# PX4_FMUv6X_Dev_Board.net
KiCad netlist of a schematic drawn in EasyEDA Pro
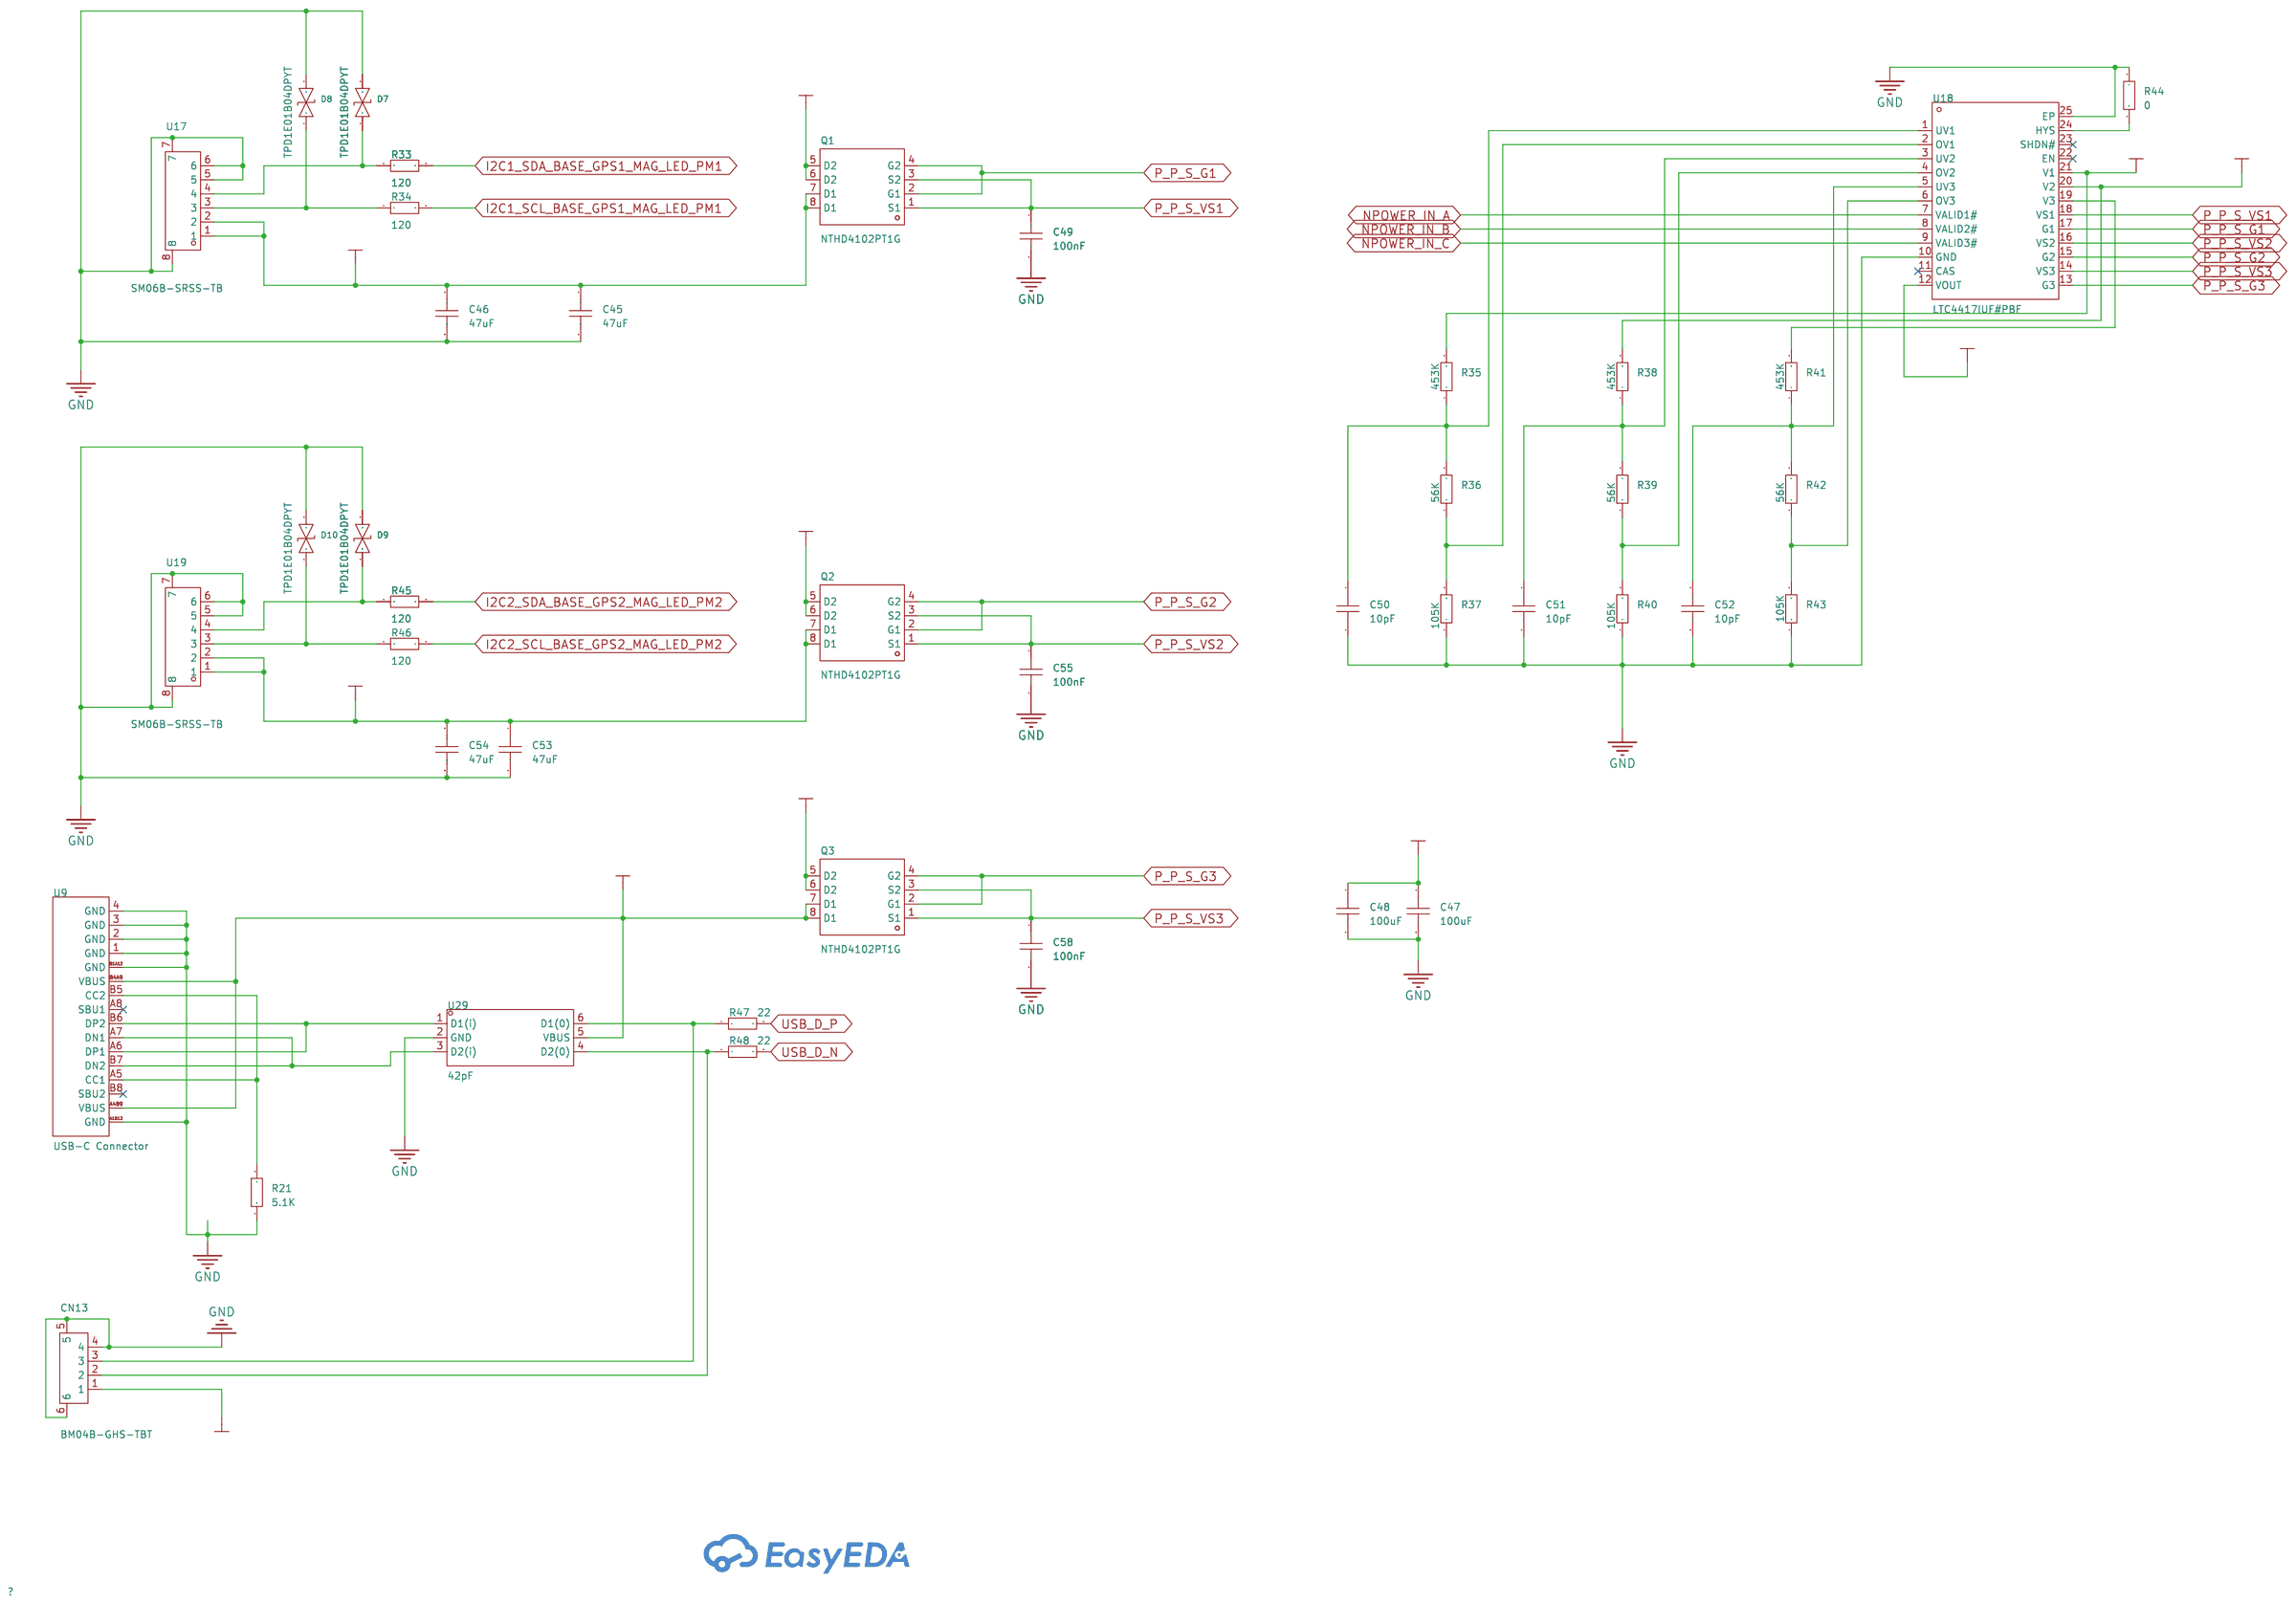
[diagram p0: Power MUX]
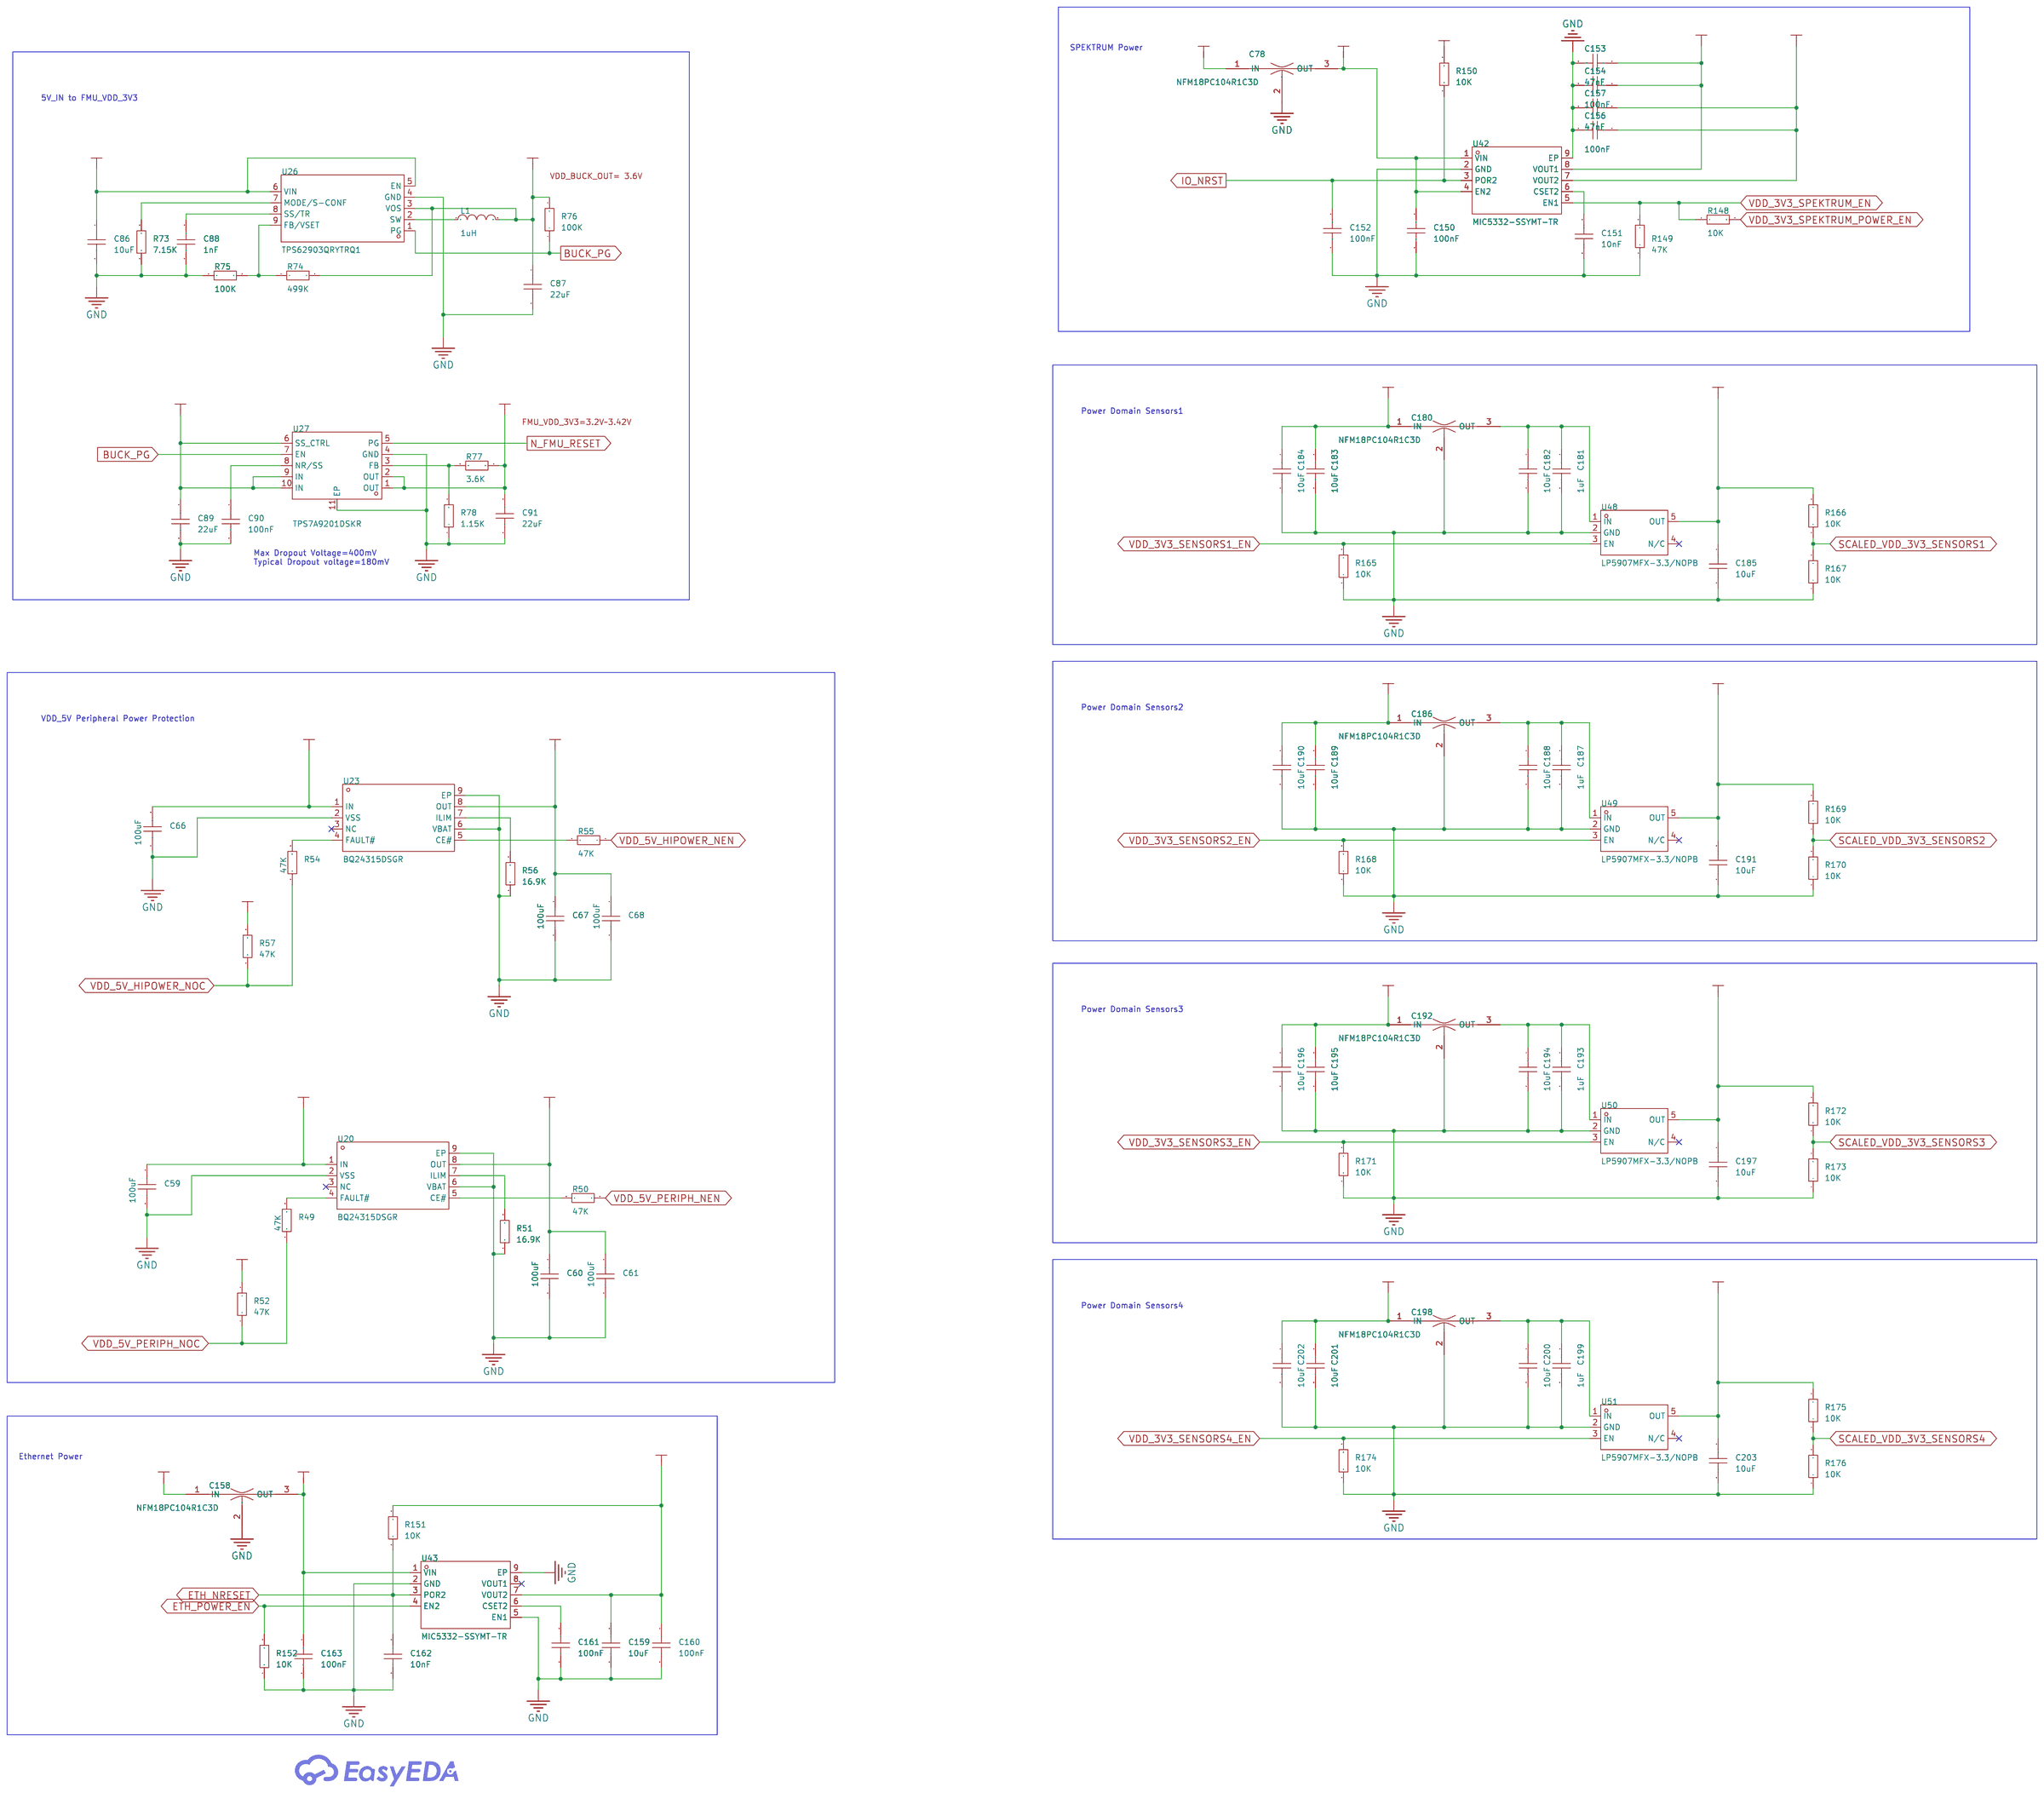
[diagram p1: Power]
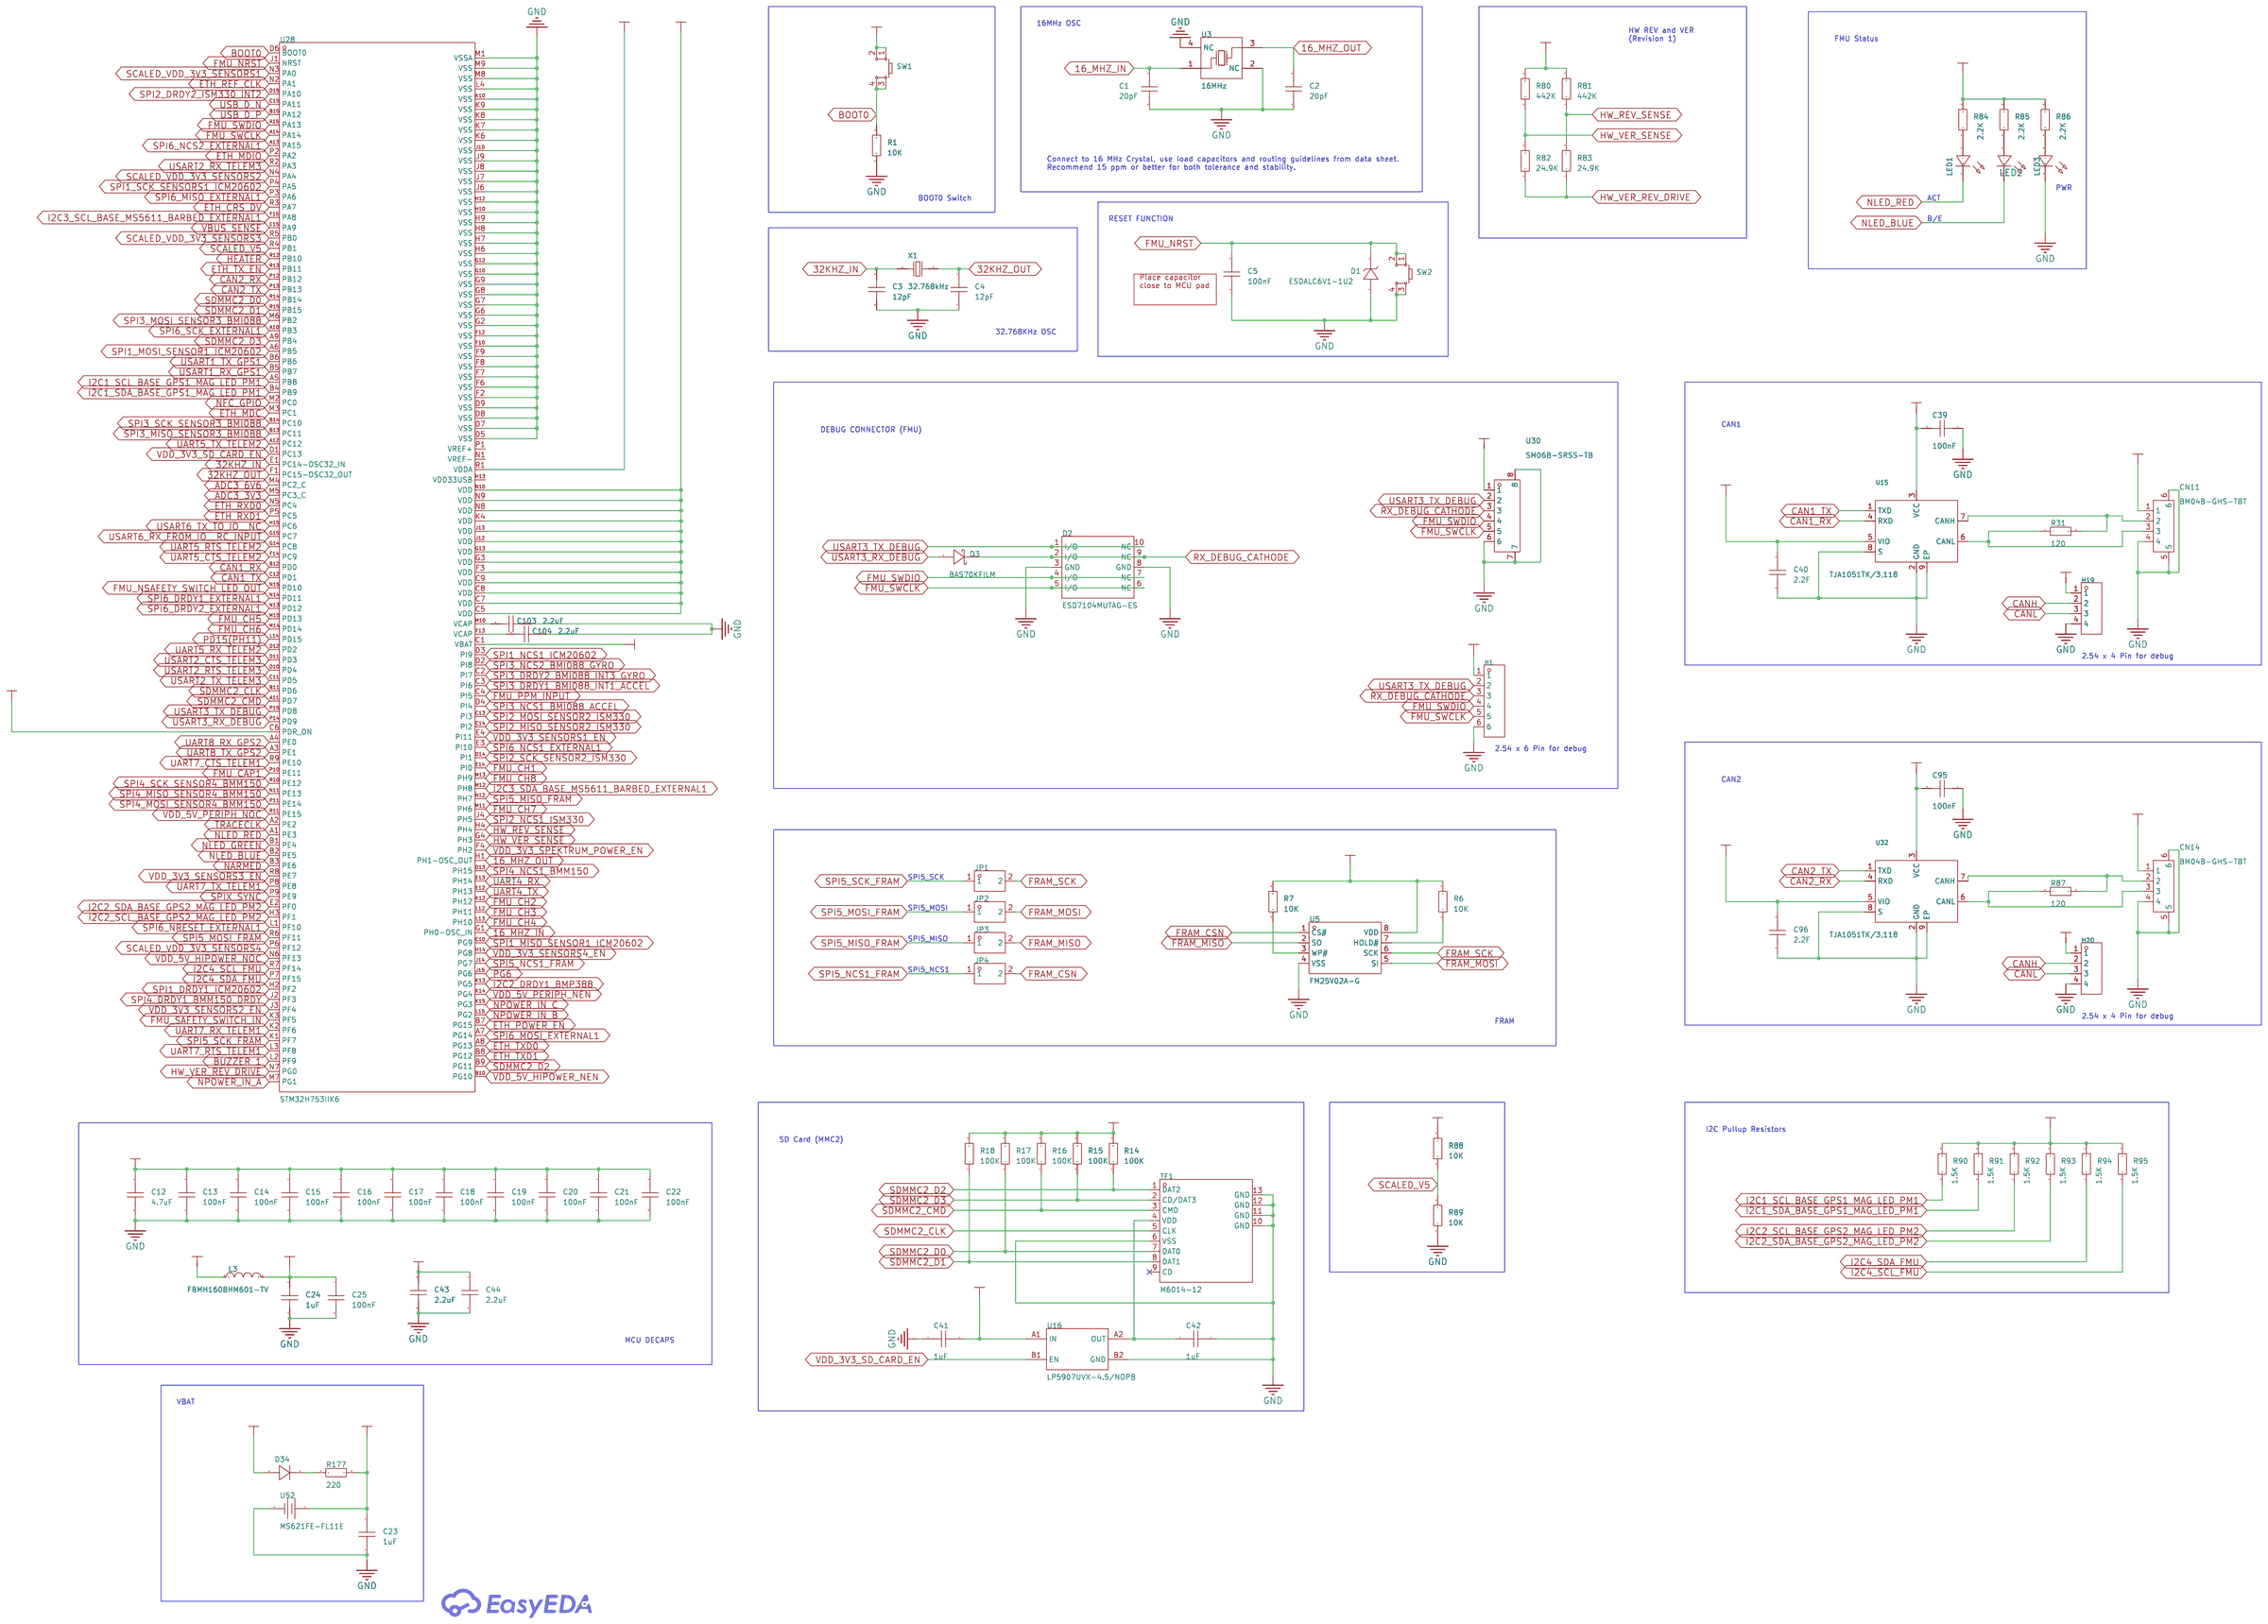
[diagram p2: FMU MCU STM32H753IIK6]
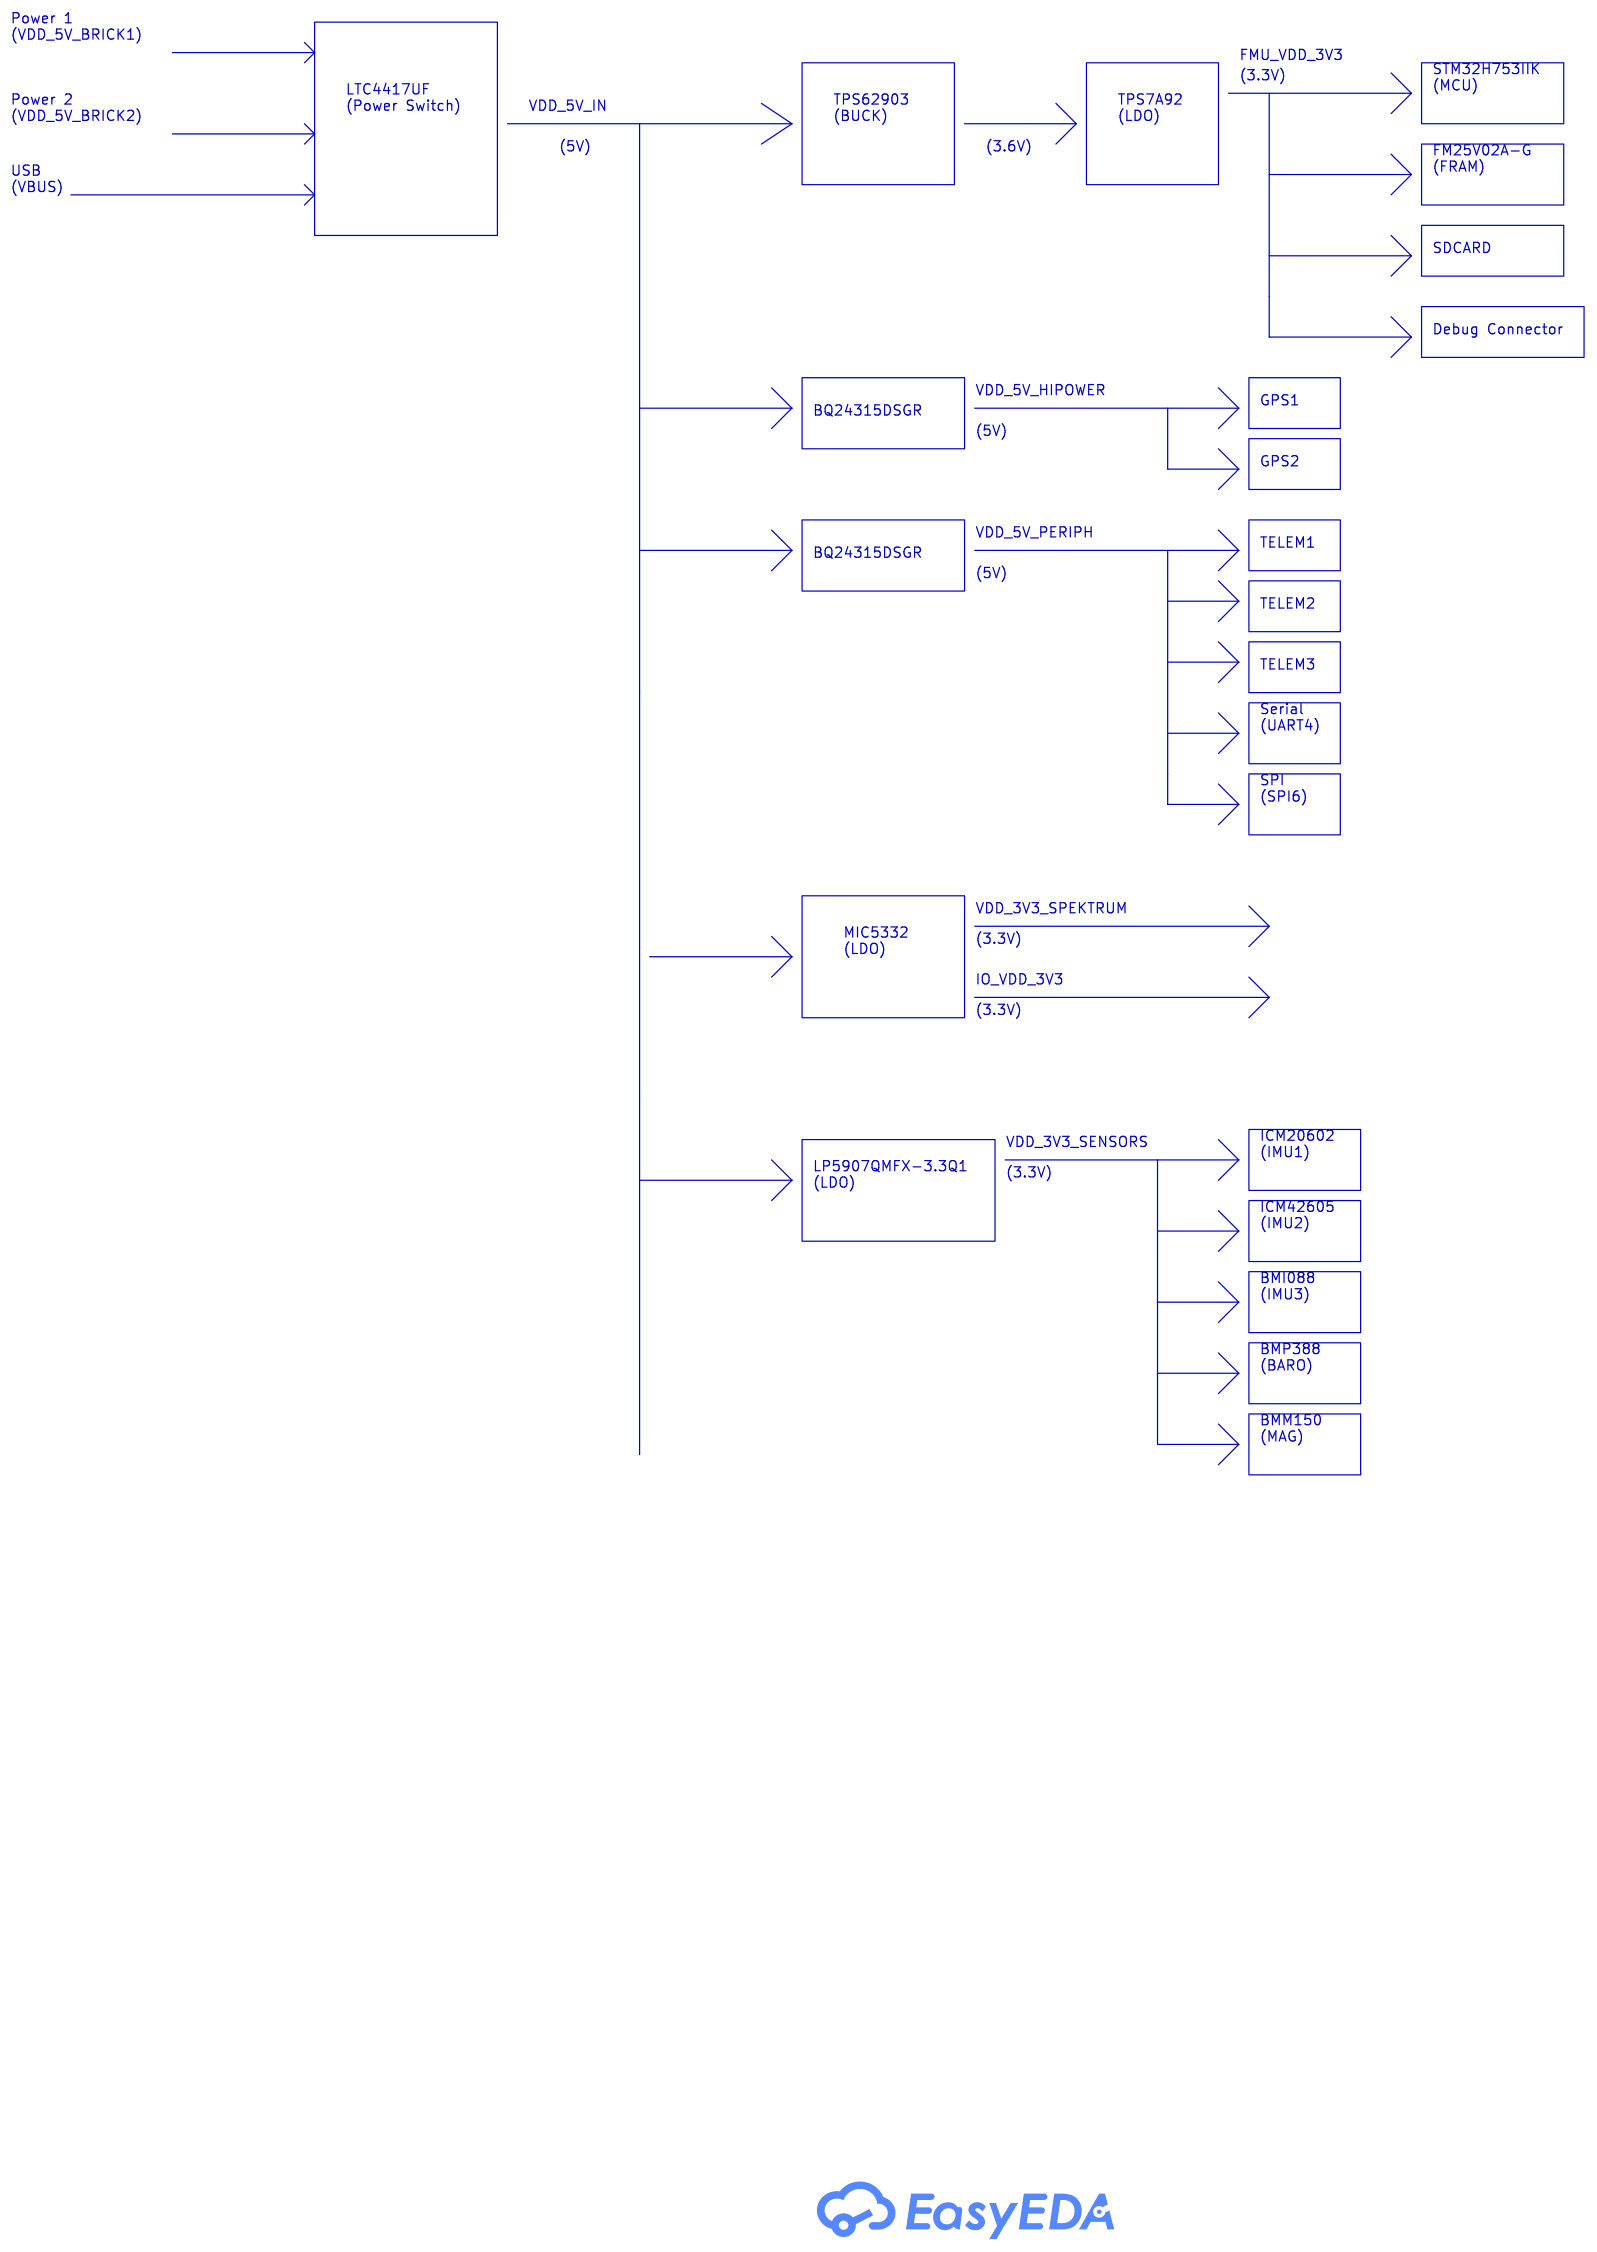
[diagram p3: Power Description]
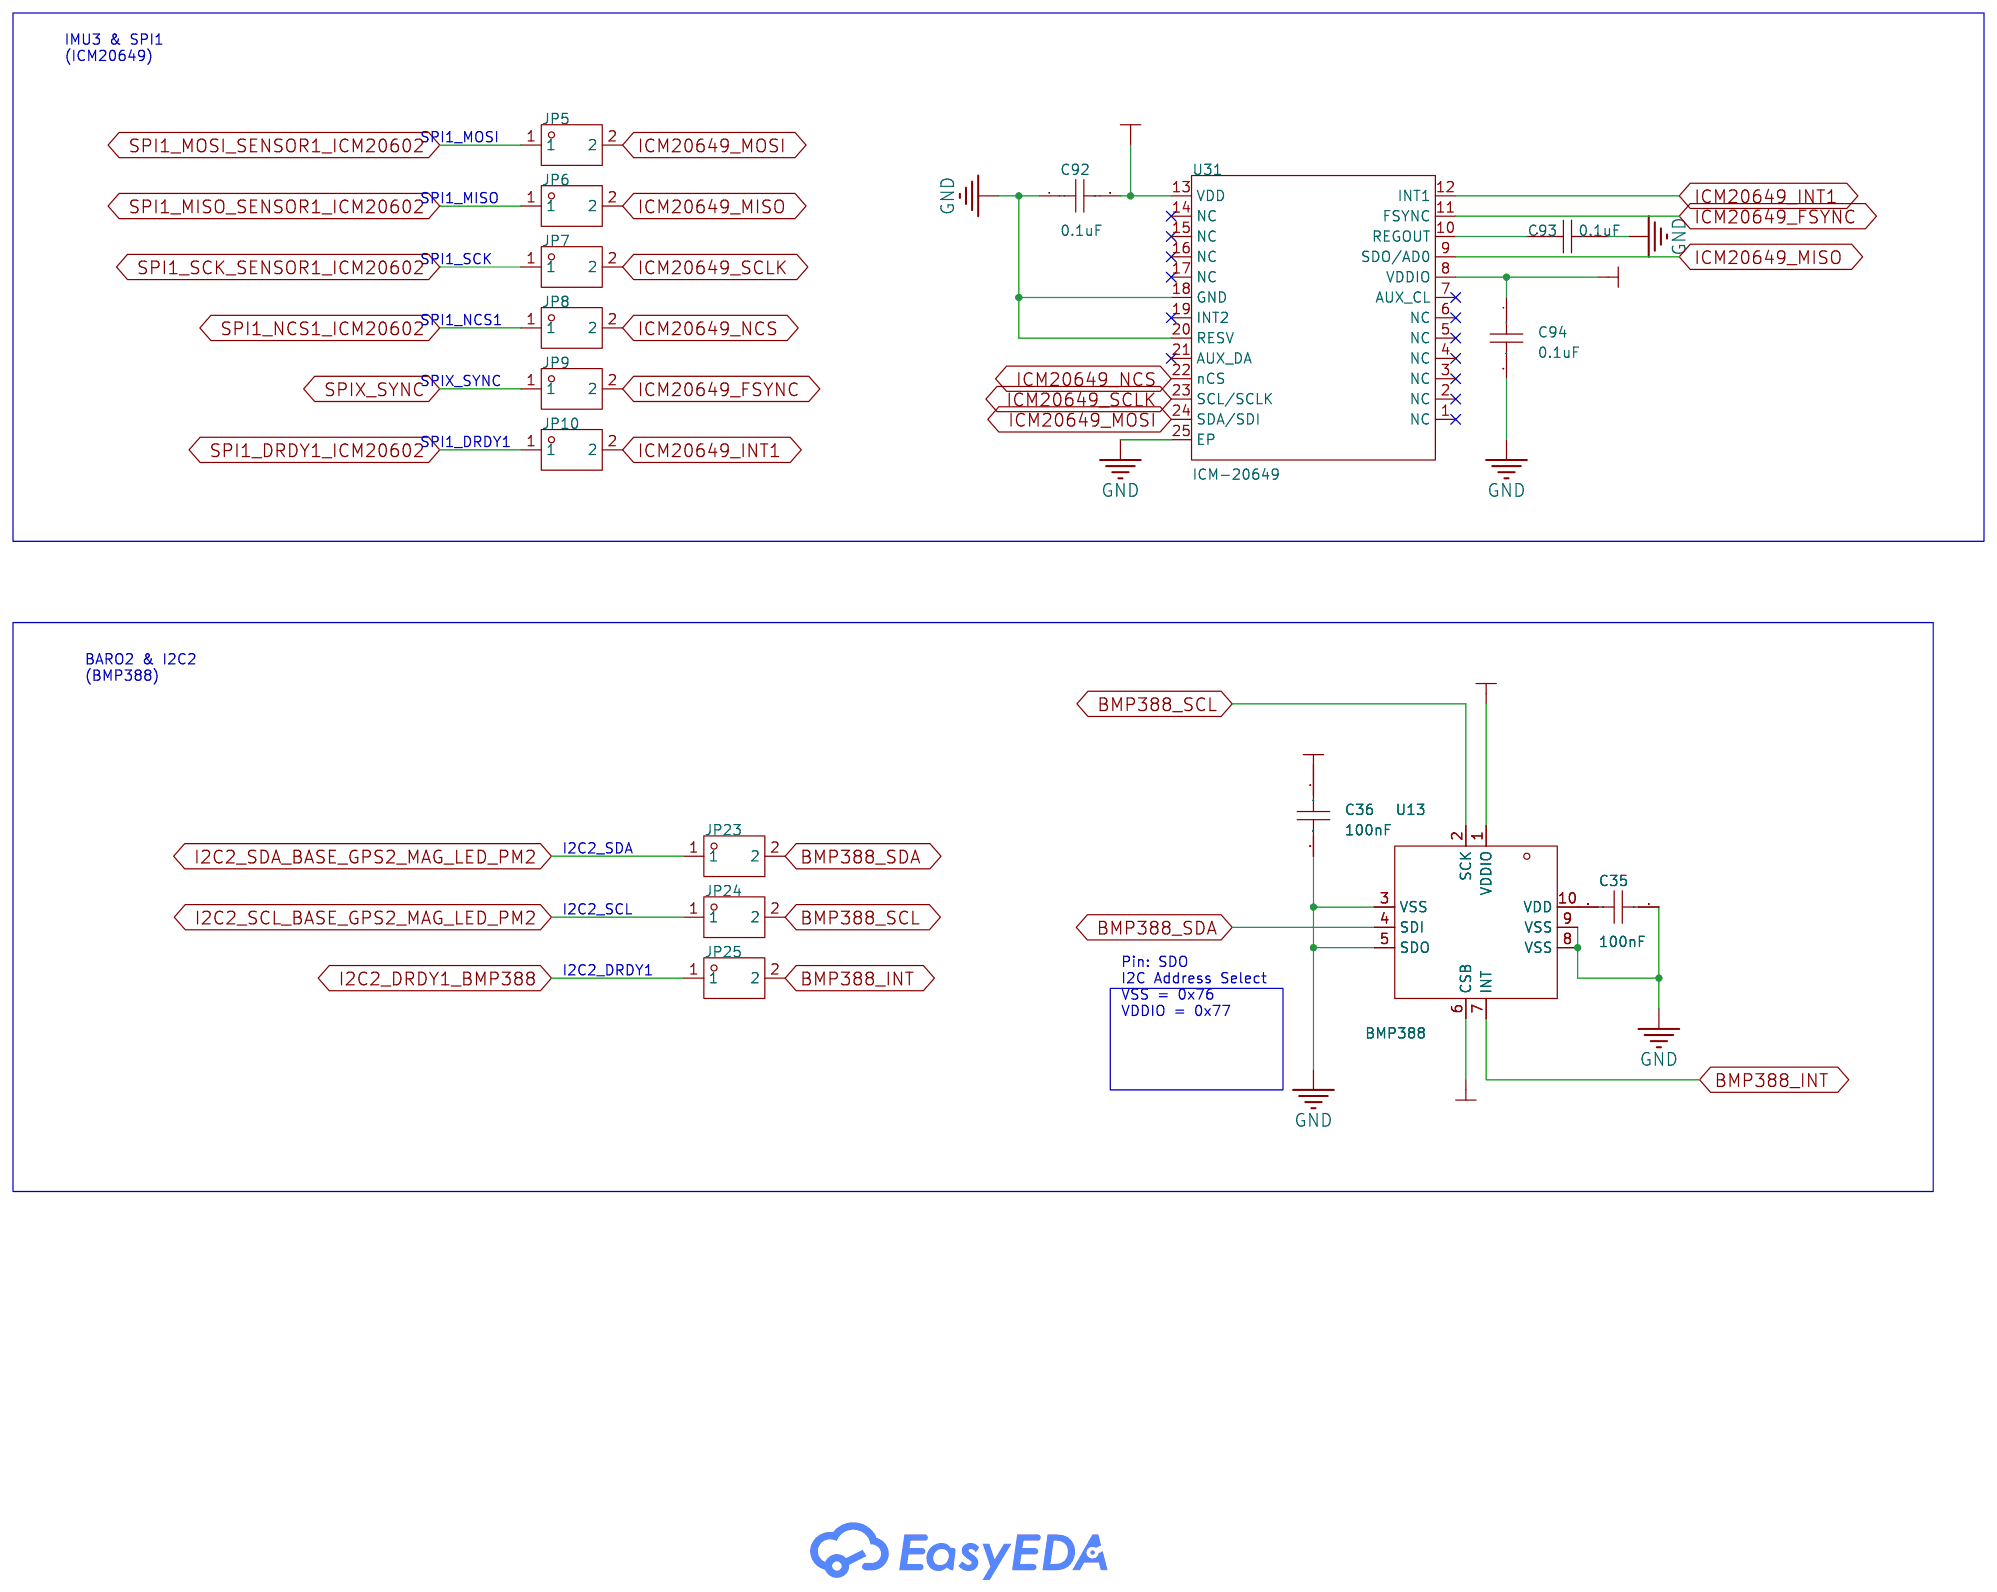
[diagram p4: Sensors - FMU Board]
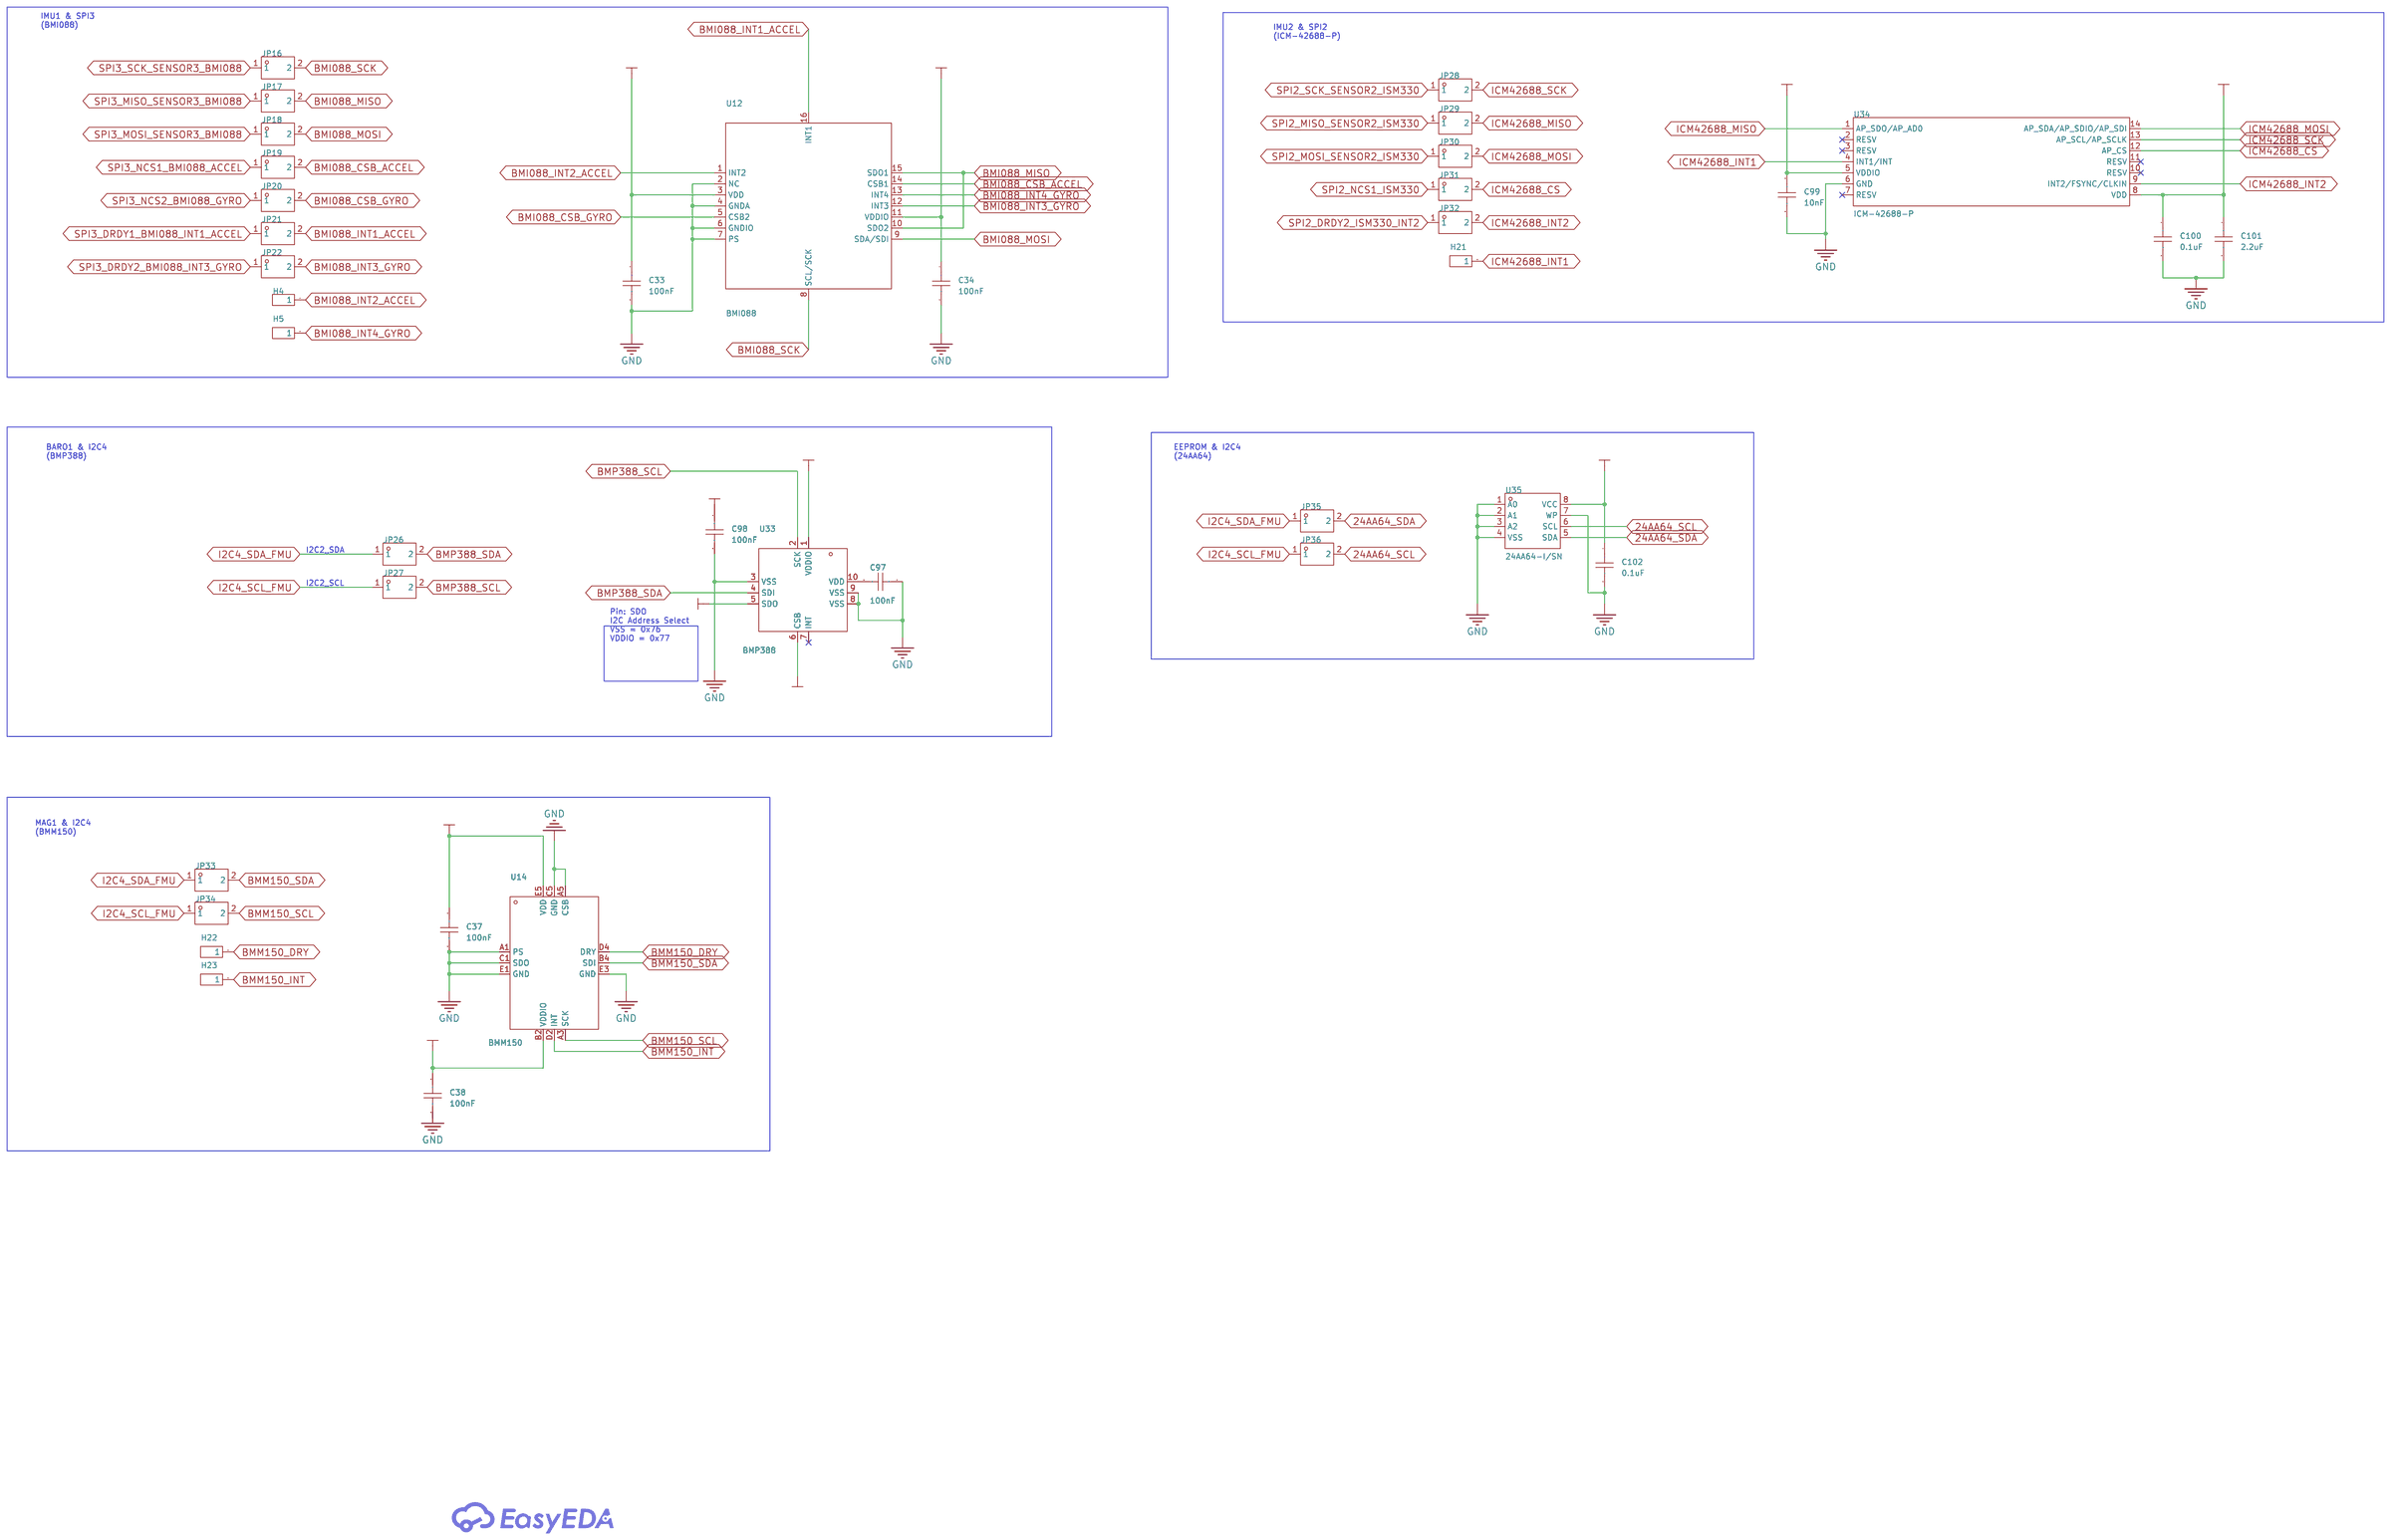
[diagram p5: Sensors - IMU Board]
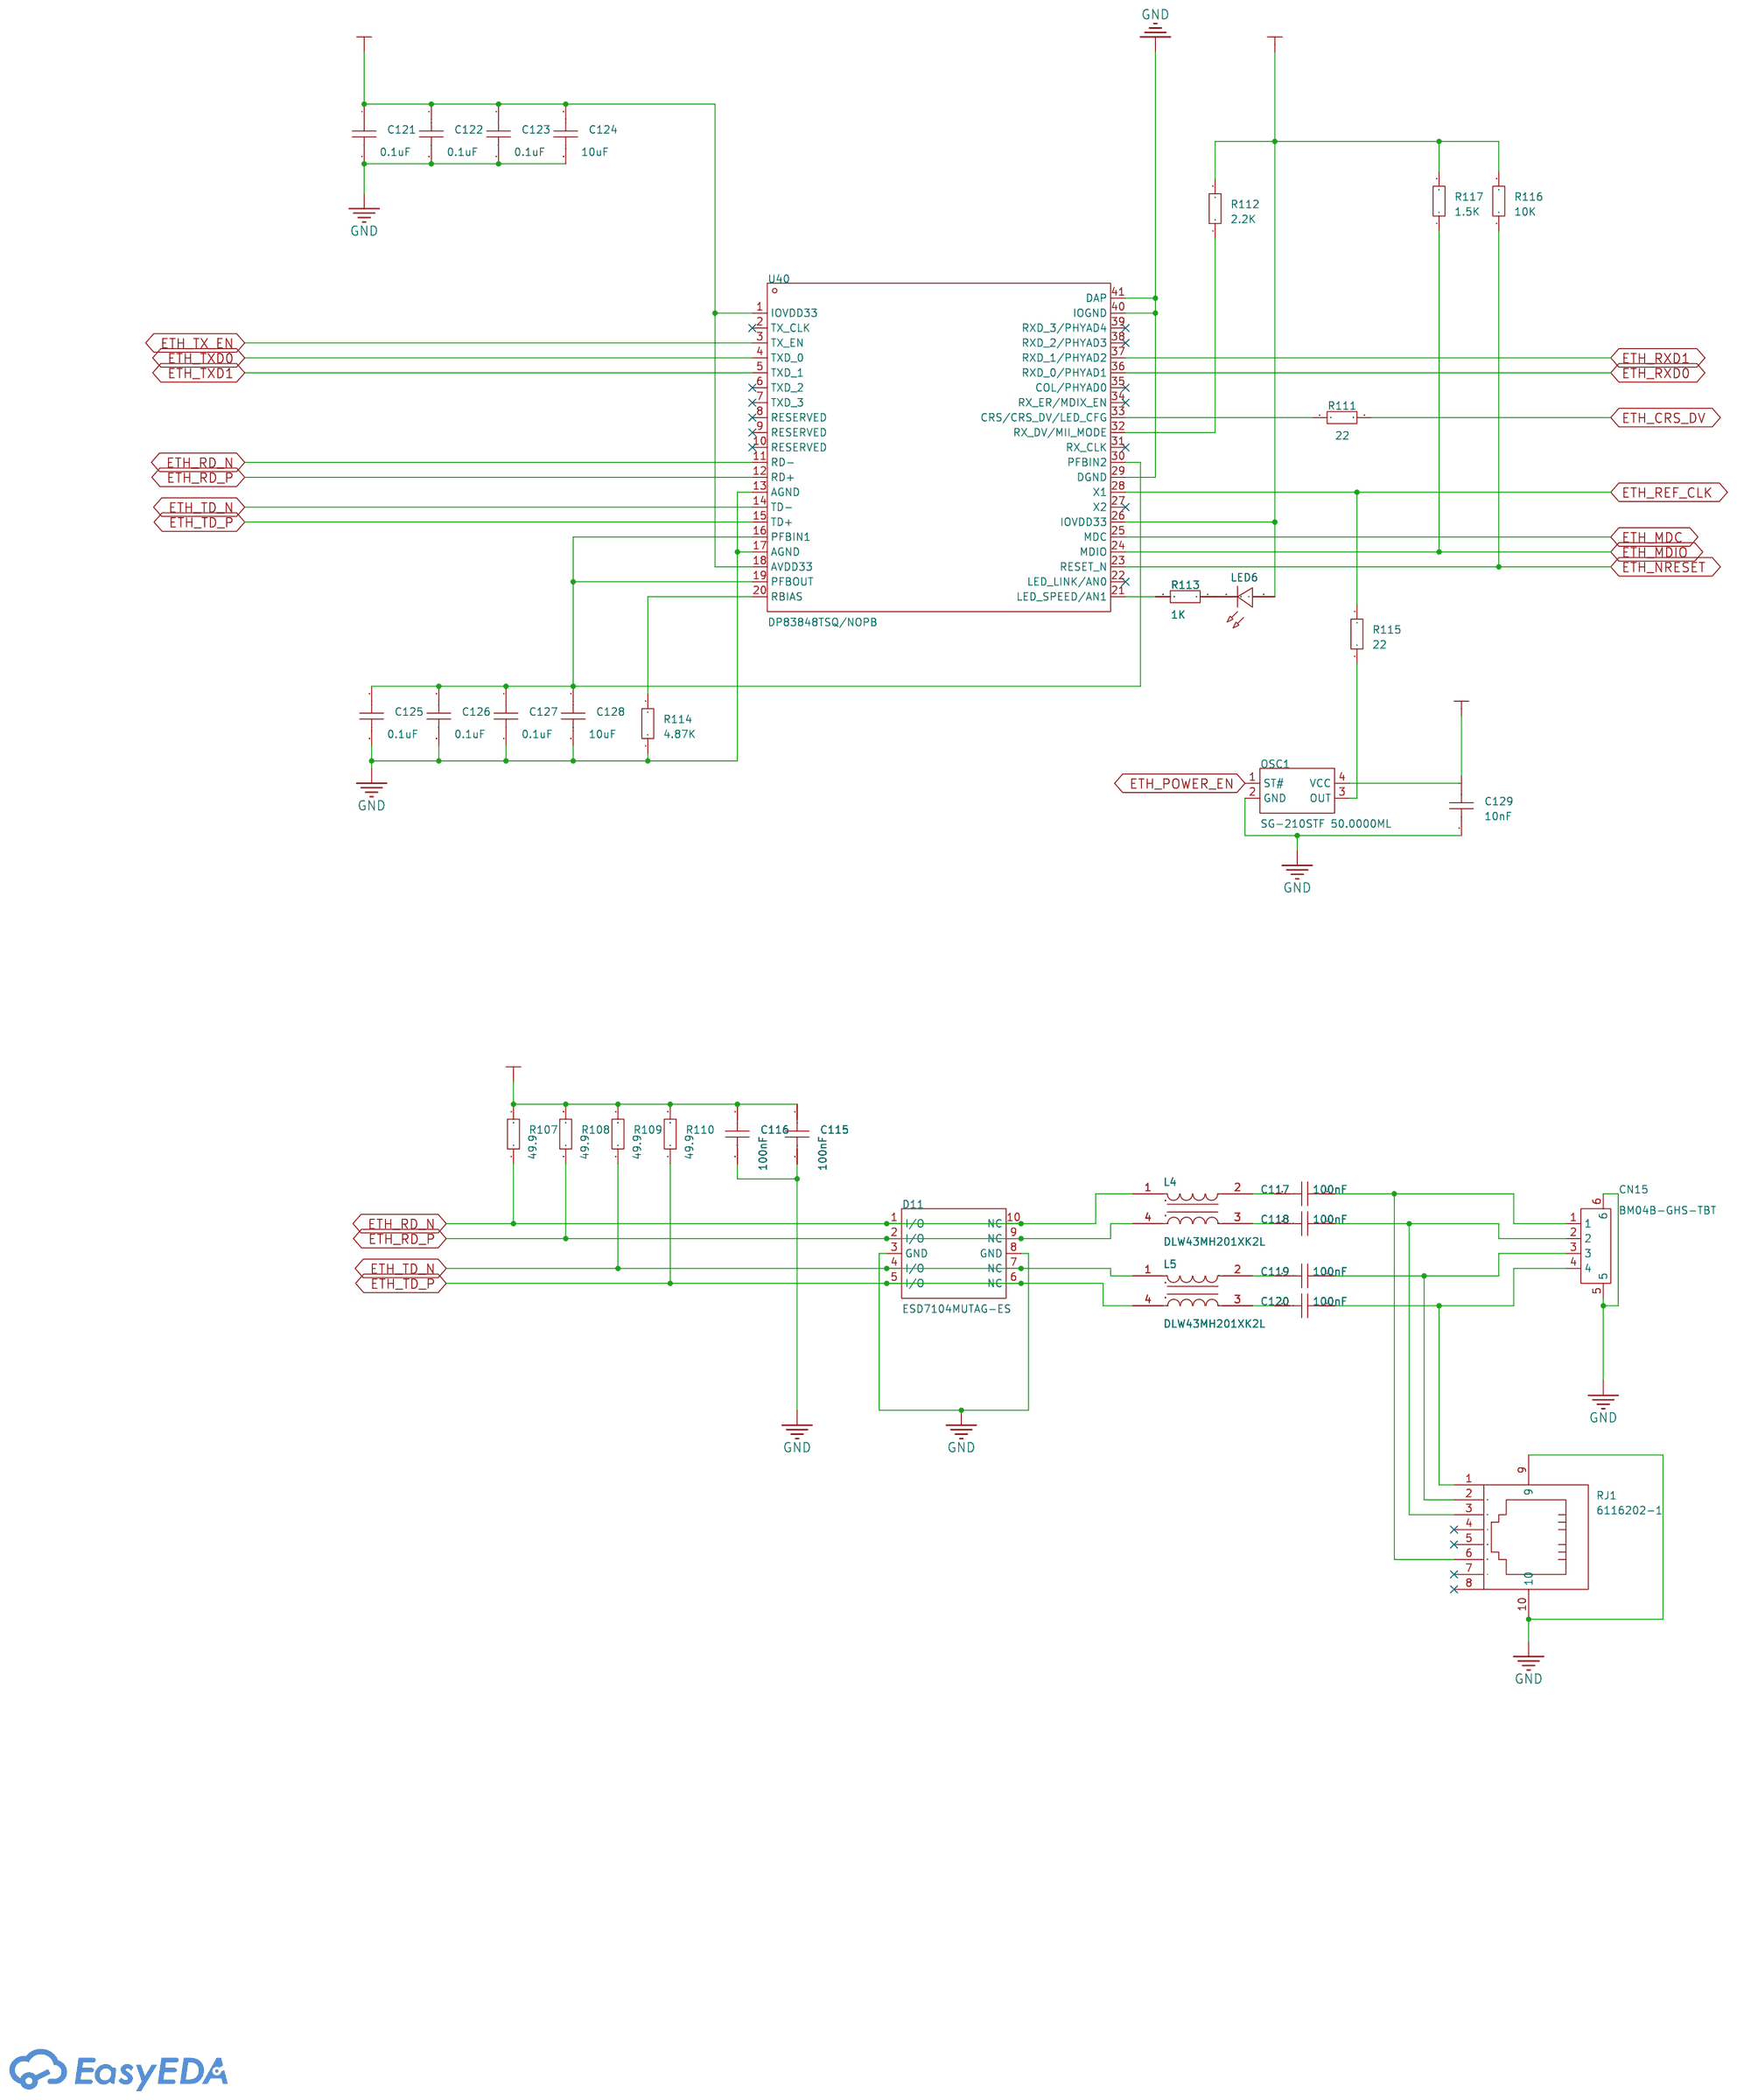
[diagram p6: Ethernet 100 Base-TX]
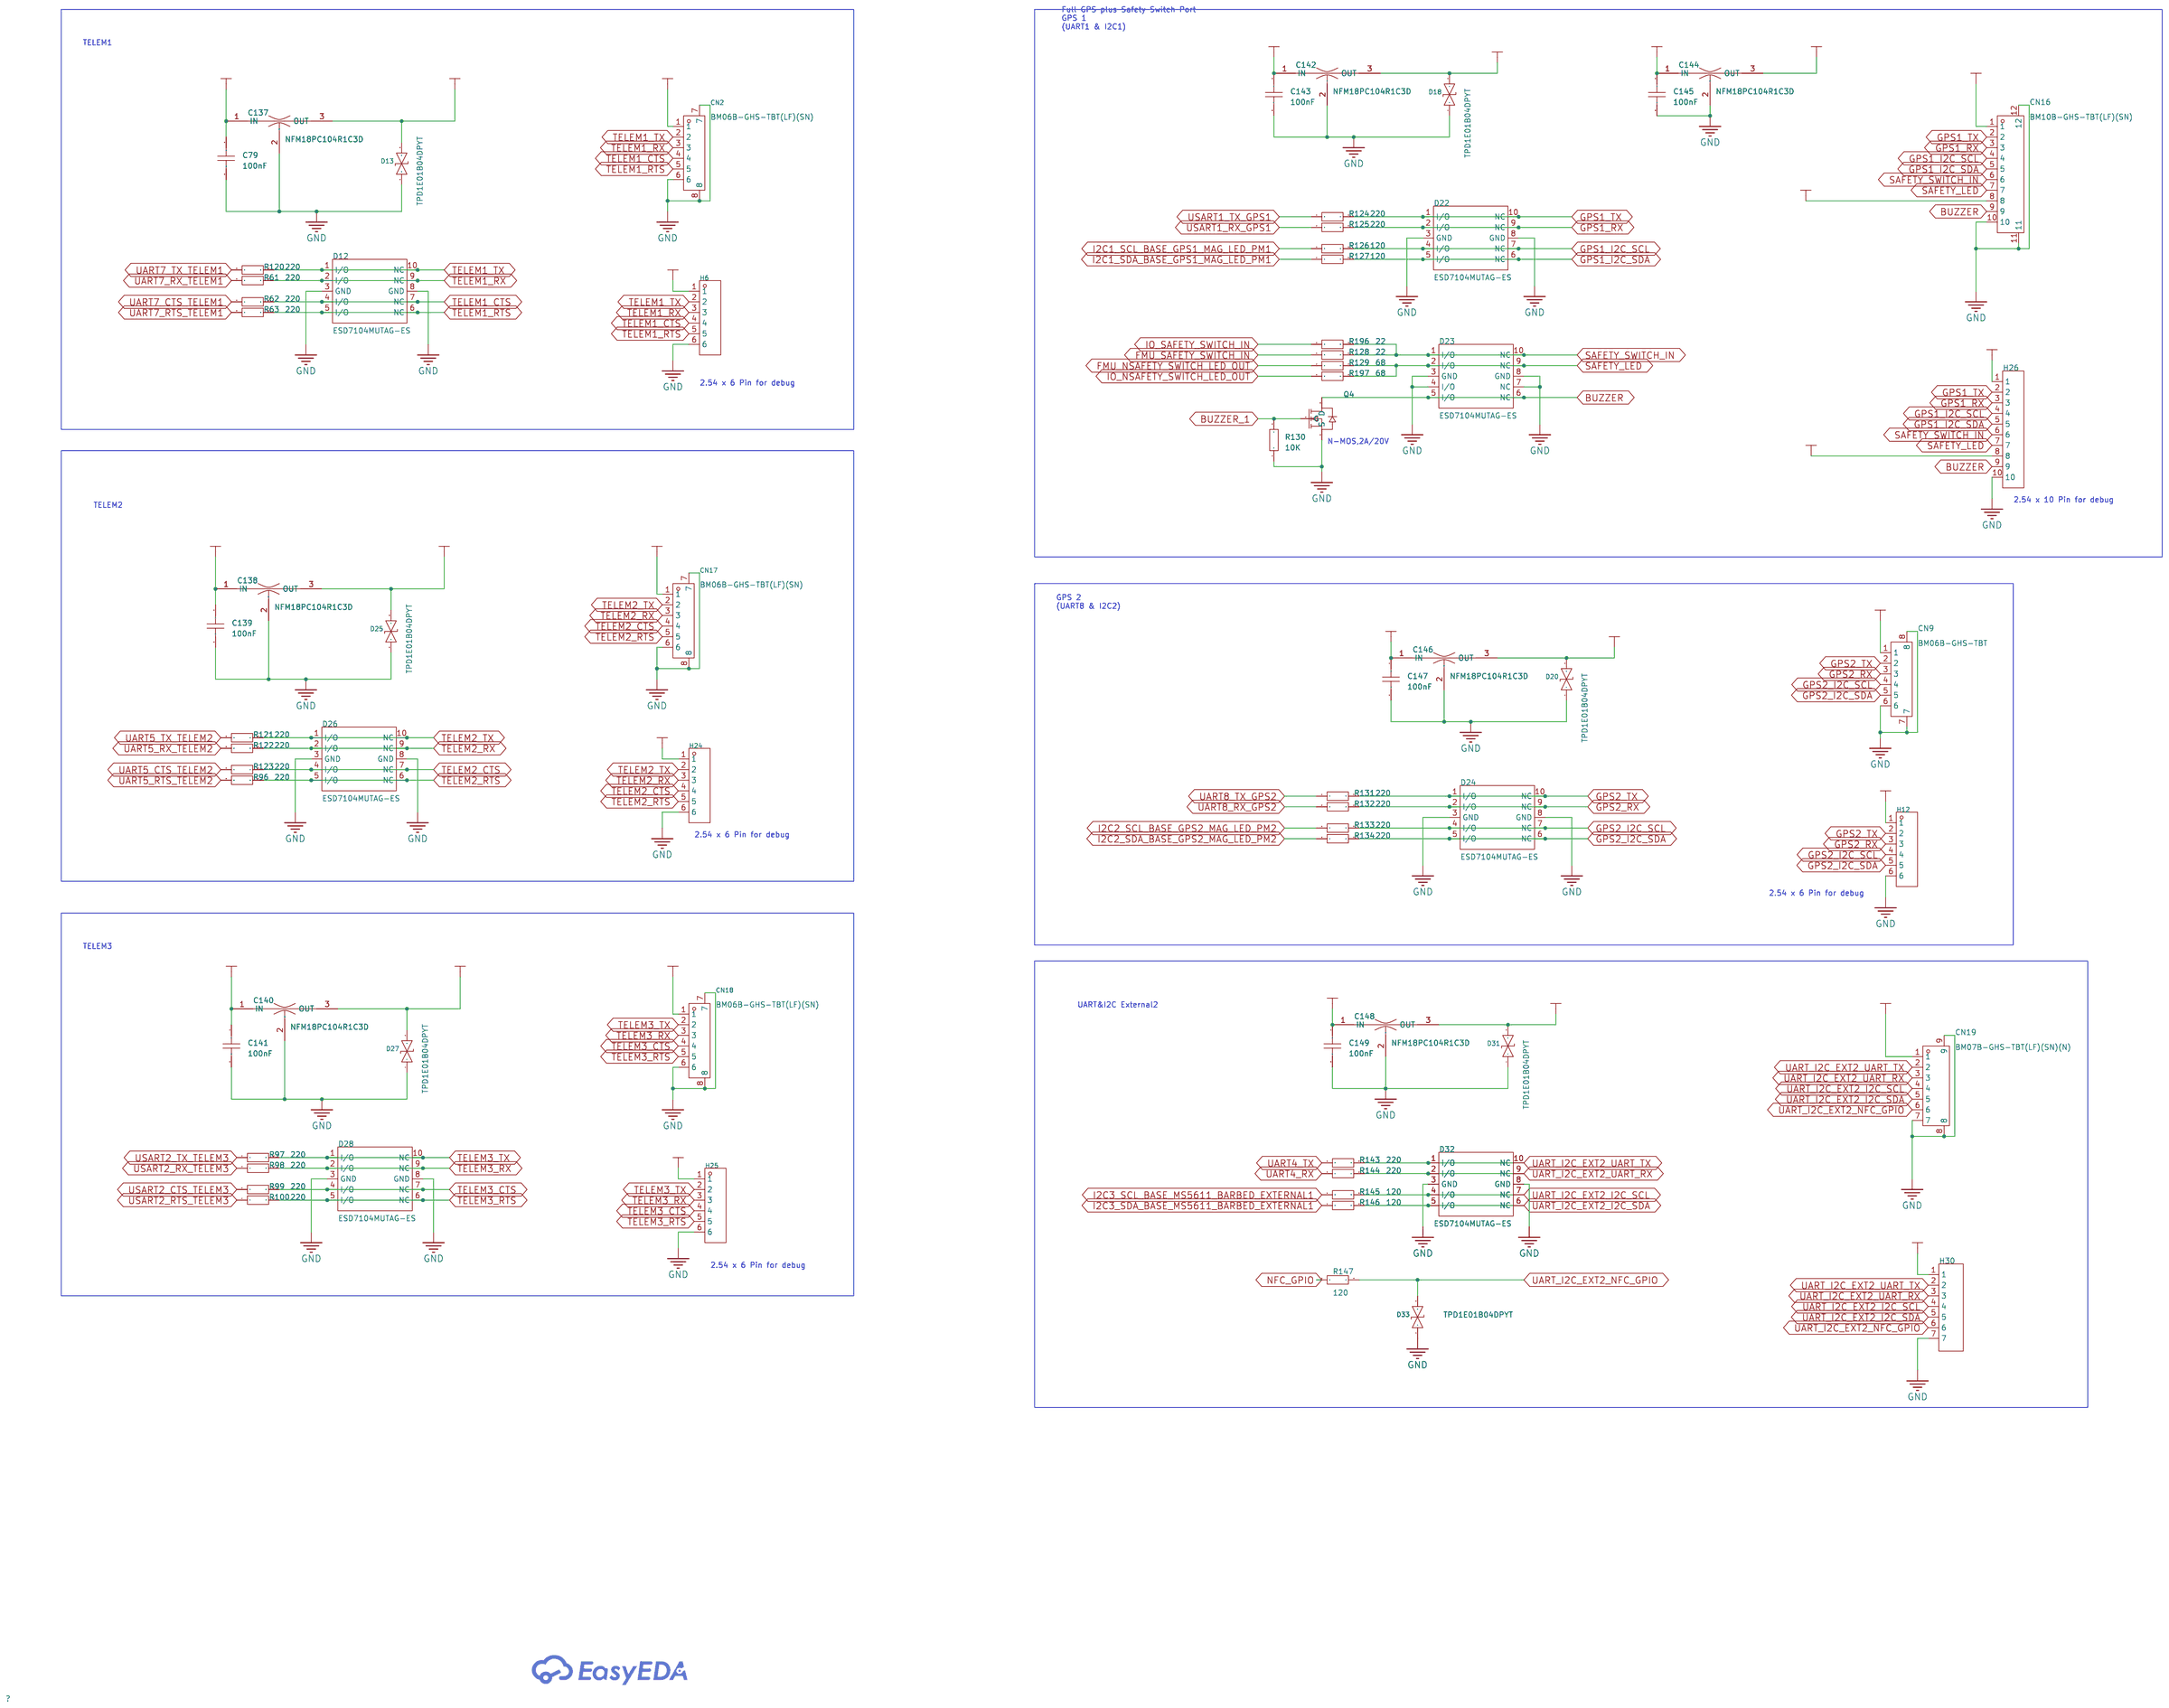
[diagram p7: UART and GPS Connectors]
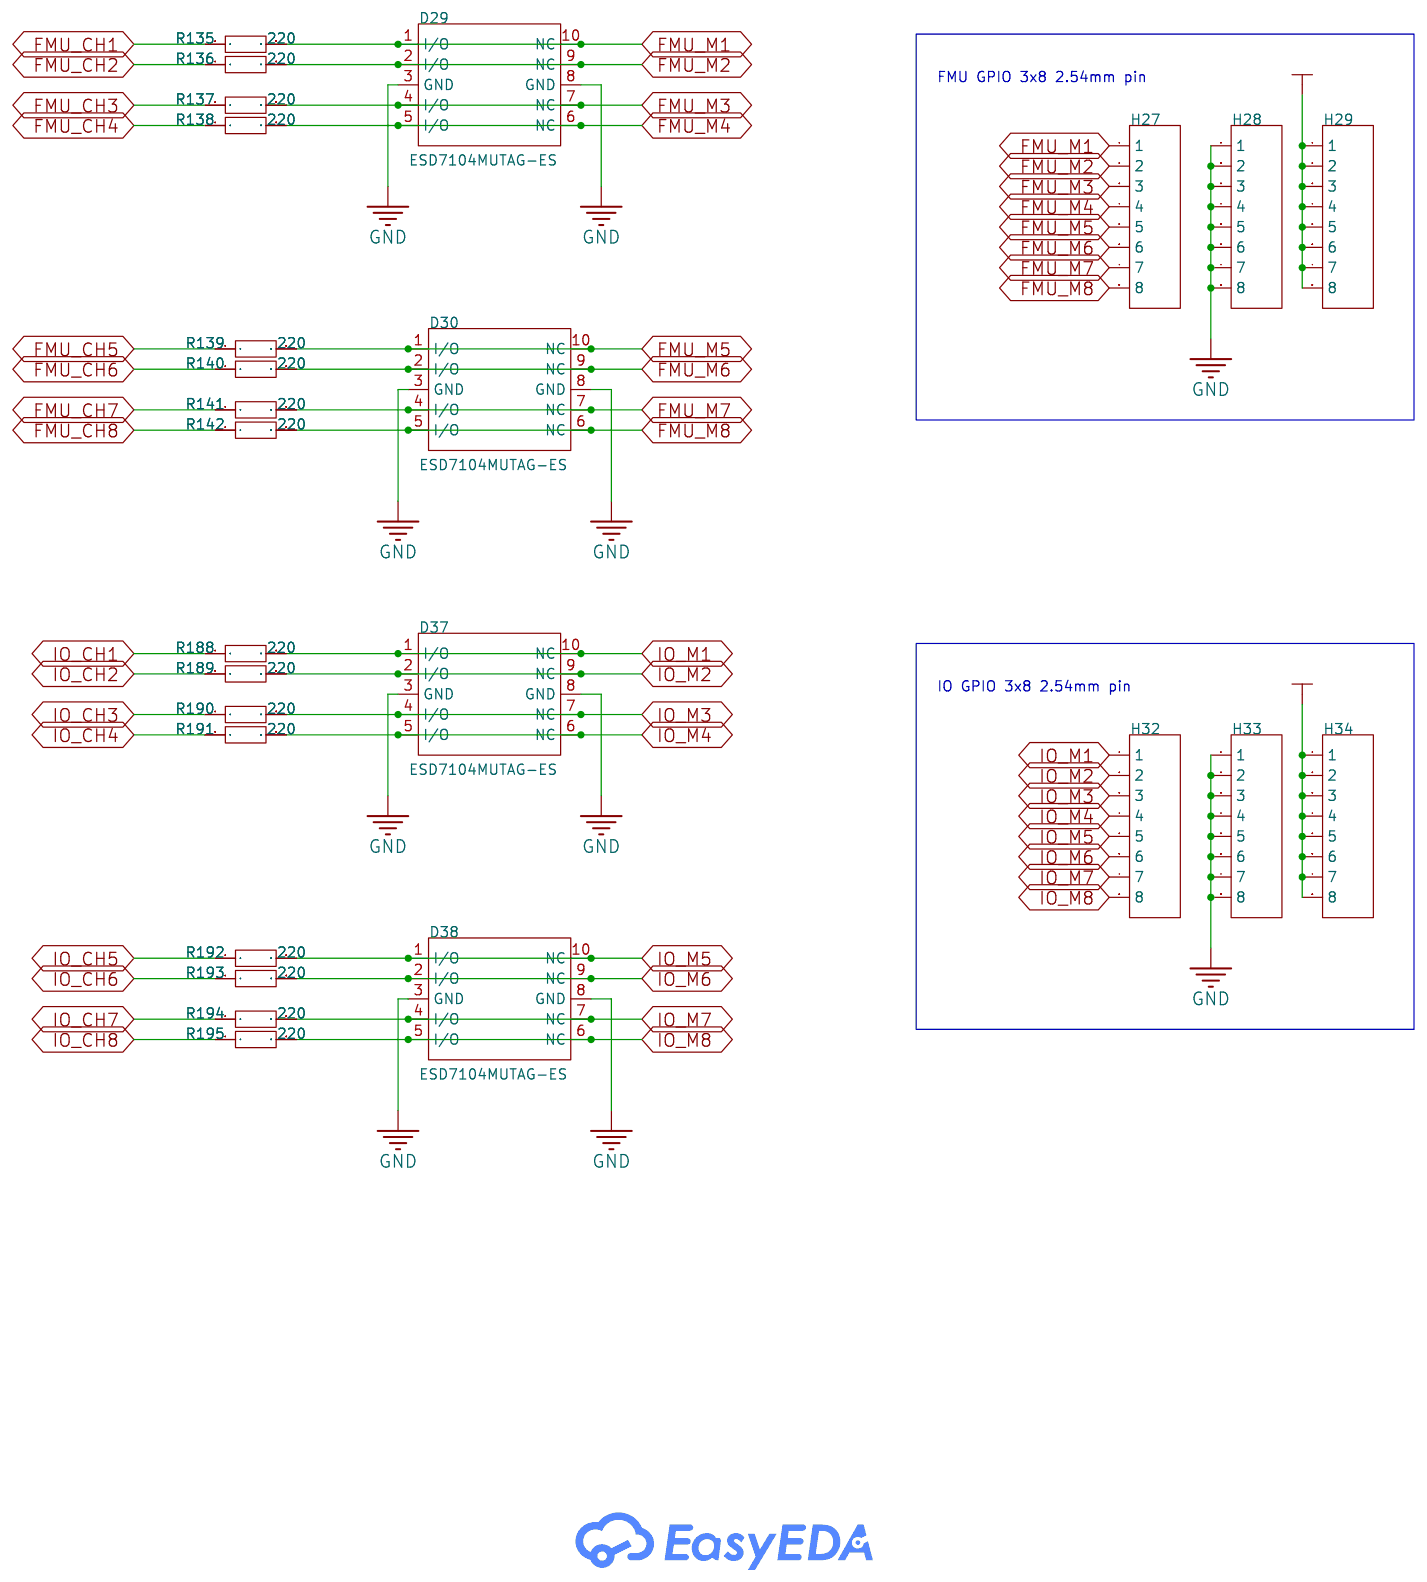
[diagram p8: GPIO 2.54mm 16x8]
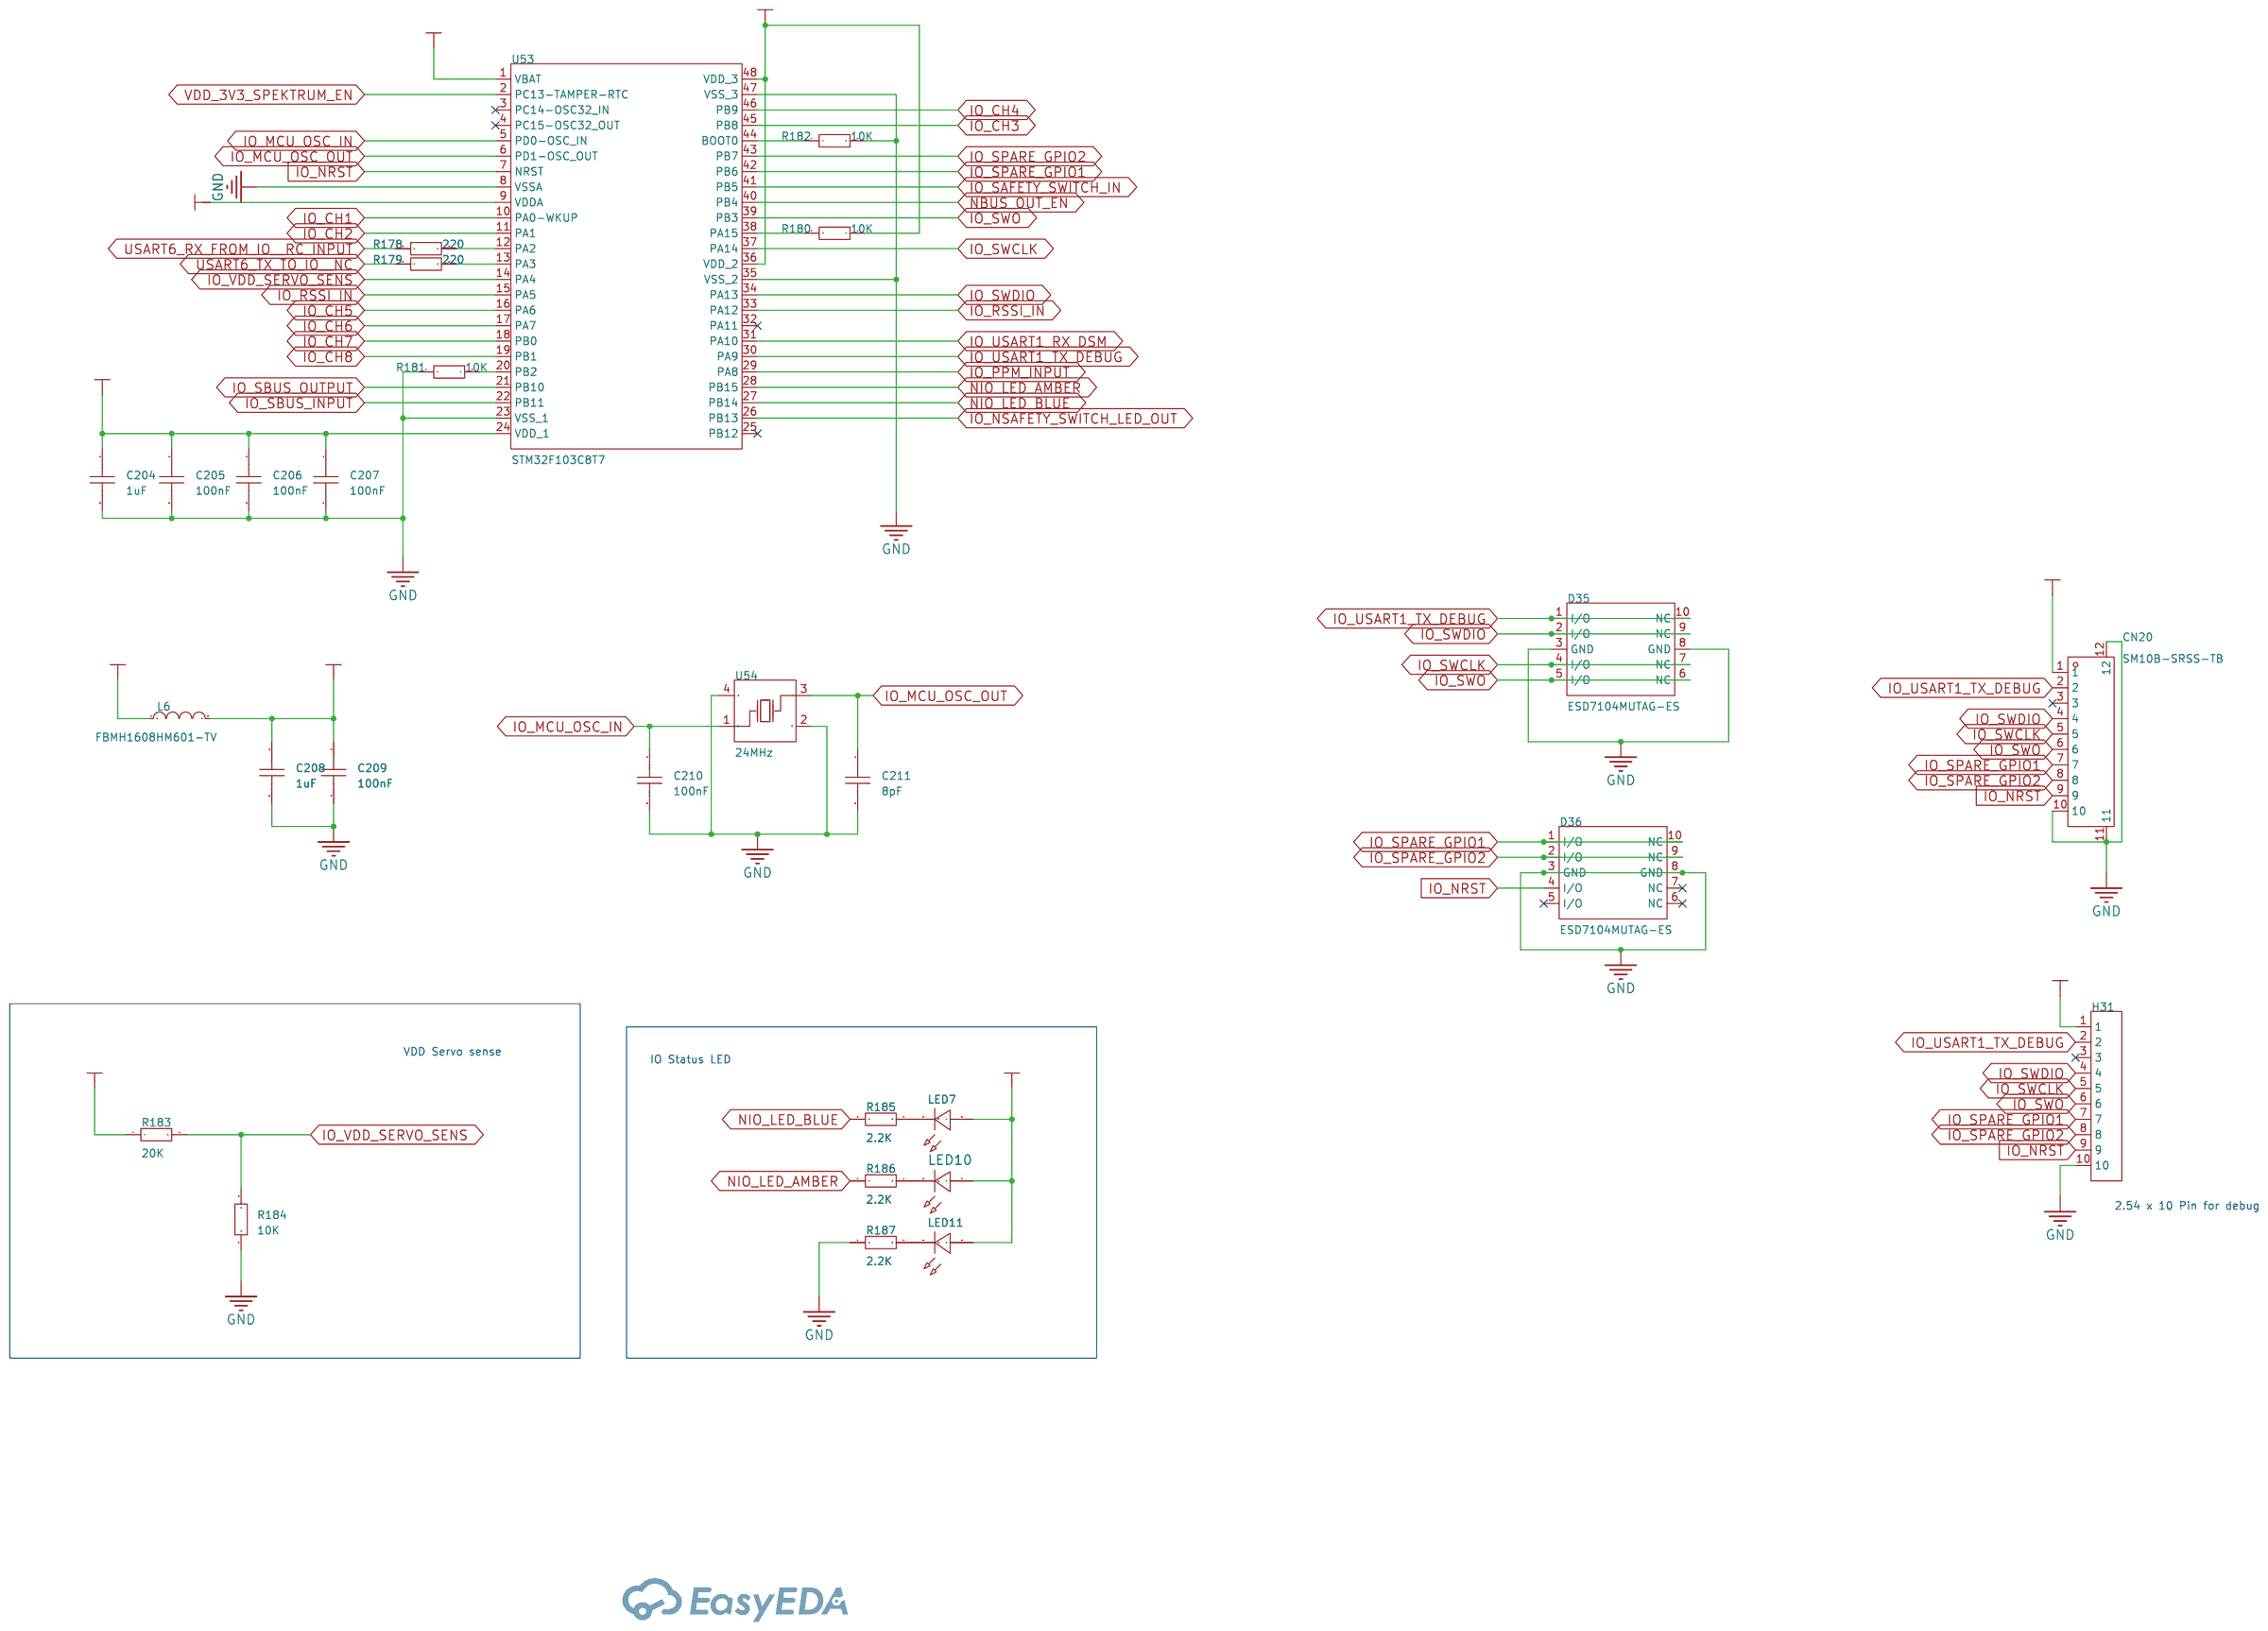
[diagram p9: IO MCU STM32F103C8T7]
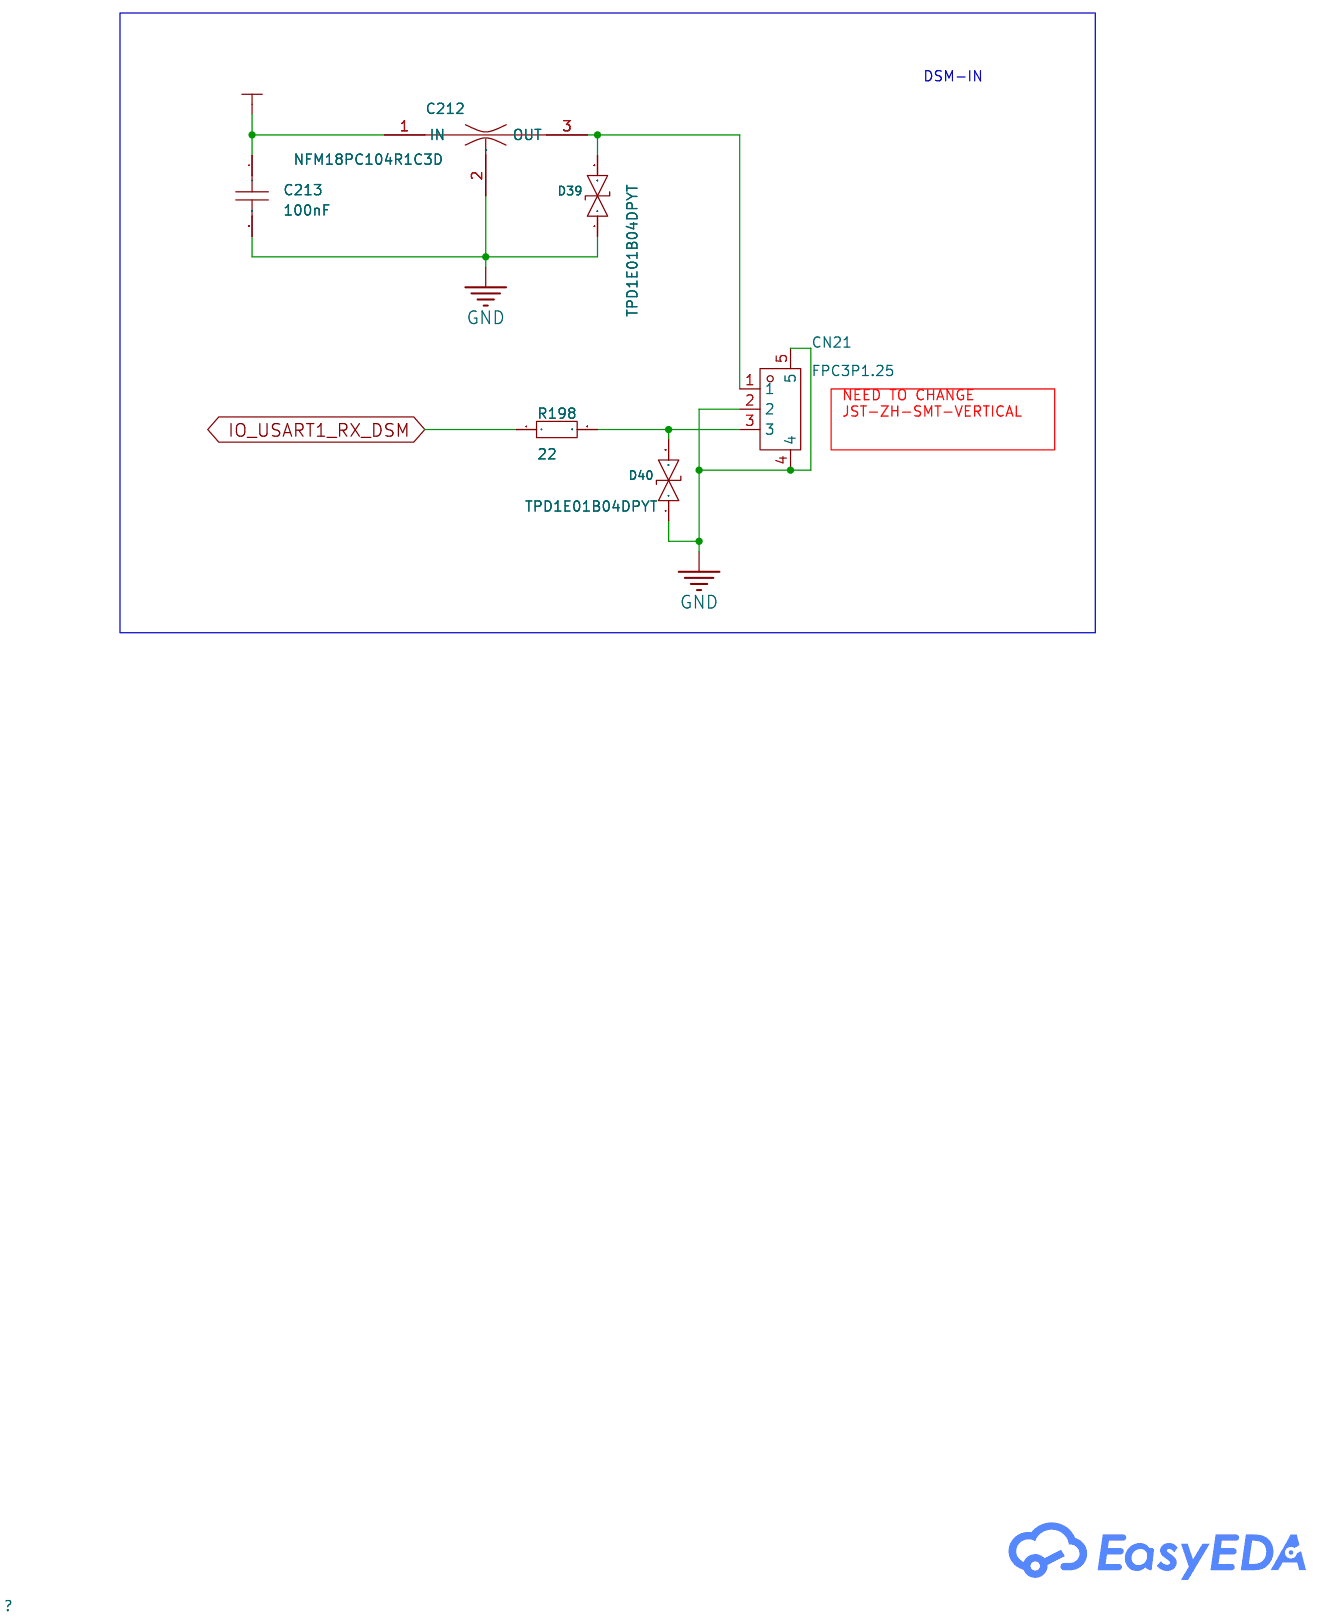
[diagram p10: RC and ADIO]

(export (version "E")
  (design (tool "Eeschema 10.0.6"))
  (components
    (comp (ref "C45")
      (value "47uF")
      (footprint "easyedapro:C0201")
      (libsource (lib "easyedapro") (part "CAP"))
    )
    (comp (ref "C46")
      (value "47uF")
      (footprint "easyedapro:C0201")
      (libsource (lib "easyedapro") (part "CAP"))
    )
    (comp (ref "C47")
      (value "100uF")
      (footprint "easyedapro:C0201")
      (libsource (lib "easyedapro") (part "CAP"))
    )
    (comp (ref "C48")
      (value "100uF")
      (footprint "easyedapro:C0201")
      (libsource (lib "easyedapro") (part "CAP"))
    )
    (comp (ref "C49")
      (value "100nF")
      (footprint "easyedapro:C0201")
      (libsource (lib "easyedapro") (part "CAP"))
    )
    (comp (ref "C50")
      (value "10pF")
      (footprint "easyedapro:C0201")
      (libsource (lib "easyedapro") (part "CAP"))
    )
    (comp (ref "C51")
      (value "10pF")
      (footprint "easyedapro:C0201")
      (libsource (lib "easyedapro") (part "CAP"))
    )
    (comp (ref "C52")
      (value "10pF")
      (footprint "easyedapro:C0201")
      (libsource (lib "easyedapro") (part "CAP"))
    )
    (comp (ref "C53")
      (value "47uF")
      (footprint "easyedapro:C0201")
      (libsource (lib "easyedapro") (part "CAP"))
    )
    (comp (ref "C54")
      (value "47uF")
      (footprint "easyedapro:C0201")
      (libsource (lib "easyedapro") (part "CAP"))
    )
    (comp (ref "C55")
      (value "100nF")
      (footprint "easyedapro:C0201")
      (libsource (lib "easyedapro") (part "CAP"))
    )
    (comp (ref "C58")
      (value "100nF")
      (footprint "easyedapro:C0201")
      (libsource (lib "easyedapro") (part "CAP"))
    )
    (comp (ref "CN13")
      (value "BM04B-GHS-TBT")
      (footprint "easyedapro:CONN-SMD_4P-P1.25_BM04B-GHS-TBT-LF-SN")
      (fields (field (name "Manufacturer") "JST"))
      (libsource (lib "easyedapro") (part "BM04B-GHS-TBT"))
    )
    (comp (ref "D7")
      (value "TPD1E01B04DPYT")
      (footprint "easyedapro:X1SON-2_L1.0-W0.6-P0.65-BI")
      (fields (field (name "Manufacturer") "TI(德州仪器)"))
      (libsource (lib "easyedapro") (part "TPD1E01B04DPYT"))
    )
    (comp (ref "D8")
      (value "TPD1E01B04DPYT")
      (footprint "easyedapro:X1SON-2_L1.0-W0.6-P0.65-BI")
      (fields (field (name "Manufacturer") "TI(德州仪器)"))
      (libsource (lib "easyedapro") (part "TPD1E01B04DPYT"))
    )
    (comp (ref "D9")
      (value "TPD1E01B04DPYT")
      (footprint "easyedapro:X1SON-2_L1.0-W0.6-P0.65-BI")
      (fields (field (name "Manufacturer") "TI(德州仪器)"))
      (libsource (lib "easyedapro") (part "TPD1E01B04DPYT"))
    )
    (comp (ref "D10")
      (value "TPD1E01B04DPYT")
      (footprint "easyedapro:X1SON-2_L1.0-W0.6-P0.65-BI")
      (fields (field (name "Manufacturer") "TI(德州仪器)"))
      (libsource (lib "easyedapro") (part "TPD1E01B04DPYT"))
    )
    (comp (ref "Q1")
      (value "NTHD4102PT1G")
      (footprint "easyedapro:MOS-SMD-8_L3.1-W1.7-P0.65-BL")
      (libsource (lib "easyedapro") (part "NTHD4102PT1G"))
    )
    (comp (ref "Q2")
      (value "NTHD4102PT1G")
      (footprint "easyedapro:MOS-SMD-8_L3.1-W1.7-P0.65-BL")
      (libsource (lib "easyedapro") (part "NTHD4102PT1G"))
    )
    (comp (ref "Q3")
      (value "NTHD4102PT1G")
      (footprint "easyedapro:MOS-SMD-8_L3.1-W1.7-P0.65-BL")
      (libsource (lib "easyedapro") (part "NTHD4102PT1G"))
    )
    (comp (ref "R21")
      (value "5.1K")
      (footprint "easyedapro:R0603")
      (libsource (lib "easyedapro") (part "Res"))
    )
    (comp (ref "R33")
      (value "120")
      (footprint "easyedapro:R0603")
      (libsource (lib "easyedapro") (part "Res"))
    )
    (comp (ref "R34")
      (value "120")
      (footprint "easyedapro:R0603")
      (libsource (lib "easyedapro") (part "Res"))
    )
    (comp (ref "R35")
      (value "453K")
      (footprint "easyedapro:R0603")
      (libsource (lib "easyedapro") (part "Res"))
    )
    (comp (ref "R36")
      (value "56K")
      (footprint "easyedapro:R0603")
      (libsource (lib "easyedapro") (part "Res"))
    )
    (comp (ref "R37")
      (value "105K")
      (footprint "easyedapro:R0603")
      (libsource (lib "easyedapro") (part "Res"))
    )
    (comp (ref "R38")
      (value "453K")
      (footprint "easyedapro:R0603")
      (libsource (lib "easyedapro") (part "Res"))
    )
    (comp (ref "R39")
      (value "56K")
      (footprint "easyedapro:R0603")
      (libsource (lib "easyedapro") (part "Res"))
    )
    (comp (ref "R40")
      (value "105K")
      (footprint "easyedapro:R0603")
      (libsource (lib "easyedapro") (part "Res"))
    )
    (comp (ref "R41")
      (value "453K")
      (footprint "easyedapro:R0603")
      (libsource (lib "easyedapro") (part "Res"))
    )
    (comp (ref "R42")
      (value "56K")
      (footprint "easyedapro:R0603")
      (libsource (lib "easyedapro") (part "Res"))
    )
    (comp (ref "R43")
      (value "105K")
      (footprint "easyedapro:R0603")
      (libsource (lib "easyedapro") (part "Res"))
    )
    (comp (ref "R44") (value "0") (footprint "easyedapro:R0603") (libsource (lib "easyedapro") (part "Res")))
    (comp (ref "R45")
      (value "120")
      (footprint "easyedapro:R0603")
      (libsource (lib "easyedapro") (part "Res"))
    )
    (comp (ref "R46")
      (value "120")
      (footprint "easyedapro:R0603")
      (libsource (lib "easyedapro") (part "Res"))
    )
    (comp (ref "R47") (value "22") (footprint "easyedapro:R0603") (libsource (lib "easyedapro") (part "Res")))
    (comp (ref "R48") (value "22") (footprint "easyedapro:R0603") (libsource (lib "easyedapro") (part "Res")))
    (comp (ref "U9")
      (value "USB-C Connector")
      (footprint "easyedapro:USB-C-SMD_GT-USB-7010E-1")
      (fields (field (name "Manufacturer Part") "USB-3.1插座TYPE-C母座"))
      (libsource (lib "easyedapro") (part "USB-3.1TYPE-C"))
    )
    (comp (ref "U17")
      (value "SM06B-SRSS-TB")
      (footprint "easyedapro:CONN-SMD_SM06B-SRSS-TBLFSN")
      (fields (field (name "Manufacturer") "JST"))
      (libsource (lib "easyedapro") (part "SM06B-SRSS-TB"))
    )
    (comp (ref "U18")
      (value "LTC4417IUF#PBF")
      (footprint "easyedapro:QFN-24_L4.0-W4.0-P0.50-TL-EP2.5")
      (fields (field (name "Manufacturer") "ADI(亚德诺)"))
      (libsource (lib "easyedapro") (part "LTC4417IUF#PBF"))
    )
    (comp (ref "U19")
      (value "SM06B-SRSS-TB")
      (footprint "easyedapro:CONN-SMD_SM06B-SRSS-TBLFSN")
      (fields (field (name "Manufacturer") "JST"))
      (libsource (lib "easyedapro") (part "SM06B-SRSS-TB"))
    )
    (comp (ref "U29")
      (value "42pF")
      (footprint "easyedapro:SOT-563_L1.6-W1.2-P0.50-LS1.6-TL")
      (fields (field (name "Manufacturer Part") "NUF2042XV6T1G") (field (name "Manufacturer") "onsemi(安森美)"))
      (libsource (lib "easyedapro") (part "NUF2042XV6T1G"))
    )
    (comp (ref "C59")
      (value "100uF")
      (footprint "easyedapro:C0201")
      (libsource (lib "easyedapro") (part "CAP"))
    )
    (comp (ref "C60")
      (value "100uF")
      (footprint "easyedapro:C0201")
      (libsource (lib "easyedapro") (part "CAP"))
    )
    (comp (ref "C61")
      (value "100uF")
      (footprint "easyedapro:C0201")
      (libsource (lib "easyedapro") (part "CAP"))
    )
    (comp (ref "C66")
      (value "100uF")
      (footprint "easyedapro:C0201")
      (libsource (lib "easyedapro") (part "CAP"))
    )
    (comp (ref "C67")
      (value "100uF")
      (footprint "easyedapro:C0201")
      (libsource (lib "easyedapro") (part "CAP"))
    )
    (comp (ref "C68")
      (value "100uF")
      (footprint "easyedapro:C0201")
      (libsource (lib "easyedapro") (part "CAP"))
    )
    (comp (ref "C78")
      (value "NFM18PC104R1C3D")
      (footprint "easyedapro:FILTER-SMD_3P-L1.6-W0.8-L_NFM18CC223R1C3D")
      (fields (field (name "Manufacturer") "muRata(村田)"))
      (libsource (lib "easyedapro") (part "NFM18PC104R1C3D"))
    )
    (comp (ref "C86")
      (value "10uF")
      (footprint "easyedapro:C0201")
      (libsource (lib "easyedapro") (part "CAP"))
    )
    (comp (ref "C87")
      (value "22uF")
      (footprint "easyedapro:C0201")
      (libsource (lib "easyedapro") (part "CAP"))
    )
    (comp (ref "C88")
      (value "1nF")
      (footprint "easyedapro:C0201")
      (libsource (lib "easyedapro") (part "CAP"))
    )
    (comp (ref "C89")
      (value "22uF")
      (footprint "easyedapro:C0201")
      (libsource (lib "easyedapro") (part "CAP"))
    )
    (comp (ref "C90")
      (value "100nF")
      (footprint "easyedapro:C0201")
      (libsource (lib "easyedapro") (part "CAP"))
    )
    (comp (ref "C91")
      (value "22uF")
      (footprint "easyedapro:C0201")
      (libsource (lib "easyedapro") (part "CAP"))
    )
    (comp (ref "C150")
      (value "100nF")
      (footprint "easyedapro:C0201")
      (libsource (lib "easyedapro") (part "CAP"))
    )
    (comp (ref "C151")
      (value "10nF")
      (footprint "easyedapro:C0201")
      (libsource (lib "easyedapro") (part "CAP"))
    )
    (comp (ref "C152")
      (value "100nF")
      (footprint "easyedapro:C0201")
      (libsource (lib "easyedapro") (part "CAP"))
    )
    (comp (ref "C153")
      (value "47nF")
      (footprint "easyedapro:C0201")
      (libsource (lib "easyedapro") (part "CAP"))
    )
    (comp (ref "C154")
      (value "100nF")
      (footprint "easyedapro:C0201")
      (libsource (lib "easyedapro") (part "CAP"))
    )
    (comp (ref "C156")
      (value "100nF")
      (footprint "easyedapro:C0201")
      (libsource (lib "easyedapro") (part "CAP"))
    )
    (comp (ref "C157")
      (value "47nF")
      (footprint "easyedapro:C0201")
      (libsource (lib "easyedapro") (part "CAP"))
    )
    (comp (ref "C158")
      (value "NFM18PC104R1C3D")
      (footprint "easyedapro:FILTER-SMD_3P-L1.6-W0.8-L_NFM18CC223R1C3D")
      (fields (field (name "Manufacturer") "muRata(村田)"))
      (libsource (lib "easyedapro") (part "NFM18PC104R1C3D"))
    )
    (comp (ref "C159")
      (value "10uF")
      (footprint "easyedapro:C0201")
      (libsource (lib "easyedapro") (part "CAP"))
    )
    (comp (ref "C160")
      (value "100nF")
      (footprint "easyedapro:C0201")
      (libsource (lib "easyedapro") (part "CAP"))
    )
    (comp (ref "C161")
      (value "100nF")
      (footprint "easyedapro:C0201")
      (libsource (lib "easyedapro") (part "CAP"))
    )
    (comp (ref "C162")
      (value "10nF")
      (footprint "easyedapro:C0201")
      (libsource (lib "easyedapro") (part "CAP"))
    )
    (comp (ref "C163")
      (value "100nF")
      (footprint "easyedapro:C0201")
      (libsource (lib "easyedapro") (part "CAP"))
    )
    (comp (ref "C180")
      (value "NFM18PC104R1C3D")
      (footprint "easyedapro:FILTER-SMD_3P-L1.6-W0.8-L_NFM18CC223R1C3D")
      (fields (field (name "Manufacturer") "muRata(村田)"))
      (libsource (lib "easyedapro") (part "NFM18PC104R1C3D"))
    )
    (comp (ref "C181")
      (value "1uF")
      (footprint "easyedapro:C0201")
      (libsource (lib "easyedapro") (part "CAP"))
    )
    (comp (ref "C182")
      (value "10uF")
      (footprint "easyedapro:C0201")
      (libsource (lib "easyedapro") (part "CAP"))
    )
    (comp (ref "C183")
      (value "10uF")
      (footprint "easyedapro:C0201")
      (libsource (lib "easyedapro") (part "CAP"))
    )
    (comp (ref "C184")
      (value "10uF")
      (footprint "easyedapro:C0201")
      (libsource (lib "easyedapro") (part "CAP"))
    )
    (comp (ref "C185")
      (value "10uF")
      (footprint "easyedapro:C0201")
      (libsource (lib "easyedapro") (part "CAP"))
    )
    (comp (ref "C186")
      (value "NFM18PC104R1C3D")
      (footprint "easyedapro:FILTER-SMD_3P-L1.6-W0.8-L_NFM18CC223R1C3D")
      (fields (field (name "Manufacturer") "muRata(村田)"))
      (libsource (lib "easyedapro") (part "NFM18PC104R1C3D"))
    )
    (comp (ref "C187")
      (value "1uF")
      (footprint "easyedapro:C0201")
      (libsource (lib "easyedapro") (part "CAP"))
    )
    (comp (ref "C188")
      (value "10uF")
      (footprint "easyedapro:C0201")
      (libsource (lib "easyedapro") (part "CAP"))
    )
    (comp (ref "C189")
      (value "10uF")
      (footprint "easyedapro:C0201")
      (libsource (lib "easyedapro") (part "CAP"))
    )
    (comp (ref "C190")
      (value "10uF")
      (footprint "easyedapro:C0201")
      (libsource (lib "easyedapro") (part "CAP"))
    )
    (comp (ref "C191")
      (value "10uF")
      (footprint "easyedapro:C0201")
      (libsource (lib "easyedapro") (part "CAP"))
    )
    (comp (ref "C192")
      (value "NFM18PC104R1C3D")
      (footprint "easyedapro:FILTER-SMD_3P-L1.6-W0.8-L_NFM18CC223R1C3D")
      (fields (field (name "Manufacturer") "muRata(村田)"))
      (libsource (lib "easyedapro") (part "NFM18PC104R1C3D"))
    )
    (comp (ref "C193")
      (value "1uF")
      (footprint "easyedapro:C0201")
      (libsource (lib "easyedapro") (part "CAP"))
    )
    (comp (ref "C194")
      (value "10uF")
      (footprint "easyedapro:C0201")
      (libsource (lib "easyedapro") (part "CAP"))
    )
    (comp (ref "C195")
      (value "10uF")
      (footprint "easyedapro:C0201")
      (libsource (lib "easyedapro") (part "CAP"))
    )
    (comp (ref "C196")
      (value "10uF")
      (footprint "easyedapro:C0201")
      (libsource (lib "easyedapro") (part "CAP"))
    )
    (comp (ref "C197")
      (value "10uF")
      (footprint "easyedapro:C0201")
      (libsource (lib "easyedapro") (part "CAP"))
    )
    (comp (ref "C198")
      (value "NFM18PC104R1C3D")
      (footprint "easyedapro:FILTER-SMD_3P-L1.6-W0.8-L_NFM18CC223R1C3D")
      (fields (field (name "Manufacturer") "muRata(村田)"))
      (libsource (lib "easyedapro") (part "NFM18PC104R1C3D"))
    )
    (comp (ref "C199")
      (value "1uF")
      (footprint "easyedapro:C0201")
      (libsource (lib "easyedapro") (part "CAP"))
    )
    (comp (ref "C200")
      (value "10uF")
      (footprint "easyedapro:C0201")
      (libsource (lib "easyedapro") (part "CAP"))
    )
    (comp (ref "C201")
      (value "10uF")
      (footprint "easyedapro:C0201")
      (libsource (lib "easyedapro") (part "CAP"))
    )
    (comp (ref "C202")
      (value "10uF")
      (footprint "easyedapro:C0201")
      (libsource (lib "easyedapro") (part "CAP"))
    )
    (comp (ref "C203")
      (value "10uF")
      (footprint "easyedapro:C0201")
      (libsource (lib "easyedapro") (part "CAP"))
    )
    (comp (ref "L1") (value "1uH") (footprint "easyedapro:L0402") (libsource (lib "easyedapro") (part "电感")))
    (comp (ref "R49")
      (value "47K")
      (footprint "easyedapro:R0603")
      (libsource (lib "easyedapro") (part "Res"))
    )
    (comp (ref "R50")
      (value "47K")
      (footprint "easyedapro:R0603")
      (libsource (lib "easyedapro") (part "Res"))
    )
    (comp (ref "R51")
      (value "16.9K")
      (footprint "easyedapro:R0603")
      (libsource (lib "easyedapro") (part "Res"))
    )
    (comp (ref "R52")
      (value "47K")
      (footprint "easyedapro:R0603")
      (libsource (lib "easyedapro") (part "Res"))
    )
    (comp (ref "R54")
      (value "47K")
      (footprint "easyedapro:R0603")
      (libsource (lib "easyedapro") (part "Res"))
    )
    (comp (ref "R55")
      (value "47K")
      (footprint "easyedapro:R0603")
      (libsource (lib "easyedapro") (part "Res"))
    )
    (comp (ref "R56")
      (value "16.9K")
      (footprint "easyedapro:R0603")
      (libsource (lib "easyedapro") (part "Res"))
    )
    (comp (ref "R57")
      (value "47K")
      (footprint "easyedapro:R0603")
      (libsource (lib "easyedapro") (part "Res"))
    )
    (comp (ref "R73")
      (value "7.15K")
      (footprint "easyedapro:R0603")
      (libsource (lib "easyedapro") (part "Res"))
    )
    (comp (ref "R74")
      (value "499K")
      (footprint "easyedapro:R0603")
      (libsource (lib "easyedapro") (part "Res"))
    )
    (comp (ref "R75")
      (value "100K")
      (footprint "easyedapro:R0603")
      (libsource (lib "easyedapro") (part "Res"))
    )
    (comp (ref "R76")
      (value "100K")
      (footprint "easyedapro:R0603")
      (libsource (lib "easyedapro") (part "Res"))
    )
    (comp (ref "R77")
      (value "3.6K")
      (footprint "easyedapro:R0603")
      (libsource (lib "easyedapro") (part "Res"))
    )
    (comp (ref "R78")
      (value "1.15K")
      (footprint "easyedapro:R0603")
      (libsource (lib "easyedapro") (part "Res"))
    )
    (comp (ref "R148")
      (value "10K")
      (footprint "easyedapro:R0603")
      (libsource (lib "easyedapro") (part "Res"))
    )
    (comp (ref "R149")
      (value "47K")
      (footprint "easyedapro:R0603")
      (libsource (lib "easyedapro") (part "Res"))
    )
    (comp (ref "R150")
      (value "10K")
      (footprint "easyedapro:R0603")
      (libsource (lib "easyedapro") (part "Res"))
    )
    (comp (ref "R151")
      (value "10K")
      (footprint "easyedapro:R0603")
      (libsource (lib "easyedapro") (part "Res"))
    )
    (comp (ref "R152")
      (value "10K")
      (footprint "easyedapro:R0603")
      (libsource (lib "easyedapro") (part "Res"))
    )
    (comp (ref "R165")
      (value "10K")
      (footprint "easyedapro:R0603")
      (libsource (lib "easyedapro") (part "Res"))
    )
    (comp (ref "R166")
      (value "10K")
      (footprint "easyedapro:R0603")
      (libsource (lib "easyedapro") (part "Res"))
    )
    (comp (ref "R167")
      (value "10K")
      (footprint "easyedapro:R0603")
      (libsource (lib "easyedapro") (part "Res"))
    )
    (comp (ref "R168")
      (value "10K")
      (footprint "easyedapro:R0603")
      (libsource (lib "easyedapro") (part "Res"))
    )
    (comp (ref "R169")
      (value "10K")
      (footprint "easyedapro:R0603")
      (libsource (lib "easyedapro") (part "Res"))
    )
    (comp (ref "R170")
      (value "10K")
      (footprint "easyedapro:R0603")
      (libsource (lib "easyedapro") (part "Res"))
    )
    (comp (ref "R171")
      (value "10K")
      (footprint "easyedapro:R0603")
      (libsource (lib "easyedapro") (part "Res"))
    )
    (comp (ref "R172")
      (value "10K")
      (footprint "easyedapro:R0603")
      (libsource (lib "easyedapro") (part "Res"))
    )
    (comp (ref "R173")
      (value "10K")
      (footprint "easyedapro:R0603")
      (libsource (lib "easyedapro") (part "Res"))
    )
    (comp (ref "R174")
      (value "10K")
      (footprint "easyedapro:R0603")
      (libsource (lib "easyedapro") (part "Res"))
    )
    (comp (ref "R175")
      (value "10K")
      (footprint "easyedapro:R0603")
      (libsource (lib "easyedapro") (part "Res"))
    )
    (comp (ref "R176")
      (value "10K")
      (footprint "easyedapro:R0603")
      (libsource (lib "easyedapro") (part "Res"))
    )
    (comp (ref "U20")
      (value "BQ24315DSGR")
      (footprint "easyedapro:WSON-8_L2.0-W2.0-P0.65-BL-EP")
      (fields (field (name "Manufacturer") "TI(德州仪器)"))
      (libsource (lib "easyedapro") (part "BQ24315DSGR"))
    )
    (comp (ref "U23")
      (value "BQ24315DSGR")
      (footprint "easyedapro:WSON-8_L2.0-W2.0-P0.65-BL-EP")
      (fields (field (name "Manufacturer") "TI(德州仪器)"))
      (libsource (lib "easyedapro") (part "BQ24315DSGR"))
    )
    (comp (ref "U26")
      (value "TPS62903QRYTRQ1")
      (footprint "easyedapro:VQFNHR-9_L2.2-W2.0_TPS62993QRYTRQ1")
      (fields (field (name "Manufacturer") "TI(德州仪器)"))
      (libsource (lib "easyedapro") (part "TPS62903QRYTRQ1_C20345985"))
    )
    (comp (ref "U27")
      (value "TPS7A9201DSKR")
      (footprint "easyedapro:TDFN-10_L2.5-W2.5-P0.50-BL-EP")
      (fields (field (name "Manufacturer") "TI(德州仪器)"))
      (libsource (lib "easyedapro") (part "TPS7A9201DSKR"))
    )
    (comp (ref "U42")
      (value "MIC5332-SSYMT-TR")
      (footprint "easyedapro:MLF-8_L2.0-W2.0-P0.50-BL-EP")
      (fields (field (name "Manufacturer") "MICROCHIP(美国微芯)"))
      (libsource (lib "easyedapro") (part "MIC5332-SSYMT-TR"))
    )
    (comp (ref "U43")
      (value "MIC5332-SSYMT-TR")
      (footprint "easyedapro:MLF-8_L2.0-W2.0-P0.50-BL-EP")
      (fields (field (name "Manufacturer") "MICROCHIP(美国微芯)"))
      (libsource (lib "easyedapro") (part "MIC5332-SSYMT-TR"))
    )
    (comp (ref "U48")
      (value "LP5907MFX-3.3/NOPB")
      (footprint "easyedapro:SOT-23-5_L3.0-W1.7-P0.95-LS2.8-BR")
      (fields (field (name "Manufacturer") "TI(德州仪器)"))
      (libsource (lib "easyedapro") (part "LP5907MFX-3.3/NOPB"))
    )
    (comp (ref "U49")
      (value "LP5907MFX-3.3/NOPB")
      (footprint "easyedapro:SOT-23-5_L3.0-W1.7-P0.95-LS2.8-BR")
      (fields (field (name "Manufacturer") "TI(德州仪器)"))
      (libsource (lib "easyedapro") (part "LP5907MFX-3.3/NOPB"))
    )
    (comp (ref "U50")
      (value "LP5907MFX-3.3/NOPB")
      (footprint "easyedapro:SOT-23-5_L3.0-W1.7-P0.95-LS2.8-BR")
      (fields (field (name "Manufacturer") "TI(德州仪器)"))
      (libsource (lib "easyedapro") (part "LP5907MFX-3.3/NOPB"))
    )
    (comp (ref "U51")
      (value "LP5907MFX-3.3/NOPB")
      (footprint "easyedapro:SOT-23-5_L3.0-W1.7-P0.95-LS2.8-BR")
      (fields (field (name "Manufacturer") "TI(德州仪器)"))
      (libsource (lib "easyedapro") (part "LP5907MFX-3.3/NOPB"))
    )
    (comp (ref "C1")
      (value "20pF")
      (footprint "easyedapro:C0201")
      (libsource (lib "easyedapro") (part "CAP"))
    )
    (comp (ref "C2")
      (value "20pF")
      (footprint "easyedapro:C0201")
      (libsource (lib "easyedapro") (part "CAP"))
    )
    (comp (ref "C3")
      (value "12pF")
      (footprint "easyedapro:C0201")
      (libsource (lib "easyedapro") (part "CAP"))
    )
    (comp (ref "C4")
      (value "12pF")
      (footprint "easyedapro:C0201")
      (libsource (lib "easyedapro") (part "CAP"))
    )
    (comp (ref "C5")
      (value "100nF")
      (footprint "easyedapro:C0201")
      (libsource (lib "easyedapro") (part "CAP"))
    )
    (comp (ref "C12")
      (value "4.7uF")
      (footprint "easyedapro:C0201")
      (libsource (lib "easyedapro") (part "CAP"))
    )
    (comp (ref "C13")
      (value "100nF")
      (footprint "easyedapro:C0201")
      (libsource (lib "easyedapro") (part "CAP"))
    )
    (comp (ref "C14")
      (value "100nF")
      (footprint "easyedapro:C0201")
      (libsource (lib "easyedapro") (part "CAP"))
    )
    (comp (ref "C15")
      (value "100nF")
      (footprint "easyedapro:C0201")
      (libsource (lib "easyedapro") (part "CAP"))
    )
    (comp (ref "C16")
      (value "100nF")
      (footprint "easyedapro:C0201")
      (libsource (lib "easyedapro") (part "CAP"))
    )
    (comp (ref "C17")
      (value "100nF")
      (footprint "easyedapro:C0201")
      (libsource (lib "easyedapro") (part "CAP"))
    )
    (comp (ref "C18")
      (value "100nF")
      (footprint "easyedapro:C0201")
      (libsource (lib "easyedapro") (part "CAP"))
    )
    (comp (ref "C19")
      (value "100nF")
      (footprint "easyedapro:C0201")
      (libsource (lib "easyedapro") (part "CAP"))
    )
    (comp (ref "C20")
      (value "100nF")
      (footprint "easyedapro:C0201")
      (libsource (lib "easyedapro") (part "CAP"))
    )
    (comp (ref "C21")
      (value "100nF")
      (footprint "easyedapro:C0201")
      (libsource (lib "easyedapro") (part "CAP"))
    )
    (comp (ref "C22")
      (value "100nF")
      (footprint "easyedapro:C0201")
      (libsource (lib "easyedapro") (part "CAP"))
    )
    (comp (ref "C23")
      (value "1uF")
      (footprint "easyedapro:C0201")
      (libsource (lib "easyedapro") (part "CAP"))
    )
    (comp (ref "C24")
      (value "1uF")
      (footprint "easyedapro:C0201")
      (libsource (lib "easyedapro") (part "CAP"))
    )
    (comp (ref "C25")
      (value "100nF")
      (footprint "easyedapro:C0201")
      (libsource (lib "easyedapro") (part "CAP"))
    )
    (comp (ref "C39")
      (value "100nF")
      (footprint "easyedapro:C0201")
      (libsource (lib "easyedapro") (part "CAP"))
    )
    (comp (ref "C40")
      (value "2.2F")
      (footprint "easyedapro:C0201")
      (libsource (lib "easyedapro") (part "CAP"))
    )
    (comp (ref "C41")
      (value "1uF")
      (footprint "easyedapro:C0201")
      (libsource (lib "easyedapro") (part "CAP"))
    )
    (comp (ref "C42")
      (value "1uF")
      (footprint "easyedapro:C0201")
      (libsource (lib "easyedapro") (part "CAP"))
    )
    (comp (ref "C43")
      (value "2.2uF")
      (footprint "easyedapro:C0201")
      (libsource (lib "easyedapro") (part "CAP"))
    )
    (comp (ref "C44")
      (value "2.2uF")
      (footprint "easyedapro:C0201")
      (libsource (lib "easyedapro") (part "CAP"))
    )
    (comp (ref "C95")
      (value "100nF")
      (footprint "easyedapro:C0201")
      (libsource (lib "easyedapro") (part "CAP"))
    )
    (comp (ref "C96")
      (value "2.2F")
      (footprint "easyedapro:C0201")
      (libsource (lib "easyedapro") (part "CAP"))
    )
    (comp (ref "C103")
      (value "2.2uF")
      (footprint "easyedapro:C0201")
      (libsource (lib "easyedapro") (part "CAP"))
    )
    (comp (ref "C104")
      (value "2.2uF")
      (footprint "easyedapro:C0201")
      (libsource (lib "easyedapro") (part "CAP"))
    )
    (comp (ref "CN11")
      (value "BM04B-GHS-TBT")
      (footprint "easyedapro:CONN-SMD_4P-P1.25_BM04B-GHS-TBT-LF-SN")
      (fields (field (name "Manufacturer") "JST"))
      (libsource (lib "easyedapro") (part "BM04B-GHS-TBT"))
    )
    (comp (ref "CN14")
      (value "BM04B-GHS-TBT")
      (footprint "easyedapro:CONN-SMD_4P-P1.25_BM04B-GHS-TBT-LF-SN")
      (fields (field (name "Manufacturer") "JST"))
      (libsource (lib "easyedapro") (part "BM04B-GHS-TBT"))
    )
    (comp (ref "D1")
      (value "ESDALC6V1-1U2")
      (footprint "easyedapro:DFN0603-D_L0.6-W0.3-P0.34-RD")
      (fields (field (name "Manufacturer") "ST(意法半导体)"))
      (libsource (lib "easyedapro") (part "ESDALC6V1-1U2"))
    )
    (comp (ref "D2")
      (value "ESD7104MUTAG-ES")
      (footprint "easyedapro:DFN-10_L2.5-W1.0-P0.50-BL")
      (fields (field (name "Manufacturer") "ElecSuper(静芯)"))
      (libsource (lib "easyedapro") (part "ESD7104MUTAG-ES"))
    )
    (comp (ref "D3")
      (value "BAS70KFILM")
      (footprint "easyedapro:SOD-523_L1.2-W0.8-LS1.6-RD")
      (fields (field (name "Manufacturer") "ST(意法半导体)"))
      (libsource (lib "easyedapro") (part "BAS70KFILM"))
    )
    (comp (ref "D34")
      (value "~")
      (footprint "easyedapro:SMA_L4.4-W2.8-LS5.4-RD")
      (libsource (lib "easyedapro") (part "D_1N4007"))
    )
    (comp (ref "H1")
      (value "~")
      (footprint "easyedapro:HDR-TH_6P-P2.54-V-F")
      (libsource (lib "easyedapro") (part "Header-Female-2.54_1x6"))
    )
    (comp (ref "H19")
      (value "~")
      (footprint "easyedapro:HDR-TH_4P-P2.54-V-F")
      (libsource (lib "easyedapro") (part "2.54-1*4P母"))
    )
    (comp (ref "H20")
      (value "~")
      (footprint "easyedapro:HDR-TH_4P-P2.54-V-F")
      (libsource (lib "easyedapro") (part "2.54-1*4P母"))
    )
    (comp (ref "JP1")
      (value "~")
      (footprint "easyedapro:HDR-TH_2P-P2.54-V-M-2")
      (libsource (lib "easyedapro") (part "HDR-M-2.54_2x1"))
    )
    (comp (ref "JP2")
      (value "~")
      (footprint "easyedapro:HDR-TH_2P-P2.54-V-M-2")
      (libsource (lib "easyedapro") (part "HDR-M-2.54_2x1"))
    )
    (comp (ref "JP3")
      (value "~")
      (footprint "easyedapro:HDR-TH_2P-P2.54-V-M-2")
      (libsource (lib "easyedapro") (part "HDR-M-2.54_2x1"))
    )
    (comp (ref "JP4")
      (value "~")
      (footprint "easyedapro:HDR-TH_2P-P2.54-V-M-2")
      (libsource (lib "easyedapro") (part "HDR-M-2.54_2x1"))
    )
    (comp (ref "L3")
      (value "FBMH1608HM601-TV")
      (footprint "easyedapro:L0603")
      (fields (field (name "Manufacturer") "TAIYO YUDEN(太诱)"))
      (libsource (lib "easyedapro") (part "FBMH1608HM601-TV"))
    )
    (comp (ref "LED1")
      (value "~")
      (footprint "easyedapro:LED0402-RD_YELLOW")
      (libsource (lib "easyedapro") (part "LED_B"))
    )
    (comp (ref "LED2")
      (value "~")
      (footprint "easyedapro:LED0402-RD_YELLOW")
      (libsource (lib "easyedapro") (part "LED_R"))
    )
    (comp (ref "LED3")
      (value "~")
      (footprint "easyedapro:LED0402-RD_YELLOW")
      (libsource (lib "easyedapro") (part "LED_G"))
    )
    (comp (ref "R1") (value "10K") (footprint "easyedapro:R0603") (libsource (lib "easyedapro") (part "Res")))
    (comp (ref "R6") (value "10K") (footprint "easyedapro:R0603") (libsource (lib "easyedapro") (part "Res")))
    (comp (ref "R7") (value "10K") (footprint "easyedapro:R0603") (libsource (lib "easyedapro") (part "Res")))
    (comp (ref "R14")
      (value "100K")
      (footprint "easyedapro:R0603")
      (libsource (lib "easyedapro") (part "Res"))
    )
    (comp (ref "R15")
      (value "100K")
      (footprint "easyedapro:R0603")
      (libsource (lib "easyedapro") (part "Res"))
    )
    (comp (ref "R16")
      (value "100K")
      (footprint "easyedapro:R0603")
      (libsource (lib "easyedapro") (part "Res"))
    )
    (comp (ref "R17")
      (value "100K")
      (footprint "easyedapro:R0603")
      (libsource (lib "easyedapro") (part "Res"))
    )
    (comp (ref "R18")
      (value "100K")
      (footprint "easyedapro:R0603")
      (libsource (lib "easyedapro") (part "Res"))
    )
    (comp (ref "R31")
      (value "120")
      (footprint "easyedapro:R0603")
      (libsource (lib "easyedapro") (part "Res"))
    )
    (comp (ref "R80")
      (value "442K")
      (footprint "easyedapro:R0603")
      (libsource (lib "easyedapro") (part "Res"))
    )
    (comp (ref "R81")
      (value "442K")
      (footprint "easyedapro:R0603")
      (libsource (lib "easyedapro") (part "Res"))
    )
    (comp (ref "R82")
      (value "24.9K")
      (footprint "easyedapro:R0603")
      (libsource (lib "easyedapro") (part "Res"))
    )
    (comp (ref "R83")
      (value "24.9K")
      (footprint "easyedapro:R0603")
      (libsource (lib "easyedapro") (part "Res"))
    )
    (comp (ref "R84")
      (value "2.2K")
      (footprint "easyedapro:R0603")
      (libsource (lib "easyedapro") (part "Res"))
    )
    (comp (ref "R85")
      (value "2.2K")
      (footprint "easyedapro:R0603")
      (libsource (lib "easyedapro") (part "Res"))
    )
    (comp (ref "R86")
      (value "2.2K")
      (footprint "easyedapro:R0603")
      (libsource (lib "easyedapro") (part "Res"))
    )
    (comp (ref "R87")
      (value "120")
      (footprint "easyedapro:R0603")
      (libsource (lib "easyedapro") (part "Res"))
    )
    (comp (ref "R88")
      (value "10K")
      (footprint "easyedapro:R0603")
      (libsource (lib "easyedapro") (part "Res"))
    )
    (comp (ref "R89")
      (value "10K")
      (footprint "easyedapro:R0603")
      (libsource (lib "easyedapro") (part "Res"))
    )
    (comp (ref "R90")
      (value "1.5K")
      (footprint "easyedapro:R0603")
      (libsource (lib "easyedapro") (part "Res"))
    )
    (comp (ref "R91")
      (value "1.5K")
      (footprint "easyedapro:R0603")
      (libsource (lib "easyedapro") (part "Res"))
    )
    (comp (ref "R92")
      (value "1.5K")
      (footprint "easyedapro:R0603")
      (libsource (lib "easyedapro") (part "Res"))
    )
    (comp (ref "R93")
      (value "1.5K")
      (footprint "easyedapro:R0603")
      (libsource (lib "easyedapro") (part "Res"))
    )
    (comp (ref "R94")
      (value "1.5K")
      (footprint "easyedapro:R0603")
      (libsource (lib "easyedapro") (part "Res"))
    )
    (comp (ref "R95")
      (value "1.5K")
      (footprint "easyedapro:R0603")
      (libsource (lib "easyedapro") (part "Res"))
    )
    (comp (ref "R177")
      (value "220")
      (footprint "easyedapro:R0603")
      (libsource (lib "easyedapro") (part "Res"))
    )
    (comp (ref "SW1")
      (value "~")
      (footprint "easyedapro:SW-SMD_4P-L6.0-W6.0-P4.50-LS9.0-2")
      (libsource (lib "easyedapro") (part "轻触按键"))
    )
    (comp (ref "SW2")
      (value "~")
      (footprint "easyedapro:SW-SMD_4P-L6.0-W6.0-P4.50-LS9.0-2")
      (libsource (lib "easyedapro") (part "轻触按键"))
    )
    (comp (ref "TF1")
      (value "M6014-12")
      (footprint "easyedapro:TF-SMD_M6014-12")
      (fields (field (name "Manufacturer") "MUP(德海威)"))
      (libsource (lib "easyedapro") (part "M6014-12"))
    )
    (comp (ref "U3")
      (value "16MHz")
      (footprint "easyedapro:CRYSTAL-SMD_4P-L3.2-W2.5-BL")
      (fields
        (field (name "Manufacturer Part") "CX3225CA16000D0HSSCC")
        (field (name "Manufacturer") "Kyocera AVX")
      )
      (libsource (lib "easyedapro") (part "CX3225CA16000D0HSSCC"))
    )
    (comp (ref "U5")
      (value "FM25V02A-G")
      (footprint "easyedapro:SOIC-8_L4.9-W3.9-P1.27-LS6.0-BL")
      (libsource (lib "easyedapro") (part "FM25V02A-G"))
    )
    (comp (ref "U15")
      (value "TJA1051TK/3,118")
      (footprint "easyedapro:HVSON-8_L3.0-W3.0-P0.65-BL-EP")
      (description "Type:Transceiver Data Rate:5Mbps Supply Voltage:4.5V~5.5V Supply Voltage:4.5V~5.5V")
      (fields (field (name "Manufacturer") "NXP(恩智浦)"))
      (libsource (lib "easyedapro") (part "TJA1051TK/3,118"))
    )
    (comp (ref "U16")
      (value "LP5907UVX-4.5/NOPB")
      (footprint "easyedapro:DSBGA-4_L0.7-W0.7-R2-C2-P0.35-BL")
      (libsource (lib "easyedapro") (part "LP5907UVX-4.5/NOPB"))
    )
    (comp (ref "U28")
      (value "STM32H753IIK6")
      (footprint "easyedapro:UFBGA-201_L10.0-W10.0-P0.65-TL_STM32H743IIK6")
      (fields (field (name "Manufacturer") "ST(意法半导体)"))
      (libsource (lib "easyedapro") (part "STM32H753IIK6"))
    )
    (comp (ref "U30")
      (value "SM06B-SRSS-TB")
      (footprint "easyedapro:CONN-SMD_SM06B-SRSS-TBLFSN")
      (fields (field (name "Manufacturer") "JST"))
      (libsource (lib "easyedapro") (part "SM06B-SRSS-TB"))
    )
    (comp (ref "U32")
      (value "TJA1051TK/3,118")
      (footprint "easyedapro:HVSON-8_L3.0-W3.0-P0.65-BL-EP")
      (description "Type:Transceiver Data Rate:5Mbps Supply Voltage:4.5V~5.5V Supply Voltage:4.5V~5.5V")
      (fields (field (name "Manufacturer") "NXP(恩智浦)"))
      (libsource (lib "easyedapro") (part "TJA1051TK/3,118"))
    )
    (comp (ref "U52")
      (value "MS621FE-FL11E")
      (footprint "easyedapro:BAT-SMD_FL11E")
      (fields (field (name "Manufacturer") "Seiko(精工)"))
      (libsource (lib "easyedapro") (part "MS621FE-FL11E"))
    )
    (comp (ref "X1")
      (value "32.768kHz")
      (footprint "easyedapro:FC-135R_L3.2-W1.5")
      (fields (field (name "Manufacturer Part") "Q13FC13500004") (field (name "Manufacturer") "EPSON(爱普生)"))
      (libsource (lib "easyedapro") (part "Q13FC1350000400"))
    )
    (comp (ref "C35")
      (value "100nF")
      (footprint "easyedapro:C0201")
      (libsource (lib "easyedapro") (part "CAP"))
    )
    (comp (ref "C36")
      (value "100nF")
      (footprint "easyedapro:C0201")
      (libsource (lib "easyedapro") (part "CAP"))
    )
    (comp (ref "C92")
      (value "0.1uF")
      (footprint "easyedapro:C0201")
      (libsource (lib "easyedapro") (part "CAP"))
    )
    (comp (ref "C93")
      (value "0.1uF")
      (footprint "easyedapro:C0201")
      (libsource (lib "easyedapro") (part "CAP"))
    )
    (comp (ref "C94")
      (value "0.1uF")
      (footprint "easyedapro:C0201")
      (libsource (lib "easyedapro") (part "CAP"))
    )
    (comp (ref "JP5")
      (value "~")
      (footprint "easyedapro:HDR-TH_2P-P2.54-V-M-2")
      (libsource (lib "easyedapro") (part "HDR-M-2.54_2x1"))
    )
    (comp (ref "JP6")
      (value "~")
      (footprint "easyedapro:HDR-TH_2P-P2.54-V-M-2")
      (libsource (lib "easyedapro") (part "HDR-M-2.54_2x1"))
    )
    (comp (ref "JP7")
      (value "~")
      (footprint "easyedapro:HDR-TH_2P-P2.54-V-M-2")
      (libsource (lib "easyedapro") (part "HDR-M-2.54_2x1"))
    )
    (comp (ref "JP8")
      (value "~")
      (footprint "easyedapro:HDR-TH_2P-P2.54-V-M-2")
      (libsource (lib "easyedapro") (part "HDR-M-2.54_2x1"))
    )
    (comp (ref "JP9")
      (value "~")
      (footprint "easyedapro:HDR-TH_2P-P2.54-V-M-2")
      (libsource (lib "easyedapro") (part "HDR-M-2.54_2x1"))
    )
    (comp (ref "JP10")
      (value "~")
      (footprint "easyedapro:HDR-TH_2P-P2.54-V-M-2")
      (libsource (lib "easyedapro") (part "HDR-M-2.54_2x1"))
    )
    (comp (ref "JP23")
      (value "~")
      (footprint "easyedapro:HDR-TH_2P-P2.54-V-M-2")
      (libsource (lib "easyedapro") (part "HDR-M-2.54_2x1"))
    )
    (comp (ref "JP24")
      (value "~")
      (footprint "easyedapro:HDR-TH_2P-P2.54-V-M-2")
      (libsource (lib "easyedapro") (part "HDR-M-2.54_2x1"))
    )
    (comp (ref "JP25")
      (value "~")
      (footprint "easyedapro:HDR-TH_2P-P2.54-V-M-2")
      (libsource (lib "easyedapro") (part "HDR-M-2.54_2x1"))
    )
    (comp (ref "U13")
      (value "BMP388")
      (footprint "easyedapro:SENSORM-SMD_BMP388")
      (fields (field (name "Manufacturer") "Bosch(博世)"))
      (libsource (lib "easyedapro") (part "BMP388"))
    )
    (comp (ref "U31")
      (value "ICM-20649")
      (footprint "easyedapro:QFN-24_L3.0-W3.0-P0.40-TL-EP1.4")
      (fields (field (name "Manufacturer") "TDK InvenSense(应美盛)"))
      (libsource (lib "easyedapro") (part "ICM-20649"))
    )
    (comp (ref "C33")
      (value "100nF")
      (footprint "easyedapro:C0201")
      (libsource (lib "easyedapro") (part "CAP"))
    )
    (comp (ref "C34")
      (value "100nF")
      (footprint "easyedapro:C0201")
      (libsource (lib "easyedapro") (part "CAP"))
    )
    (comp (ref "C37")
      (value "100nF")
      (footprint "easyedapro:C0201")
      (libsource (lib "easyedapro") (part "CAP"))
    )
    (comp (ref "C38")
      (value "100nF")
      (footprint "easyedapro:C0201")
      (libsource (lib "easyedapro") (part "CAP"))
    )
    (comp (ref "C97")
      (value "100nF")
      (footprint "easyedapro:C0201")
      (libsource (lib "easyedapro") (part "CAP"))
    )
    (comp (ref "C98")
      (value "100nF")
      (footprint "easyedapro:C0201")
      (libsource (lib "easyedapro") (part "CAP"))
    )
    (comp (ref "C99")
      (value "10nF")
      (footprint "easyedapro:C0201")
      (libsource (lib "easyedapro") (part "CAP"))
    )
    (comp (ref "C100")
      (value "0.1uF")
      (footprint "easyedapro:C0201")
      (libsource (lib "easyedapro") (part "CAP"))
    )
    (comp (ref "C101")
      (value "2.2uF")
      (footprint "easyedapro:C0201")
      (libsource (lib "easyedapro") (part "CAP"))
    )
    (comp (ref "C102")
      (value "0.1uF")
      (footprint "easyedapro:C0201")
      (libsource (lib "easyedapro") (part "CAP"))
    )
    (comp (ref "H4")
      (value "~")
      (footprint "easyedapro:HDR-TH_1P-V-M_XKB_X4611WV-01I-C28D40")
      (libsource (lib "easyedapro") (part "HDR_1x1"))
    )
    (comp (ref "H5")
      (value "~")
      (footprint "easyedapro:HDR-TH_1P-V-M_XKB_X4611WV-01I-C28D40")
      (libsource (lib "easyedapro") (part "HDR_1x1"))
    )
    (comp (ref "H21")
      (value "~")
      (footprint "easyedapro:HDR-TH_1P-V-M_XKB_X4611WV-01I-C28D40")
      (libsource (lib "easyedapro") (part "HDR_1x1"))
    )
    (comp (ref "H22")
      (value "~")
      (footprint "easyedapro:HDR-TH_1P-V-M_XKB_X4611WV-01I-C28D40")
      (libsource (lib "easyedapro") (part "HDR_1x1"))
    )
    (comp (ref "H23")
      (value "~")
      (footprint "easyedapro:HDR-TH_1P-V-M_XKB_X4611WV-01I-C28D40")
      (libsource (lib "easyedapro") (part "HDR_1x1"))
    )
    (comp (ref "JP16")
      (value "~")
      (footprint "easyedapro:HDR-TH_2P-P2.54-V-M-2")
      (libsource (lib "easyedapro") (part "HDR-M-2.54_2x1"))
    )
    (comp (ref "JP17")
      (value "~")
      (footprint "easyedapro:HDR-TH_2P-P2.54-V-M-2")
      (libsource (lib "easyedapro") (part "HDR-M-2.54_2x1"))
    )
    (comp (ref "JP18")
      (value "~")
      (footprint "easyedapro:HDR-TH_2P-P2.54-V-M-2")
      (libsource (lib "easyedapro") (part "HDR-M-2.54_2x1"))
    )
    (comp (ref "JP19")
      (value "~")
      (footprint "easyedapro:HDR-TH_2P-P2.54-V-M-2")
      (libsource (lib "easyedapro") (part "HDR-M-2.54_2x1"))
    )
    (comp (ref "JP20")
      (value "~")
      (footprint "easyedapro:HDR-TH_2P-P2.54-V-M-2")
      (libsource (lib "easyedapro") (part "HDR-M-2.54_2x1"))
    )
    (comp (ref "JP21")
      (value "~")
      (footprint "easyedapro:HDR-TH_2P-P2.54-V-M-2")
      (libsource (lib "easyedapro") (part "HDR-M-2.54_2x1"))
    )
    (comp (ref "JP22")
      (value "~")
      (footprint "easyedapro:HDR-TH_2P-P2.54-V-M-2")
      (libsource (lib "easyedapro") (part "HDR-M-2.54_2x1"))
    )
    (comp (ref "JP26")
      (value "~")
      (footprint "easyedapro:HDR-TH_2P-P2.54-V-M-2")
      (libsource (lib "easyedapro") (part "HDR-M-2.54_2x1"))
    )
    (comp (ref "JP27")
      (value "~")
      (footprint "easyedapro:HDR-TH_2P-P2.54-V-M-2")
      (libsource (lib "easyedapro") (part "HDR-M-2.54_2x1"))
    )
    (comp (ref "JP28")
      (value "~")
      (footprint "easyedapro:HDR-TH_2P-P2.54-V-M-2")
      (libsource (lib "easyedapro") (part "HDR-M-2.54_2x1"))
    )
    (comp (ref "JP29")
      (value "~")
      (footprint "easyedapro:HDR-TH_2P-P2.54-V-M-2")
      (libsource (lib "easyedapro") (part "HDR-M-2.54_2x1"))
    )
    (comp (ref "JP30")
      (value "~")
      (footprint "easyedapro:HDR-TH_2P-P2.54-V-M-2")
      (libsource (lib "easyedapro") (part "HDR-M-2.54_2x1"))
    )
    (comp (ref "JP31")
      (value "~")
      (footprint "easyedapro:HDR-TH_2P-P2.54-V-M-2")
      (libsource (lib "easyedapro") (part "HDR-M-2.54_2x1"))
    )
    (comp (ref "JP32")
      (value "~")
      (footprint "easyedapro:HDR-TH_2P-P2.54-V-M-2")
      (libsource (lib "easyedapro") (part "HDR-M-2.54_2x1"))
    )
    (comp (ref "JP33")
      (value "~")
      (footprint "easyedapro:HDR-TH_2P-P2.54-V-M-2")
      (libsource (lib "easyedapro") (part "HDR-M-2.54_2x1"))
    )
    (comp (ref "JP34")
      (value "~")
      (footprint "easyedapro:HDR-TH_2P-P2.54-V-M-2")
      (libsource (lib "easyedapro") (part "HDR-M-2.54_2x1"))
    )
    (comp (ref "JP35")
      (value "~")
      (footprint "easyedapro:HDR-TH_2P-P2.54-V-M-2")
      (libsource (lib "easyedapro") (part "HDR-M-2.54_2x1"))
    )
    (comp (ref "JP36")
      (value "~")
      (footprint "easyedapro:HDR-TH_2P-P2.54-V-M-2")
      (libsource (lib "easyedapro") (part "HDR-M-2.54_2x1"))
    )
    (comp (ref "U12")
      (value "BMI088")
      (footprint "easyedapro:LGA-16_L4.5-W3.0-P0.50-BL")
      (description "Sensor Type:加速度计陀螺仪 Operating Temperature:-40°C~+85°C Operating Temperature:-40°C~+85°C")
      (fields (field (name "Manufacturer") "Bosch(博世)"))
      (libsource (lib "easyedapro") (part "BMI088"))
    )
    (comp (ref "U14")
      (value "BMM150")
      (footprint "easyedapro:WLCSP-12_L1.6-W1.6_BMM150")
      (fields (field (name "Manufacturer") "Bosch(博世)"))
      (libsource (lib "easyedapro") (part "BMM150"))
    )
    (comp (ref "U33")
      (value "BMP388")
      (footprint "easyedapro:SENSORM-SMD_BMP388")
      (fields (field (name "Manufacturer") "Bosch(博世)"))
      (libsource (lib "easyedapro") (part "BMP388"))
    )
    (comp (ref "U34")
      (value "ICM-42688-P")
      (footprint "easyedapro:LGA-14_L3.0-W2.5-P0.50-TL")
      (description "Sensor Type:Accelerometer gyroscope")
      (fields (field (name "Manufacturer") "TDK InvenSense(应美盛)"))
      (libsource (lib "easyedapro") (part "ICM-42688-P"))
    )
    (comp (ref "U35")
      (value "24AA64-I/SN")
      (footprint "easyedapro:SOIC-8_L5.0-W4.0-P1.27-LS6.0-BL")
      (libsource (lib "easyedapro") (part "24AA64-I/SN_C615136"))
    )
    (comp (ref "C115")
      (value "100nF")
      (footprint "easyedapro:C0201")
      (libsource (lib "easyedapro") (part "CAP"))
    )
    (comp (ref "C116")
      (value "100nF")
      (footprint "easyedapro:C0201")
      (libsource (lib "easyedapro") (part "CAP"))
    )
    (comp (ref "C117")
      (value "100nF")
      (footprint "easyedapro:C0201")
      (libsource (lib "easyedapro") (part "CAP"))
    )
    (comp (ref "C118")
      (value "100nF")
      (footprint "easyedapro:C0201")
      (libsource (lib "easyedapro") (part "CAP"))
    )
    (comp (ref "C119")
      (value "100nF")
      (footprint "easyedapro:C0201")
      (libsource (lib "easyedapro") (part "CAP"))
    )
    (comp (ref "C120")
      (value "100nF")
      (footprint "easyedapro:C0201")
      (libsource (lib "easyedapro") (part "CAP"))
    )
    (comp (ref "C121")
      (value "0.1uF")
      (footprint "easyedapro:C0201")
      (libsource (lib "easyedapro") (part "CAP"))
    )
    (comp (ref "C122")
      (value "0.1uF")
      (footprint "easyedapro:C0201")
      (libsource (lib "easyedapro") (part "CAP"))
    )
    (comp (ref "C123")
      (value "0.1uF")
      (footprint "easyedapro:C0201")
      (libsource (lib "easyedapro") (part "CAP"))
    )
    (comp (ref "C124")
      (value "10uF")
      (footprint "easyedapro:C0201")
      (libsource (lib "easyedapro") (part "CAP"))
    )
    (comp (ref "C125")
      (value "0.1uF")
      (footprint "easyedapro:C0201")
      (libsource (lib "easyedapro") (part "CAP"))
    )
    (comp (ref "C126")
      (value "0.1uF")
      (footprint "easyedapro:C0201")
      (libsource (lib "easyedapro") (part "CAP"))
    )
    (comp (ref "C127")
      (value "0.1uF")
      (footprint "easyedapro:C0201")
      (libsource (lib "easyedapro") (part "CAP"))
    )
    (comp (ref "C128")
      (value "10uF")
      (footprint "easyedapro:C0201")
      (libsource (lib "easyedapro") (part "CAP"))
    )
    (comp (ref "C129")
      (value "10nF")
      (footprint "easyedapro:C0201")
      (libsource (lib "easyedapro") (part "CAP"))
    )
    (comp (ref "CN15")
      (value "BM04B-GHS-TBT")
      (footprint "easyedapro:CONN-SMD_4P-P1.25_BM04B-GHS-TBT-LF-SN")
      (fields (field (name "Manufacturer") "JST"))
      (libsource (lib "easyedapro") (part "BM04B-GHS-TBT"))
    )
    (comp (ref "D11")
      (value "ESD7104MUTAG-ES")
      (footprint "easyedapro:DFN-10_L2.5-W1.0-P0.50-BL")
      (fields (field (name "Manufacturer") "ElecSuper(静芯)"))
      (libsource (lib "easyedapro") (part "ESD7104MUTAG-ES"))
    )
    (comp (ref "L4")
      (value "DLW43MH201XK2L")
      (footprint "easyedapro:FILTER-SMD_4P-L4.5-W3.2-BL_DLW43MH201XK2L")
      (fields (field (name "Manufacturer") "muRata(村田)"))
      (libsource (lib "easyedapro") (part "DLW43MH201XK2L"))
    )
    (comp (ref "L5")
      (value "DLW43MH201XK2L")
      (footprint "easyedapro:FILTER-SMD_4P-L4.5-W3.2-BL_DLW43MH201XK2L")
      (fields (field (name "Manufacturer") "muRata(村田)"))
      (libsource (lib "easyedapro") (part "DLW43MH201XK2L"))
    )
    (comp (ref "LED6")
      (value "~")
      (footprint "easyedapro:LED0402-RD_YELLOW")
      (libsource (lib "easyedapro") (part "LED_G"))
    )
    (comp (ref "OSC1")
      (value "SG-210STF 50.0000ML")
      (footprint "easyedapro:OSC-SMD_4P-L2.5-W2.0-BL")
      (fields (field (name "Manufacturer") "EPSON(爱普生)"))
      (libsource (lib "easyedapro") (part "SG-210STF 50.0000ML"))
    )
    (comp (ref "R107")
      (value "49.9")
      (footprint "easyedapro:R0603")
      (libsource (lib "easyedapro") (part "Res"))
    )
    (comp (ref "R108")
      (value "49.9")
      (footprint "easyedapro:R0603")
      (libsource (lib "easyedapro") (part "Res"))
    )
    (comp (ref "R109")
      (value "49.9")
      (footprint "easyedapro:R0603")
      (libsource (lib "easyedapro") (part "Res"))
    )
    (comp (ref "R110")
      (value "49.9")
      (footprint "easyedapro:R0603")
      (libsource (lib "easyedapro") (part "Res"))
    )
    (comp (ref "R111")
      (value "22")
      (footprint "easyedapro:R0603")
      (libsource (lib "easyedapro") (part "Res"))
    )
    (comp (ref "R112")
      (value "2.2K")
      (footprint "easyedapro:R0603")
      (libsource (lib "easyedapro") (part "Res"))
    )
    (comp (ref "R113")
      (value "1K")
      (footprint "easyedapro:R0603")
      (libsource (lib "easyedapro") (part "Res"))
    )
    (comp (ref "R114")
      (value "4.87K")
      (footprint "easyedapro:R0603")
      (libsource (lib "easyedapro") (part "Res"))
    )
    (comp (ref "R115")
      (value "22")
      (footprint "easyedapro:R0603")
      (libsource (lib "easyedapro") (part "Res"))
    )
    (comp (ref "R116")
      (value "10K")
      (footprint "easyedapro:R0603")
      (libsource (lib "easyedapro") (part "Res"))
    )
    (comp (ref "R117")
      (value "1.5K")
      (footprint "easyedapro:R0603")
      (libsource (lib "easyedapro") (part "Res"))
    )
    (comp (ref "RJ1")
      (value "6116202-1")
      (footprint "easyedapro:RJ45-TH_6116202-1")
      (fields (field (name "Manufacturer") "TE Connectivity(泰科电子)"))
      (libsource (lib "easyedapro") (part "6116202-1"))
    )
    (comp (ref "U40")
      (value "DP83848TSQ/NOPB")
      (footprint "easyedapro:WQFN-40_L6.0-W6.0-P0.50-BL-EP")
      (fields (field (name "Manufacturer") "TI(德州仪器)"))
      (libsource (lib "easyedapro") (part "DP83848TSQ/NOPB"))
    )
    (comp (ref "C79")
      (value "100nF")
      (footprint "easyedapro:C0201")
      (libsource (lib "easyedapro") (part "CAP"))
    )
    (comp (ref "C137")
      (value "NFM18PC104R1C3D")
      (footprint "easyedapro:FILTER-SMD_3P-L1.6-W0.8-L_NFM18CC223R1C3D")
      (fields (field (name "Manufacturer") "muRata(村田)"))
      (libsource (lib "easyedapro") (part "NFM18PC104R1C3D"))
    )
    (comp (ref "C138")
      (value "NFM18PC104R1C3D")
      (footprint "easyedapro:FILTER-SMD_3P-L1.6-W0.8-L_NFM18CC223R1C3D")
      (fields (field (name "Manufacturer") "muRata(村田)"))
      (libsource (lib "easyedapro") (part "NFM18PC104R1C3D"))
    )
    (comp (ref "C139")
      (value "100nF")
      (footprint "easyedapro:C0201")
      (libsource (lib "easyedapro") (part "CAP"))
    )
    (comp (ref "C140")
      (value "NFM18PC104R1C3D")
      (footprint "easyedapro:FILTER-SMD_3P-L1.6-W0.8-L_NFM18CC223R1C3D")
      (fields (field (name "Manufacturer") "muRata(村田)"))
      (libsource (lib "easyedapro") (part "NFM18PC104R1C3D"))
    )
    (comp (ref "C141")
      (value "100nF")
      (footprint "easyedapro:C0201")
      (libsource (lib "easyedapro") (part "CAP"))
    )
    (comp (ref "C142")
      (value "NFM18PC104R1C3D")
      (footprint "easyedapro:FILTER-SMD_3P-L1.6-W0.8-L_NFM18CC223R1C3D")
      (fields (field (name "Manufacturer") "muRata(村田)"))
      (libsource (lib "easyedapro") (part "NFM18PC104R1C3D"))
    )
    (comp (ref "C143")
      (value "100nF")
      (footprint "easyedapro:C0201")
      (libsource (lib "easyedapro") (part "CAP"))
    )
    (comp (ref "C144")
      (value "NFM18PC104R1C3D")
      (footprint "easyedapro:FILTER-SMD_3P-L1.6-W0.8-L_NFM18CC223R1C3D")
      (fields (field (name "Manufacturer") "muRata(村田)"))
      (libsource (lib "easyedapro") (part "NFM18PC104R1C3D"))
    )
    (comp (ref "C145")
      (value "100nF")
      (footprint "easyedapro:C0201")
      (libsource (lib "easyedapro") (part "CAP"))
    )
    (comp (ref "C146")
      (value "NFM18PC104R1C3D")
      (footprint "easyedapro:FILTER-SMD_3P-L1.6-W0.8-L_NFM18CC223R1C3D")
      (fields (field (name "Manufacturer") "muRata(村田)"))
      (libsource (lib "easyedapro") (part "NFM18PC104R1C3D"))
    )
    (comp (ref "C147")
      (value "100nF")
      (footprint "easyedapro:C0201")
      (libsource (lib "easyedapro") (part "CAP"))
    )
    (comp (ref "C148")
      (value "NFM18PC104R1C3D")
      (footprint "easyedapro:FILTER-SMD_3P-L1.6-W0.8-L_NFM18CC223R1C3D")
      (fields (field (name "Manufacturer") "muRata(村田)"))
      (libsource (lib "easyedapro") (part "NFM18PC104R1C3D"))
    )
    (comp (ref "C149")
      (value "100nF")
      (footprint "easyedapro:C0201")
      (libsource (lib "easyedapro") (part "CAP"))
    )
    (comp (ref "CN2")
      (value "BM06B-GHS-TBT(LF)(SN)")
      (footprint "easyedapro:CONN-SMD_BM06B-GHS-TBT-LF-SN")
      (fields (field (name "Manufacturer") "JST"))
      (libsource (lib "easyedapro") (part "BM06B-GHS-TBT(LF)(SN)"))
    )
    (comp (ref "CN9")
      (value "BM06B-GHS-TBT")
      (footprint "easyedapro:CONN-SMD_6P-P1.25_BM06B-GHS-TBT")
      (fields (field (name "Manufacturer") "JST"))
      (libsource (lib "easyedapro") (part "BM06B-GHS-TBT"))
    )
    (comp (ref "CN16")
      (value "BM10B-GHS-TBT(LF)(SN)")
      (footprint "easyedapro:CONN-SMD_BM10B-GHS-TBT-LF-SN")
      (fields (field (name "Manufacturer") "JST"))
      (libsource (lib "easyedapro") (part "BM10B-GHS-TBT(LF)(SN)"))
    )
    (comp (ref "CN17")
      (value "BM06B-GHS-TBT(LF)(SN)")
      (footprint "easyedapro:CONN-SMD_BM06B-GHS-TBT-LF-SN")
      (fields (field (name "Manufacturer") "JST"))
      (libsource (lib "easyedapro") (part "BM06B-GHS-TBT(LF)(SN)"))
    )
    (comp (ref "CN18")
      (value "BM06B-GHS-TBT(LF)(SN)")
      (footprint "easyedapro:CONN-SMD_BM06B-GHS-TBT-LF-SN")
      (fields (field (name "Manufacturer") "JST"))
      (libsource (lib "easyedapro") (part "BM06B-GHS-TBT(LF)(SN)"))
    )
    (comp (ref "CN19")
      (value "BM07B-GHS-TBT(LF)(SN)(N)")
      (footprint "easyedapro:CONN-SMD_7P-P1.25_BM07B-GHS-TBT-LF-SN-N")
      (fields (field (name "Manufacturer") "JST"))
      (libsource (lib "easyedapro") (part "BM07B-GHS-TBT(LF)(SN)(N)"))
    )
    (comp (ref "D12")
      (value "ESD7104MUTAG-ES")
      (footprint "easyedapro:DFN-10_L2.5-W1.0-P0.50-BL")
      (fields (field (name "Manufacturer") "ElecSuper(静芯)"))
      (libsource (lib "easyedapro") (part "ESD7104MUTAG-ES"))
    )
    (comp (ref "D13")
      (value "TPD1E01B04DPYT")
      (footprint "easyedapro:X1SON-2_L1.0-W0.6-P0.65-BI")
      (fields (field (name "Manufacturer") "TI(德州仪器)"))
      (libsource (lib "easyedapro") (part "TPD1E01B04DPYT"))
    )
    (comp (ref "D18")
      (value "TPD1E01B04DPYT")
      (footprint "easyedapro:X1SON-2_L1.0-W0.6-P0.65-BI")
      (fields (field (name "Manufacturer") "TI(德州仪器)"))
      (libsource (lib "easyedapro") (part "TPD1E01B04DPYT"))
    )
    (comp (ref "D20")
      (value "TPD1E01B04DPYT")
      (footprint "easyedapro:X1SON-2_L1.0-W0.6-P0.65-BI")
      (fields (field (name "Manufacturer") "TI(德州仪器)"))
      (libsource (lib "easyedapro") (part "TPD1E01B04DPYT"))
    )
    (comp (ref "D22")
      (value "ESD7104MUTAG-ES")
      (footprint "easyedapro:DFN-10_L2.5-W1.0-P0.50-BL")
      (fields (field (name "Manufacturer") "ElecSuper(静芯)"))
      (libsource (lib "easyedapro") (part "ESD7104MUTAG-ES"))
    )
    (comp (ref "D23")
      (value "ESD7104MUTAG-ES")
      (footprint "easyedapro:DFN-10_L2.5-W1.0-P0.50-BL")
      (fields (field (name "Manufacturer") "ElecSuper(静芯)"))
      (libsource (lib "easyedapro") (part "ESD7104MUTAG-ES"))
    )
    (comp (ref "D24")
      (value "ESD7104MUTAG-ES")
      (footprint "easyedapro:DFN-10_L2.5-W1.0-P0.50-BL")
      (fields (field (name "Manufacturer") "ElecSuper(静芯)"))
      (libsource (lib "easyedapro") (part "ESD7104MUTAG-ES"))
    )
    (comp (ref "D25")
      (value "TPD1E01B04DPYT")
      (footprint "easyedapro:X1SON-2_L1.0-W0.6-P0.65-BI")
      (fields (field (name "Manufacturer") "TI(德州仪器)"))
      (libsource (lib "easyedapro") (part "TPD1E01B04DPYT"))
    )
    (comp (ref "D26")
      (value "ESD7104MUTAG-ES")
      (footprint "easyedapro:DFN-10_L2.5-W1.0-P0.50-BL")
      (fields (field (name "Manufacturer") "ElecSuper(静芯)"))
      (libsource (lib "easyedapro") (part "ESD7104MUTAG-ES"))
    )
    (comp (ref "D27")
      (value "TPD1E01B04DPYT")
      (footprint "easyedapro:X1SON-2_L1.0-W0.6-P0.65-BI")
      (fields (field (name "Manufacturer") "TI(德州仪器)"))
      (libsource (lib "easyedapro") (part "TPD1E01B04DPYT"))
    )
    (comp (ref "D28")
      (value "ESD7104MUTAG-ES")
      (footprint "easyedapro:DFN-10_L2.5-W1.0-P0.50-BL")
      (fields (field (name "Manufacturer") "ElecSuper(静芯)"))
      (libsource (lib "easyedapro") (part "ESD7104MUTAG-ES"))
    )
    (comp (ref "D31")
      (value "TPD1E01B04DPYT")
      (footprint "easyedapro:X1SON-2_L1.0-W0.6-P0.65-BI")
      (fields (field (name "Manufacturer") "TI(德州仪器)"))
      (libsource (lib "easyedapro") (part "TPD1E01B04DPYT"))
    )
    (comp (ref "D32")
      (value "ESD7104MUTAG-ES")
      (footprint "easyedapro:DFN-10_L2.5-W1.0-P0.50-BL")
      (fields (field (name "Manufacturer") "ElecSuper(静芯)"))
      (libsource (lib "easyedapro") (part "ESD7104MUTAG-ES"))
    )
    (comp (ref "D33")
      (value "TPD1E01B04DPYT")
      (footprint "easyedapro:X1SON-2_L1.0-W0.6-P0.65-BI")
      (fields (field (name "Manufacturer") "TI(德州仪器)"))
      (libsource (lib "easyedapro") (part "TPD1E01B04DPYT"))
    )
    (comp (ref "H6")
      (value "~")
      (footprint "easyedapro:HDR-TH_6P-P2.54-V-F")
      (libsource (lib "easyedapro") (part "Header-Female-2.54_1x6"))
    )
    (comp (ref "H12")
      (value "~")
      (footprint "easyedapro:HDR-TH_6P-P2.54-V-F")
      (libsource (lib "easyedapro") (part "Header-Female-2.54_1x6"))
    )
    (comp (ref "H24")
      (value "~")
      (footprint "easyedapro:HDR-TH_6P-P2.54-V-F")
      (libsource (lib "easyedapro") (part "Header-Female-2.54_1x6"))
    )
    (comp (ref "H25")
      (value "~")
      (footprint "easyedapro:HDR-TH_6P-P2.54-V-F")
      (libsource (lib "easyedapro") (part "Header-Female-2.54_1x6"))
    )
    (comp (ref "H26")
      (value "~")
      (footprint "easyedapro:HDR-TH_10P-P2.54-V-F")
      (libsource (lib "easyedapro") (part "X5511FV-10-C70D30-1000"))
    )
    (comp (ref "H30")
      (value "~")
      (footprint "easyedapro:HDR-TH_7P-P2.54-V-F")
      (libsource (lib "easyedapro") (part "220S-1*7P H=8.5MM Ytype Gold-plated"))
    )
    (comp (ref "Q4")
      (value "~")
      (footprint "easyedapro:SOT-23-3_L2.9-W1.3-P1.90-LS2.4-BR")
      (libsource (lib "easyedapro") (part "N_MOS"))
    )
    (comp (ref "R61")
      (value "220")
      (footprint "easyedapro:R0603")
      (libsource (lib "easyedapro") (part "Res"))
    )
    (comp (ref "R62")
      (value "220")
      (footprint "easyedapro:R0603")
      (libsource (lib "easyedapro") (part "Res"))
    )
    (comp (ref "R63")
      (value "220")
      (footprint "easyedapro:R0603")
      (libsource (lib "easyedapro") (part "Res"))
    )
    (comp (ref "R96")
      (value "220")
      (footprint "easyedapro:R0603")
      (libsource (lib "easyedapro") (part "Res"))
    )
    (comp (ref "R97")
      (value "220")
      (footprint "easyedapro:R0603")
      (libsource (lib "easyedapro") (part "Res"))
    )
    (comp (ref "R98")
      (value "220")
      (footprint "easyedapro:R0603")
      (libsource (lib "easyedapro") (part "Res"))
    )
    (comp (ref "R99")
      (value "220")
      (footprint "easyedapro:R0603")
      (libsource (lib "easyedapro") (part "Res"))
    )
    (comp (ref "R100")
      (value "220")
      (footprint "easyedapro:R0603")
      (libsource (lib "easyedapro") (part "Res"))
    )
    (comp (ref "R120")
      (value "220")
      (footprint "easyedapro:R0603")
      (libsource (lib "easyedapro") (part "Res"))
    )
    (comp (ref "R121")
      (value "220")
      (footprint "easyedapro:R0603")
      (libsource (lib "easyedapro") (part "Res"))
    )
    (comp (ref "R122")
      (value "220")
      (footprint "easyedapro:R0603")
      (libsource (lib "easyedapro") (part "Res"))
    )
    (comp (ref "R123")
      (value "220")
      (footprint "easyedapro:R0603")
      (libsource (lib "easyedapro") (part "Res"))
    )
    (comp (ref "R124")
      (value "220")
      (footprint "easyedapro:R0603")
      (libsource (lib "easyedapro") (part "Res"))
    )
    (comp (ref "R125")
      (value "220")
      (footprint "easyedapro:R0603")
      (libsource (lib "easyedapro") (part "Res"))
    )
    (comp (ref "R126")
      (value "120")
      (footprint "easyedapro:R0603")
      (libsource (lib "easyedapro") (part "Res"))
    )
    (comp (ref "R127")
      (value "120")
      (footprint "easyedapro:R0603")
      (libsource (lib "easyedapro") (part "Res"))
    )
    (comp (ref "R128")
      (value "22")
      (footprint "easyedapro:R0603")
      (libsource (lib "easyedapro") (part "Res"))
    )
    (comp (ref "R129")
      (value "68")
      (footprint "easyedapro:R0603")
      (libsource (lib "easyedapro") (part "Res"))
    )
    (comp (ref "R130")
      (value "10K")
      (footprint "easyedapro:R0603")
      (libsource (lib "easyedapro") (part "Res"))
    )
    (comp (ref "R131")
      (value "220")
      (footprint "easyedapro:R0603")
      (libsource (lib "easyedapro") (part "Res"))
    )
    (comp (ref "R132")
      (value "220")
      (footprint "easyedapro:R0603")
      (libsource (lib "easyedapro") (part "Res"))
    )
    (comp (ref "R133")
      (value "220")
      (footprint "easyedapro:R0603")
      (libsource (lib "easyedapro") (part "Res"))
    )
    (comp (ref "R134")
      (value "220")
      (footprint "easyedapro:R0603")
      (libsource (lib "easyedapro") (part "Res"))
    )
    (comp (ref "R143")
      (value "220")
      (footprint "easyedapro:R0603")
      (libsource (lib "easyedapro") (part "Res"))
    )
    (comp (ref "R144")
      (value "220")
      (footprint "easyedapro:R0603")
      (libsource (lib "easyedapro") (part "Res"))
    )
    (comp (ref "R145")
      (value "120")
      (footprint "easyedapro:R0603")
      (libsource (lib "easyedapro") (part "Res"))
    )
    (comp (ref "R146")
      (value "120")
      (footprint "easyedapro:R0603")
      (libsource (lib "easyedapro") (part "Res"))
    )
    (comp (ref "R147")
      (value "120")
      (footprint "easyedapro:R0603")
      (libsource (lib "easyedapro") (part "Res"))
    )
    (comp (ref "R196")
      (value "22")
      (footprint "easyedapro:R0603")
      (libsource (lib "easyedapro") (part "Res"))
    )
    (comp (ref "R197")
      (value "68")
      (footprint "easyedapro:R0603")
      (libsource (lib "easyedapro") (part "Res"))
    )
    (comp (ref "D29")
      (value "ESD7104MUTAG-ES")
      (footprint "easyedapro:DFN-10_L2.5-W1.0-P0.50-BL")
      (fields (field (name "Manufacturer") "ElecSuper(静芯)"))
      (libsource (lib "easyedapro") (part "ESD7104MUTAG-ES"))
    )
    (comp (ref "D30")
      (value "ESD7104MUTAG-ES")
      (footprint "easyedapro:DFN-10_L2.5-W1.0-P0.50-BL")
      (fields (field (name "Manufacturer") "ElecSuper(静芯)"))
      (libsource (lib "easyedapro") (part "ESD7104MUTAG-ES"))
    )
    (comp (ref "D37")
      (value "ESD7104MUTAG-ES")
      (footprint "easyedapro:DFN-10_L2.5-W1.0-P0.50-BL")
      (fields (field (name "Manufacturer") "ElecSuper(静芯)"))
      (libsource (lib "easyedapro") (part "ESD7104MUTAG-ES"))
    )
    (comp (ref "D38")
      (value "ESD7104MUTAG-ES")
      (footprint "easyedapro:DFN-10_L2.5-W1.0-P0.50-BL")
      (fields (field (name "Manufacturer") "ElecSuper(静芯)"))
      (libsource (lib "easyedapro") (part "ESD7104MUTAG-ES"))
    )
    (comp (ref "H27")
      (value "~")
      (footprint "easyedapro:HDR-TH_8P-P2.54-V-M")
      (libsource (lib "easyedapro") (part "Header-Male-2.54_1x8"))
    )
    (comp (ref "H28")
      (value "~")
      (footprint "easyedapro:HDR-TH_8P-P2.54-V-M")
      (libsource (lib "easyedapro") (part "Header-Male-2.54_1x8"))
    )
    (comp (ref "H29")
      (value "~")
      (footprint "easyedapro:HDR-TH_8P-P2.54-V-M")
      (libsource (lib "easyedapro") (part "Header-Male-2.54_1x8"))
    )
    (comp (ref "H32")
      (value "~")
      (footprint "easyedapro:HDR-TH_8P-P2.54-V-M")
      (libsource (lib "easyedapro") (part "Header-Male-2.54_1x8"))
    )
    (comp (ref "H33")
      (value "~")
      (footprint "easyedapro:HDR-TH_8P-P2.54-V-M")
      (libsource (lib "easyedapro") (part "Header-Male-2.54_1x8"))
    )
    (comp (ref "H34")
      (value "~")
      (footprint "easyedapro:HDR-TH_8P-P2.54-V-M")
      (libsource (lib "easyedapro") (part "Header-Male-2.54_1x8"))
    )
    (comp (ref "R135")
      (value "220")
      (footprint "easyedapro:R0603")
      (libsource (lib "easyedapro") (part "Res"))
    )
    (comp (ref "R136")
      (value "220")
      (footprint "easyedapro:R0603")
      (libsource (lib "easyedapro") (part "Res"))
    )
    (comp (ref "R137")
      (value "220")
      (footprint "easyedapro:R0603")
      (libsource (lib "easyedapro") (part "Res"))
    )
    (comp (ref "R138")
      (value "220")
      (footprint "easyedapro:R0603")
      (libsource (lib "easyedapro") (part "Res"))
    )
    (comp (ref "R139")
      (value "220")
      (footprint "easyedapro:R0603")
      (libsource (lib "easyedapro") (part "Res"))
    )
    (comp (ref "R140")
      (value "220")
      (footprint "easyedapro:R0603")
      (libsource (lib "easyedapro") (part "Res"))
    )
    (comp (ref "R141")
      (value "220")
      (footprint "easyedapro:R0603")
      (libsource (lib "easyedapro") (part "Res"))
    )
    (comp (ref "R142")
      (value "220")
      (footprint "easyedapro:R0603")
      (libsource (lib "easyedapro") (part "Res"))
    )
    (comp (ref "R188")
      (value "220")
      (footprint "easyedapro:R0603")
      (libsource (lib "easyedapro") (part "Res"))
    )
    (comp (ref "R189")
      (value "220")
      (footprint "easyedapro:R0603")
      (libsource (lib "easyedapro") (part "Res"))
    )
    (comp (ref "R190")
      (value "220")
      (footprint "easyedapro:R0603")
      (libsource (lib "easyedapro") (part "Res"))
    )
    (comp (ref "R191")
      (value "220")
      (footprint "easyedapro:R0603")
      (libsource (lib "easyedapro") (part "Res"))
    )
    (comp (ref "R192")
      (value "220")
      (footprint "easyedapro:R0603")
      (libsource (lib "easyedapro") (part "Res"))
    )
    (comp (ref "R193")
      (value "220")
      (footprint "easyedapro:R0603")
      (libsource (lib "easyedapro") (part "Res"))
    )
    (comp (ref "R194")
      (value "220")
      (footprint "easyedapro:R0603")
      (libsource (lib "easyedapro") (part "Res"))
    )
    (comp (ref "R195")
      (value "220")
      (footprint "easyedapro:R0603")
      (libsource (lib "easyedapro") (part "Res"))
    )
    (comp (ref "C204")
      (value "1uF")
      (footprint "easyedapro:C0201")
      (libsource (lib "easyedapro") (part "CAP"))
    )
    (comp (ref "C205")
      (value "100nF")
      (footprint "easyedapro:C0201")
      (libsource (lib "easyedapro") (part "CAP"))
    )
    (comp (ref "C206")
      (value "100nF")
      (footprint "easyedapro:C0201")
      (libsource (lib "easyedapro") (part "CAP"))
    )
    (comp (ref "C207")
      (value "100nF")
      (footprint "easyedapro:C0201")
      (libsource (lib "easyedapro") (part "CAP"))
    )
    (comp (ref "C208")
      (value "1uF")
      (footprint "easyedapro:C0201")
      (libsource (lib "easyedapro") (part "CAP"))
    )
    (comp (ref "C209")
      (value "100nF")
      (footprint "easyedapro:C0201")
      (libsource (lib "easyedapro") (part "CAP"))
    )
    (comp (ref "C210")
      (value "100nF")
      (footprint "easyedapro:C0201")
      (libsource (lib "easyedapro") (part "CAP"))
    )
    (comp (ref "C211")
      (value "8pF")
      (footprint "easyedapro:C0201")
      (libsource (lib "easyedapro") (part "CAP"))
    )
    (comp (ref "CN20")
      (value "SM10B-SRSS-TB")
      (footprint "easyedapro:CONN-SMD_10P-P1.00_SM10B-SRSS-TB")
      (fields (field (name "Manufacturer") "JST"))
      (libsource (lib "easyedapro") (part "SM10B-SRSS-TB"))
    )
    (comp (ref "D35")
      (value "ESD7104MUTAG-ES")
      (footprint "easyedapro:DFN-10_L2.5-W1.0-P0.50-BL")
      (fields (field (name "Manufacturer") "ElecSuper(静芯)"))
      (libsource (lib "easyedapro") (part "ESD7104MUTAG-ES"))
    )
    (comp (ref "D36")
      (value "ESD7104MUTAG-ES")
      (footprint "easyedapro:DFN-10_L2.5-W1.0-P0.50-BL")
      (fields (field (name "Manufacturer") "ElecSuper(静芯)"))
      (libsource (lib "easyedapro") (part "ESD7104MUTAG-ES"))
    )
    (comp (ref "H31")
      (value "~")
      (footprint "easyedapro:HDR-TH_10P-P2.54-V-F")
      (libsource (lib "easyedapro") (part "X5511FV-10-C70D30-1000"))
    )
    (comp (ref "L6")
      (value "FBMH1608HM601-TV")
      (footprint "easyedapro:L0603")
      (fields (field (name "Manufacturer") "TAIYO YUDEN(太诱)"))
      (libsource (lib "easyedapro") (part "FBMH1608HM601-TV"))
    )
    (comp (ref "LED7")
      (value "~")
      (footprint "easyedapro:LED0402-RD_YELLOW")
      (libsource (lib "easyedapro") (part "LED_B"))
    )
    (comp (ref "LED10")
      (value "~")
      (footprint "easyedapro:LED0402-RD_YELLOW")
      (libsource (lib "easyedapro") (part "LED_R"))
    )
    (comp (ref "LED11")
      (value "~")
      (footprint "easyedapro:LED0402-RD_YELLOW")
      (libsource (lib "easyedapro") (part "LED_G"))
    )
    (comp (ref "R178")
      (value "220")
      (footprint "easyedapro:R0603")
      (libsource (lib "easyedapro") (part "Res"))
    )
    (comp (ref "R179")
      (value "220")
      (footprint "easyedapro:R0603")
      (libsource (lib "easyedapro") (part "Res"))
    )
    (comp (ref "R180")
      (value "10K")
      (footprint "easyedapro:R0603")
      (libsource (lib "easyedapro") (part "Res"))
    )
    (comp (ref "R181")
      (value "10K")
      (footprint "easyedapro:R0603")
      (libsource (lib "easyedapro") (part "Res"))
    )
    (comp (ref "R182")
      (value "10K")
      (footprint "easyedapro:R0603")
      (libsource (lib "easyedapro") (part "Res"))
    )
    (comp (ref "R183")
      (value "20K")
      (footprint "easyedapro:R0603")
      (libsource (lib "easyedapro") (part "Res"))
    )
    (comp (ref "R184")
      (value "10K")
      (footprint "easyedapro:R0603")
      (libsource (lib "easyedapro") (part "Res"))
    )
    (comp (ref "R185")
      (value "2.2K")
      (footprint "easyedapro:R0603")
      (libsource (lib "easyedapro") (part "Res"))
    )
    (comp (ref "R186")
      (value "2.2K")
      (footprint "easyedapro:R0603")
      (libsource (lib "easyedapro") (part "Res"))
    )
    (comp (ref "R187")
      (value "2.2K")
      (footprint "easyedapro:R0603")
      (libsource (lib "easyedapro") (part "Res"))
    )
    (comp (ref "U53")
      (value "STM32F103C8T7")
      (footprint "easyedapro:LQFP-48_L7.0-W7.0-P0.50-LS9.0-BL")
      (fields (field (name "Manufacturer") "ST(意法半导体)"))
      (libsource (lib "easyedapro") (part "STM32F103C8T7"))
    )
    (comp (ref "U54")
      (value "24MHz")
      (footprint "easyedapro:CRYSTAL-SMD_4P-L3.2-W2.5-BL")
      (libsource (lib "easyedapro") (part "24MHZ"))
    )
    (comp (ref "C212")
      (value "NFM18PC104R1C3D")
      (footprint "easyedapro:FILTER-SMD_3P-L1.6-W0.8-L_NFM18CC223R1C3D")
      (fields (field (name "Manufacturer") "muRata(村田)"))
      (libsource (lib "easyedapro") (part "NFM18PC104R1C3D"))
    )
    (comp (ref "C213")
      (value "100nF")
      (footprint "easyedapro:C0201")
      (libsource (lib "easyedapro") (part "CAP"))
    )
    (comp (ref "CN21")
      (value "FPC3P1.25")
      (footprint "easyedapro:CONN-SMD_3P-P1.25_1.25T-3PWT")
      (libsource (lib "easyedapro") (part "FPC3P1.25"))
    )
    (comp (ref "D39")
      (value "TPD1E01B04DPYT")
      (footprint "easyedapro:X1SON-2_L1.0-W0.6-P0.65-BI")
      (fields (field (name "Manufacturer") "TI(德州仪器)"))
      (libsource (lib "easyedapro") (part "TPD1E01B04DPYT"))
    )
    (comp (ref "D40")
      (value "TPD1E01B04DPYT")
      (footprint "easyedapro:X1SON-2_L1.0-W0.6-P0.65-BI")
      (fields (field (name "Manufacturer") "TI(德州仪器)"))
      (libsource (lib "easyedapro") (part "TPD1E01B04DPYT"))
    )
    (comp (ref "R198")
      (value "22")
      (footprint "easyedapro:R0603")
      (libsource (lib "easyedapro") (part "Res"))
    )
  )
  (nets
    (net (code "1") (name "16_MHZ_IN") (class "Default")
      (node (ref "C1") (pin "1") (pinfunction "1_1") (pintype "input"))
      (node (ref "U28") (pin "G1") (pinfunction "PH0-OSC_IN_G1") (pintype "unspecified"))
      (node (ref "U3") (pin "1") (pinfunction "HOT_1") (pintype "unspecified"))
    )
    (net (code "2") (name "16_MHZ_OUT") (class "Default")
      (node (ref "C2") (pin "1") (pinfunction "1_1") (pintype "input"))
      (node (ref "U28") (pin "H1") (pinfunction "PH1-OSC_OUT_H1") (pintype "unspecified"))
      (node (ref "U3") (pin "3") (pinfunction "HOT_3") (pintype "unspecified"))
    )
    (net (code "3") (name "24AA64_SCL") (class "Default")
      (node (ref "JP36") (pin "2") (pinfunction "2_2") (pintype "input"))
      (node (ref "U35") (pin "6") (pinfunction "SCL_6") (pintype "unspecified"))
    )
    (net (code "4") (name "24AA64_SDA") (class "Default")
      (node (ref "JP35") (pin "2") (pinfunction "2_2") (pintype "input"))
      (node (ref "U35") (pin "5") (pinfunction "SDA_5") (pintype "unspecified"))
    )
    (net (code "5") (name "32KHZ_IN") (class "Default")
      (node (ref "C3") (pin "1") (pinfunction "1_1") (pintype "input"))
      (node (ref "U28") (pin "E1") (pinfunction "PC14-OSC32_IN_E1") (pintype "unspecified"))
      (node (ref "X1") (pin "1") (pinfunction "1_1") (pintype "unspecified"))
    )
    (net (code "6") (name "32KHZ_OUT") (class "Default")
      (node (ref "C4") (pin "1") (pinfunction "1_1") (pintype "input"))
      (node (ref "U28") (pin "F1") (pinfunction "PC15-OSC32_OUT_F1") (pintype "unspecified"))
      (node (ref "X1") (pin "2") (pinfunction "2_2") (pintype "unspecified"))
    )
    (net (code "7") (name "ADC3_3V3") (class "Default")
      (node (ref "U28") (pin "M5") (pinfunction "PC3_C_M5") (pintype "unspecified"))
    )
    (net (code "8") (name "ADC3_6V6") (class "Default")
      (node (ref "U28") (pin "M4") (pinfunction "PC2_C_M4") (pintype "unspecified"))
    )
    (net (code "9") (name "BMI088_CSB_ACCEL") (class "Default")
      (node (ref "JP19") (pin "2") (pinfunction "2_2") (pintype "input"))
      (node (ref "U12") (pin "14") (pinfunction "CSB1_14") (pintype "unspecified"))
    )
    (net (code "10") (name "BMI088_CSB_GYRO") (class "Default")
      (node (ref "JP20") (pin "2") (pinfunction "2_2") (pintype "input"))
      (node (ref "U12") (pin "5") (pinfunction "CSB2_5") (pintype "unspecified"))
    )
    (net (code "11") (name "BMI088_INT1_ACCEL") (class "Default")
      (node (ref "JP21") (pin "2") (pinfunction "2_2") (pintype "input"))
      (node (ref "U12") (pin "16") (pinfunction "INT1_16") (pintype "unspecified"))
    )
    (net (code "12") (name "BMI088_INT2_ACCEL") (class "Default")
      (node (ref "H4") (pin "1") (pinfunction "1_1") (pintype "unspecified"))
      (node (ref "U12") (pin "1") (pinfunction "INT2_1") (pintype "unspecified"))
    )
    (net (code "13") (name "BMI088_INT3_GYRO") (class "Default")
      (node (ref "JP22") (pin "2") (pinfunction "2_2") (pintype "input"))
      (node (ref "U12") (pin "12") (pinfunction "INT3_12") (pintype "unspecified"))
    )
    (net (code "14") (name "BMI088_INT4_GYRO") (class "Default")
      (node (ref "H5") (pin "1") (pinfunction "1_1") (pintype "unspecified"))
      (node (ref "U12") (pin "13") (pinfunction "INT4_13") (pintype "unspecified"))
    )
    (net (code "15") (name "BMI088_MISO") (class "Default")
      (node (ref "JP17") (pin "2") (pinfunction "2_2") (pintype "input"))
      (node (ref "U12") (pin "10") (pinfunction "SDO2_10") (pintype "unspecified"))
      (node (ref "U12") (pin "15") (pinfunction "SDO1_15") (pintype "unspecified"))
    )
    (net (code "16") (name "BMI088_MOSI") (class "Default")
      (node (ref "JP18") (pin "2") (pinfunction "2_2") (pintype "input"))
      (node (ref "U12") (pin "9") (pinfunction "SDA/SDI_9") (pintype "unspecified"))
    )
    (net (code "17") (name "BMI088_SCK") (class "Default")
      (node (ref "JP16") (pin "2") (pinfunction "2_2") (pintype "input"))
      (node (ref "U12") (pin "8") (pinfunction "SCL/SCK_8") (pintype "unspecified"))
    )
    (net (code "18") (name "BMM150_DRY") (class "Default")
      (node (ref "H22") (pin "1") (pinfunction "1_1") (pintype "unspecified"))
      (node (ref "U14") (pin "D4") (pinfunction "DRY_D4") (pintype "unspecified"))
    )
    (net (code "19") (name "BMM150_INT") (class "Default")
      (node (ref "H23") (pin "1") (pinfunction "1_1") (pintype "unspecified"))
      (node (ref "U14") (pin "D2") (pinfunction "INT_D2") (pintype "unspecified"))
    )
    (net (code "20") (name "BMM150_SCL") (class "Default")
      (node (ref "JP34") (pin "2") (pinfunction "2_2") (pintype "input"))
      (node (ref "U14") (pin "A3") (pinfunction "SCK_A3") (pintype "unspecified"))
    )
    (net (code "21") (name "BMM150_SDA") (class "Default")
      (node (ref "JP33") (pin "2") (pinfunction "2_2") (pintype "input"))
      (node (ref "U14") (pin "B4") (pinfunction "SDI_B4") (pintype "unspecified"))
    )
    (net (code "22") (name "BMP388_INT") (class "Default")
      (node (ref "JP25") (pin "2") (pinfunction "2_2") (pintype "input"))
      (node (ref "U13") (pin "7") (pinfunction "INT_7") (pintype "unspecified"))
    )
    (net (code "23") (name "BMP388_SCL") (class "Default")
      (node (ref "JP24") (pin "2") (pinfunction "2_2") (pintype "input"))
      (node (ref "JP27") (pin "2") (pinfunction "2_2") (pintype "input"))
      (node (ref "U13") (pin "2") (pinfunction "SCK_2") (pintype "unspecified"))
      (node (ref "U33") (pin "2") (pinfunction "SCK_2") (pintype "unspecified"))
    )
    (net (code "24") (name "BMP388_SDA") (class "Default")
      (node (ref "JP23") (pin "2") (pinfunction "2_2") (pintype "input"))
      (node (ref "JP26") (pin "2") (pinfunction "2_2") (pintype "input"))
      (node (ref "U13") (pin "4") (pinfunction "SDI_4") (pintype "unspecified"))
      (node (ref "U33") (pin "4") (pinfunction "SDI_4") (pintype "unspecified"))
    )
    (net (code "25") (name "BOOT0") (class "Default")
      (node (ref "R1") (pin "2") (pinfunction "2_2") (pintype "input"))
      (node (ref "SW1") (pin "3") (pinfunction "3_3") (pintype "input"))
      (node (ref "SW1") (pin "4") (pinfunction "4_4") (pintype "input"))
      (node (ref "U28") (pin "D6") (pinfunction "BOOT0_D6") (pintype "unspecified"))
    )
    (net (code "26") (name "BUCK_PG") (class "Default")
      (node (ref "R76") (pin "1") (pinfunction "1_1") (pintype "input"))
      (node (ref "U26") (pin "1") (pinfunction "PG_1") (pintype "unspecified"))
      (node (ref "U27") (pin "7") (pinfunction "EN_7") (pintype "unspecified"))
    )
    (net (code "27") (name "BUZZER") (class "Default")
      (node (ref "CN16") (pin "9") (pinfunction "9_9") (pintype "unspecified"))
      (node (ref "D23") (pin "5") (pinfunction "I/O_5") (pintype "unspecified"))
      (node (ref "D23") (pin "6") (pinfunction "NC_6") (pintype "unspecified"))
      (node (ref "H26") (pin "9") (pinfunction "9_9") (pintype "unspecified"))
      (node (ref "Q4") (pin "3") (pinfunction "D_3") (pintype "input"))
    )
    (net (code "28") (name "BUZZER_1") (class "Default")
      (node (ref "Q4") (pin "1") (pinfunction "G_1") (pintype "input"))
      (node (ref "R130") (pin "2") (pinfunction "2_2") (pintype "input"))
      (node (ref "U28") (pin "L2") (pinfunction "PF9_L2") (pintype "unspecified"))
    )
    (net (code "29") (name "CAN1_RX") (class "Default")
      (node (ref "U15") (pin "4") (pinfunction "RXD_4") (pintype "output"))
      (node (ref "U28") (pin "B12") (pinfunction "PD0_B12") (pintype "unspecified"))
    )
    (net (code "30") (name "CAN1_TX") (class "Default")
      (node (ref "U15") (pin "1") (pinfunction "TXD_1") (pintype "input"))
      (node (ref "U28") (pin "C12") (pinfunction "PD1_C12") (pintype "unspecified"))
    )
    (net (code "31") (name "CAN2_RX") (class "Default")
      (node (ref "U28") (pin "P12") (pinfunction "PB12_P12") (pintype "unspecified"))
      (node (ref "U32") (pin "4") (pinfunction "RXD_4") (pintype "output"))
    )
    (net (code "32") (name "CAN2_TX") (class "Default")
      (node (ref "U28") (pin "P13") (pinfunction "PB13_P13") (pintype "unspecified"))
      (node (ref "U32") (pin "1") (pinfunction "TXD_1") (pintype "input"))
    )
    (net (code "33") (name "CANH") (class "Default")
      (node (ref "H19") (pin "2") (pinfunction "2_2") (pintype "input"))
      (node (ref "H20") (pin "2") (pinfunction "2_2") (pintype "input"))
    )
    (net (code "34") (name "CANL") (class "Default")
      (node (ref "H19") (pin "3") (pinfunction "3_3") (pintype "input"))
      (node (ref "H20") (pin "3") (pinfunction "3_3") (pintype "input"))
    )
    (net (code "35") (name "ETH_CRS_DV") (class "Default")
      (node (ref "R111") (pin "2") (pinfunction "2_2") (pintype "input"))
      (node (ref "U28") (pin "R3") (pinfunction "PA7_R3") (pintype "unspecified"))
    )
    (net (code "36") (name "ETH_MDC") (class "Default")
      (node (ref "U28") (pin "M3") (pinfunction "PC1_M3") (pintype "unspecified"))
      (node (ref "U40") (pin "25") (pinfunction "MDC_25") (pintype "unspecified"))
    )
    (net (code "37") (name "ETH_MDIO") (class "Default")
      (node (ref "R117") (pin "1") (pinfunction "1_1") (pintype "input"))
      (node (ref "U28") (pin "P2") (pinfunction "PA2_P2") (pintype "unspecified"))
      (node (ref "U40") (pin "24") (pinfunction "MDIO_24") (pintype "unspecified"))
    )
    (net (code "38") (name "ETH_NRESET") (class "Default")
      (node (ref "C162") (pin "1") (pinfunction "1_1") (pintype "input"))
      (node (ref "R116") (pin "1") (pinfunction "1_1") (pintype "input"))
      (node (ref "R151") (pin "2") (pinfunction "2_2") (pintype "input"))
      (node (ref "U40") (pin "23") (pinfunction "RESET_N_23") (pintype "unspecified"))
      (node (ref "U43") (pin "3") (pinfunction "POR2_3") (pintype "unspecified"))
    )
    (net (code "39") (name "ETH_POWER_EN") (class "Default")
      (node (ref "OSC1") (pin "1") (pinfunction "ST#_1") (pintype "unspecified"))
      (node (ref "R152") (pin "2") (pinfunction "2_2") (pintype "input"))
      (node (ref "U28") (pin "B7") (pinfunction "PG15_B7") (pintype "unspecified"))
      (node (ref "U43") (pin "4") (pinfunction "EN2_4") (pintype "unspecified"))
    )
    (net (code "40") (name "ETH_RD_N") (class "Default")
      (node (ref "D11") (pin "1") (pinfunction "I/O_1") (pintype "unspecified"))
      (node (ref "D11") (pin "10") (pinfunction "NC_10") (pintype "unspecified"))
      (node (ref "L4") (pin "1") (pinfunction "1_1") (pintype "input"))
      (node (ref "R107") (pin "1") (pinfunction "1_1") (pintype "input"))
      (node (ref "U40") (pin "11") (pinfunction "RD-_11") (pintype "unspecified"))
    )
    (net (code "41") (name "ETH_RD_P") (class "Default")
      (node (ref "D11") (pin "2") (pinfunction "I/O_2") (pintype "unspecified"))
      (node (ref "D11") (pin "9") (pinfunction "NC_9") (pintype "unspecified"))
      (node (ref "L4") (pin "4") (pinfunction "4_4") (pintype "input"))
      (node (ref "R108") (pin "1") (pinfunction "1_1") (pintype "input"))
      (node (ref "U40") (pin "12") (pinfunction "RD+_12") (pintype "unspecified"))
    )
    (net (code "42") (name "ETH_REF_CLK") (class "Default")
      (node (ref "R115") (pin "2") (pinfunction "2_2") (pintype "input"))
      (node (ref "U28") (pin "N2") (pinfunction "PA1_N2") (pintype "unspecified"))
      (node (ref "U40") (pin "28") (pinfunction "X1_28") (pintype "unspecified"))
    )
    (net (code "43") (name "ETH_RXD0") (class "Default")
      (node (ref "U28") (pin "N5") (pinfunction "PC4_N5") (pintype "unspecified"))
      (node (ref "U40") (pin "36") (pinfunction "RXD_0/PHYAD1_36") (pintype "unspecified"))
    )
    (net (code "44") (name "ETH_RXD1") (class "Default")
      (node (ref "U28") (pin "P5") (pinfunction "PC5_P5") (pintype "unspecified"))
      (node (ref "U40") (pin "37") (pinfunction "RXD_1/PHYAD2_37") (pintype "unspecified"))
    )
    (net (code "45") (name "ETH_TD_N") (class "Default")
      (node (ref "D11") (pin "4") (pinfunction "I/O_4") (pintype "unspecified"))
      (node (ref "D11") (pin "7") (pinfunction "NC_7") (pintype "unspecified"))
      (node (ref "L5") (pin "1") (pinfunction "1_1") (pintype "input"))
      (node (ref "R109") (pin "1") (pinfunction "1_1") (pintype "input"))
      (node (ref "U40") (pin "14") (pinfunction "TD-_14") (pintype "unspecified"))
    )
    (net (code "46") (name "ETH_TD_P") (class "Default")
      (node (ref "D11") (pin "5") (pinfunction "I/O_5") (pintype "unspecified"))
      (node (ref "D11") (pin "6") (pinfunction "NC_6") (pintype "unspecified"))
      (node (ref "L5") (pin "4") (pinfunction "4_4") (pintype "input"))
      (node (ref "R110") (pin "1") (pinfunction "1_1") (pintype "input"))
      (node (ref "U40") (pin "15") (pinfunction "TD+_15") (pintype "unspecified"))
    )
    (net (code "47") (name "ETH_TXD0") (class "Default")
      (node (ref "U28") (pin "A8") (pinfunction "PG13_A8") (pintype "unspecified"))
      (node (ref "U40") (pin "4") (pinfunction "TXD_0_4") (pintype "unspecified"))
    )
    (net (code "48") (name "ETH_TXD1") (class "Default")
      (node (ref "U28") (pin "B8") (pinfunction "PG12_B8") (pintype "unspecified"))
      (node (ref "U40") (pin "5") (pinfunction "TXD_1_5") (pintype "unspecified"))
    )
    (net (code "49") (name "ETH_TX_EN") (class "Default")
      (node (ref "U28") (pin "R13") (pinfunction "PB11_R13") (pintype "unspecified"))
      (node (ref "U40") (pin "3") (pinfunction "TX_EN_3") (pintype "unspecified"))
    )
    (net (code "50") (name "ETH_VDD_5V") (class "Default")
      (node (ref "C158") (pin "3") (pinfunction "OUT_3") (pintype "unspecified"))
      (node (ref "C163") (pin "1") (pinfunction "1_1") (pintype "input"))
      (node (ref "U43") (pin "1") (pinfunction "VIN_1") (pintype "unspecified"))
    )
    (net (code "51") (name "ETH_VDD_IO_3V3") (class "Default")
      (node (ref "C115") (pin "1") (pinfunction "1_1") (pintype "input"))
      (node (ref "C116") (pin "1") (pinfunction "1_1") (pintype "input"))
      (node (ref "C121") (pin "1") (pinfunction "1_1") (pintype "input"))
      (node (ref "C122") (pin "1") (pinfunction "1_1") (pintype "input"))
      (node (ref "C123") (pin "1") (pinfunction "1_1") (pintype "input"))
      (node (ref "C124") (pin "1") (pinfunction "1_1") (pintype "input"))
      (node (ref "C129") (pin "1") (pinfunction "1_1") (pintype "input"))
      (node (ref "C159") (pin "1") (pinfunction "1_1") (pintype "input"))
      (node (ref "C160") (pin "1") (pinfunction "1_1") (pintype "input"))
      (node (ref "LED6") (pin "2") (pinfunction "A_2") (pintype "input"))
      (node (ref "R107") (pin "2") (pinfunction "2_2") (pintype "input"))
      (node (ref "R108") (pin "2") (pinfunction "2_2") (pintype "input"))
      (node (ref "R109") (pin "2") (pinfunction "2_2") (pintype "input"))
      (node (ref "R110") (pin "2") (pinfunction "2_2") (pintype "input"))
      (node (ref "R112") (pin "2") (pinfunction "2_2") (pintype "input"))
      (node (ref "R116") (pin "2") (pinfunction "2_2") (pintype "input"))
      (node (ref "R117") (pin "2") (pinfunction "2_2") (pintype "input"))
      (node (ref "R151") (pin "1") (pinfunction "1_1") (pintype "input"))
      (node (ref "U40") (pin "1") (pinfunction "IOVDD33_1") (pintype "unspecified"))
      (node (ref "U40") (pin "18") (pinfunction "AVDD33_18") (pintype "unspecified"))
      (node (ref "U40") (pin "26") (pinfunction "IOVDD33_26") (pintype "unspecified"))
      (node (ref "U43") (pin "7") (pinfunction "VOUT2_7") (pintype "unspecified"))
    )
    (net (code "52") (name "FMU_CAP1") (class "Default")
      (node (ref "U28") (pin "P10") (pinfunction "PE11_P10") (pintype "unspecified"))
    )
    (net (code "53") (name "FMU_CH1") (class "Default")
      (node (ref "R135") (pin "1") (pinfunction "1_1") (pintype "input"))
      (node (ref "U28") (pin "E14") (pinfunction "PI0_E14") (pintype "unspecified"))
    )
    (net (code "54") (name "FMU_CH2") (class "Default")
      (node (ref "R136") (pin "1") (pinfunction "1_1") (pintype "input"))
      (node (ref "U28") (pin "K12") (pinfunction "PH12_K12") (pintype "unspecified"))
    )
    (net (code "55") (name "FMU_CH3") (class "Default")
      (node (ref "R137") (pin "1") (pinfunction "1_1") (pintype "input"))
      (node (ref "U28") (pin "L12") (pinfunction "PH11_L12") (pintype "unspecified"))
    )
    (net (code "56") (name "FMU_CH4") (class "Default")
      (node (ref "R138") (pin "1") (pinfunction "1_1") (pintype "input"))
      (node (ref "U28") (pin "L13") (pinfunction "PH10_L13") (pintype "unspecified"))
    )
    (net (code "57") (name "FMU_CH5") (class "Default")
      (node (ref "R139") (pin "1") (pinfunction "1_1") (pintype "input"))
      (node (ref "U28") (pin "M15") (pinfunction "PD13_M15") (pintype "unspecified"))
    )
    (net (code "58") (name "FMU_CH6") (class "Default")
      (node (ref "R140") (pin "1") (pinfunction "1_1") (pintype "input"))
      (node (ref "U28") (pin "M14") (pinfunction "PD14_M14") (pintype "unspecified"))
    )
    (net (code "59") (name "FMU_CH7") (class "Default")
      (node (ref "R141") (pin "1") (pinfunction "1_1") (pintype "input"))
      (node (ref "U28") (pin "M11") (pinfunction "PH6_M11") (pintype "unspecified"))
    )
    (net (code "60") (name "FMU_CH8") (class "Default")
      (node (ref "R142") (pin "1") (pinfunction "1_1") (pintype "input"))
      (node (ref "U28") (pin "M13") (pinfunction "PH9_M13") (pintype "unspecified"))
    )
    (net (code "61") (name "FMU_M1") (class "Default")
      (node (ref "D29") (pin "1") (pinfunction "I/O_1") (pintype "unspecified"))
      (node (ref "D29") (pin "10") (pinfunction "NC_10") (pintype "unspecified"))
      (node (ref "H27") (pin "1") (pinfunction "1_1") (pintype "unspecified"))
      (node (ref "R135") (pin "2") (pinfunction "2_2") (pintype "input"))
    )
    (net (code "62") (name "FMU_M2") (class "Default")
      (node (ref "D29") (pin "2") (pinfunction "I/O_2") (pintype "unspecified"))
      (node (ref "D29") (pin "9") (pinfunction "NC_9") (pintype "unspecified"))
      (node (ref "H27") (pin "2") (pinfunction "2_2") (pintype "unspecified"))
      (node (ref "R136") (pin "2") (pinfunction "2_2") (pintype "input"))
    )
    (net (code "63") (name "FMU_M3") (class "Default")
      (node (ref "D29") (pin "4") (pinfunction "I/O_4") (pintype "unspecified"))
      (node (ref "D29") (pin "7") (pinfunction "NC_7") (pintype "unspecified"))
      (node (ref "H27") (pin "3") (pinfunction "3_3") (pintype "unspecified"))
      (node (ref "R137") (pin "2") (pinfunction "2_2") (pintype "input"))
    )
    (net (code "64") (name "FMU_M4") (class "Default")
      (node (ref "D29") (pin "5") (pinfunction "I/O_5") (pintype "unspecified"))
      (node (ref "D29") (pin "6") (pinfunction "NC_6") (pintype "unspecified"))
      (node (ref "H27") (pin "4") (pinfunction "4_4") (pintype "unspecified"))
      (node (ref "R138") (pin "2") (pinfunction "2_2") (pintype "input"))
    )
    (net (code "65") (name "FMU_M5") (class "Default")
      (node (ref "D30") (pin "1") (pinfunction "I/O_1") (pintype "unspecified"))
      (node (ref "D30") (pin "10") (pinfunction "NC_10") (pintype "unspecified"))
      (node (ref "H27") (pin "5") (pinfunction "5_5") (pintype "unspecified"))
      (node (ref "R139") (pin "2") (pinfunction "2_2") (pintype "input"))
    )
    (net (code "66") (name "FMU_M6") (class "Default")
      (node (ref "D30") (pin "2") (pinfunction "I/O_2") (pintype "unspecified"))
      (node (ref "D30") (pin "9") (pinfunction "NC_9") (pintype "unspecified"))
      (node (ref "H27") (pin "6") (pinfunction "6_6") (pintype "unspecified"))
      (node (ref "R140") (pin "2") (pinfunction "2_2") (pintype "input"))
    )
    (net (code "67") (name "FMU_M7") (class "Default")
      (node (ref "D30") (pin "4") (pinfunction "I/O_4") (pintype "unspecified"))
      (node (ref "D30") (pin "7") (pinfunction "NC_7") (pintype "unspecified"))
      (node (ref "H27") (pin "7") (pinfunction "7_7") (pintype "unspecified"))
      (node (ref "R141") (pin "2") (pinfunction "2_2") (pintype "input"))
    )
    (net (code "68") (name "FMU_M8") (class "Default")
      (node (ref "D30") (pin "5") (pinfunction "I/O_5") (pintype "unspecified"))
      (node (ref "D30") (pin "6") (pinfunction "NC_6") (pintype "unspecified"))
      (node (ref "H27") (pin "8") (pinfunction "8_8") (pintype "unspecified"))
      (node (ref "R142") (pin "2") (pinfunction "2_2") (pintype "input"))
    )
    (net (code "69") (name "FMU_NRST") (class "Default")
      (node (ref "C5") (pin "1") (pinfunction "1_1") (pintype "input"))
      (node (ref "D1") (pin "1") (pinfunction "K_1") (pintype "unspecified"))
      (node (ref "SW2") (pin "1") (pinfunction "1_1") (pintype "input"))
      (node (ref "SW2") (pin "2") (pinfunction "2_2") (pintype "input"))
      (node (ref "U28") (pin "J1") (pinfunction "NRST_J1") (pintype "unspecified"))
    )
    (net (code "70") (name "FMU_NSAFETY_SWITCH_LED_OUT") (class "Default")
      (node (ref "R129") (pin "1") (pinfunction "1_1") (pintype "input"))
      (node (ref "U28") (pin "N15") (pinfunction "PD10_N15") (pintype "unspecified"))
    )
    (net (code "71") (name "FMU_PPM_INPUT") (class "Default")
      (node (ref "U28") (pin "C4") (pinfunction "PI5_C4") (pintype "unspecified"))
    )
    (net (code "72") (name "FMU_SAFETY_SWITCH_IN") (class "Default")
      (node (ref "R128") (pin "1") (pinfunction "1_1") (pintype "input"))
      (node (ref "U28") (pin "K3") (pinfunction "PF5_K3") (pintype "unspecified"))
    )
    (net (code "73") (name "FMU_SWCLK") (class "Default")
      (node (ref "D2") (pin "5") (pinfunction "I/O_5") (pintype "unspecified"))
      (node (ref "D2") (pin "6") (pinfunction "NC_6") (pintype "unspecified"))
      (node (ref "H1") (pin "5") (pinfunction "5_5") (pintype "input"))
      (node (ref "U28") (pin "A14") (pinfunction "PA14_A14") (pintype "unspecified"))
      (node (ref "U30") (pin "5") (pinfunction "5_5") (pintype "unspecified"))
    )
    (net (code "74") (name "FMU_SWDIO") (class "Default")
      (node (ref "D2") (pin "4") (pinfunction "I/O_4") (pintype "unspecified"))
      (node (ref "D2") (pin "7") (pinfunction "NC_7") (pintype "unspecified"))
      (node (ref "H1") (pin "4") (pinfunction "4_4") (pintype "input"))
      (node (ref "U28") (pin "A15") (pinfunction "PA13_A15") (pintype "unspecified"))
      (node (ref "U30") (pin "4") (pinfunction "4_4") (pintype "unspecified"))
    )
    (net (code "75") (name "FMU_VDD_3V3") (class "Default")
      (node (ref "C12") (pin "1") (pinfunction "1_1") (pintype "input"))
      (node (ref "C13") (pin "1") (pinfunction "1_1") (pintype "input"))
      (node (ref "C14") (pin "1") (pinfunction "1_1") (pintype "input"))
      (node (ref "C144") (pin "1") (pinfunction "IN_1") (pintype "unspecified"))
      (node (ref "C145") (pin "1") (pinfunction "1_1") (pintype "input"))
      (node (ref "C15") (pin "1") (pinfunction "1_1") (pintype "input"))
      (node (ref "C16") (pin "1") (pinfunction "1_1") (pintype "input"))
      (node (ref "C17") (pin "1") (pinfunction "1_1") (pintype "input"))
      (node (ref "C18") (pin "1") (pinfunction "1_1") (pintype "input"))
      (node (ref "C19") (pin "1") (pinfunction "1_1") (pintype "input"))
      (node (ref "C20") (pin "1") (pinfunction "1_1") (pintype "input"))
      (node (ref "C21") (pin "1") (pinfunction "1_1") (pintype "input"))
      (node (ref "C22") (pin "1") (pinfunction "1_1") (pintype "input"))
      (node (ref "C39") (pin "2") (pinfunction "2_2") (pintype "input"))
      (node (ref "C40") (pin "1") (pinfunction "1_1") (pintype "input"))
      (node (ref "C41") (pin "2") (pinfunction "2_2") (pintype "input"))
      (node (ref "C91") (pin "1") (pinfunction "1_1") (pintype "input"))
      (node (ref "C95") (pin "2") (pinfunction "2_2") (pintype "input"))
      (node (ref "C96") (pin "1") (pinfunction "1_1") (pintype "input"))
      (node (ref "D34") (pin "2") (pinfunction "A_2") (pintype "input"))
      (node (ref "H1") (pin "1") (pinfunction "1_1") (pintype "input"))
      (node (ref "L3") (pin "1") (pinfunction "1_1") (pintype "unspecified"))
      (node (ref "R14") (pin "2") (pinfunction "2_2") (pintype "input"))
      (node (ref "R15") (pin "2") (pinfunction "2_2") (pintype "input"))
      (node (ref "R16") (pin "2") (pinfunction "2_2") (pintype "input"))
      (node (ref "R17") (pin "2") (pinfunction "2_2") (pintype "input"))
      (node (ref "R18") (pin "2") (pinfunction "2_2") (pintype "input"))
      (node (ref "R52") (pin "2") (pinfunction "2_2") (pintype "input"))
      (node (ref "R57") (pin "2") (pinfunction "2_2") (pintype "input"))
      (node (ref "R6") (pin "2") (pinfunction "2_2") (pintype "input"))
      (node (ref "R7") (pin "2") (pinfunction "2_2") (pintype "input"))
      (node (ref "R77") (pin "2") (pinfunction "2_2") (pintype "input"))
      (node (ref "R80") (pin "2") (pinfunction "2_2") (pintype "input"))
      (node (ref "R81") (pin "2") (pinfunction "2_2") (pintype "input"))
      (node (ref "R84") (pin "2") (pinfunction "2_2") (pintype "input"))
      (node (ref "R85") (pin "2") (pinfunction "2_2") (pintype "input"))
      (node (ref "R86") (pin "2") (pinfunction "2_2") (pintype "input"))
      (node (ref "R90") (pin "2") (pinfunction "2_2") (pintype "input"))
      (node (ref "R91") (pin "2") (pinfunction "2_2") (pintype "input"))
      (node (ref "R92") (pin "2") (pinfunction "2_2") (pintype "input"))
      (node (ref "R93") (pin "2") (pinfunction "2_2") (pintype "input"))
      (node (ref "R94") (pin "2") (pinfunction "2_2") (pintype "input"))
      (node (ref "R95") (pin "2") (pinfunction "2_2") (pintype "input"))
      (node (ref "SW1") (pin "1") (pinfunction "1_1") (pintype "input"))
      (node (ref "SW1") (pin "2") (pinfunction "2_2") (pintype "input"))
      (node (ref "U15") (pin "3") (pinfunction "VCC_3") (pintype "bidirectional"))
      (node (ref "U15") (pin "5") (pinfunction "VIO_5") (pintype "bidirectional"))
      (node (ref "U16") (pin "A1") (pinfunction "IN_A1") (pintype "unspecified"))
      (node (ref "U27") (pin "1") (pinfunction "OUT_1") (pintype "unspecified"))
      (node (ref "U27") (pin "2") (pinfunction "OUT_2") (pintype "unspecified"))
      (node (ref "U28") (pin "C5") (pinfunction "VDD_C5") (pintype "unspecified"))
      (node (ref "U28") (pin "C6") (pinfunction "PDR_ON_C6") (pintype "unspecified"))
      (node (ref "U28") (pin "C7") (pinfunction "VDD_C7") (pintype "unspecified"))
      (node (ref "U28") (pin "C8") (pinfunction "VDD_C8") (pintype "unspecified"))
      (node (ref "U28") (pin "C9") (pinfunction "VDD_C9") (pintype "unspecified"))
      (node (ref "U28") (pin "F3") (pinfunction "VDD_F3") (pintype "unspecified"))
      (node (ref "U28") (pin "G13") (pinfunction "VDD_G13") (pintype "unspecified"))
      (node (ref "U28") (pin "G3") (pinfunction "VDD_G3") (pintype "unspecified"))
      (node (ref "U28") (pin "J12") (pinfunction "VDD_J12") (pintype "unspecified"))
      (node (ref "U28") (pin "J13") (pinfunction "VDD_J13") (pintype "unspecified"))
      (node (ref "U28") (pin "K4") (pinfunction "VDD_K4") (pintype "unspecified"))
      (node (ref "U28") (pin "N10") (pinfunction "VDD_N10") (pintype "unspecified"))
      (node (ref "U28") (pin "N8") (pinfunction "VDD_N8") (pintype "unspecified"))
      (node (ref "U28") (pin "N9") (pinfunction "VDD_N9") (pintype "unspecified"))
      (node (ref "U30") (pin "1") (pinfunction "1_1") (pintype "unspecified"))
      (node (ref "U32") (pin "3") (pinfunction "VCC_3") (pintype "bidirectional"))
      (node (ref "U32") (pin "5") (pinfunction "VIO_5") (pintype "bidirectional"))
      (node (ref "U5") (pin "8") (pinfunction "VDD_8") (pintype "unspecified"))
    )
    (net (code "76") (name "FRAM_CSN") (class "Default")
      (node (ref "JP4") (pin "2") (pinfunction "2_2") (pintype "input"))
      (node (ref "U5") (pin "1") (pinfunction "CS#_1") (pintype "unspecified"))
    )
    (net (code "77") (name "FRAM_MISO") (class "Default")
      (node (ref "JP3") (pin "2") (pinfunction "2_2") (pintype "input"))
      (node (ref "U5") (pin "2") (pinfunction "SO_2") (pintype "unspecified"))
    )
    (net (code "78") (name "FRAM_MOSI") (class "Default")
      (node (ref "JP2") (pin "2") (pinfunction "2_2") (pintype "input"))
      (node (ref "U5") (pin "5") (pinfunction "SI_5") (pintype "unspecified"))
    )
    (net (code "79") (name "FRAM_SCK") (class "Default")
      (node (ref "JP1") (pin "2") (pinfunction "2_2") (pintype "input"))
      (node (ref "U5") (pin "6") (pinfunction "SCK_6") (pintype "unspecified"))
    )
    (net (code "80") (name "GND") (class "Default")
      (node (ref "C1") (pin "2") (pinfunction "2_2") (pintype "input"))
      (node (ref "C100") (pin "2") (pinfunction "2_2") (pintype "input"))
      (node (ref "C101") (pin "2") (pinfunction "2_2") (pintype "input"))
      (node (ref "C102") (pin "2") (pinfunction "2_2") (pintype "input"))
      (node (ref "C103") (pin "1") (pinfunction "1_1") (pintype "input"))
      (node (ref "C104") (pin "1") (pinfunction "1_1") (pintype "input"))
      (node (ref "C115") (pin "2") (pinfunction "2_2") (pintype "input"))
      (node (ref "C116") (pin "2") (pinfunction "2_2") (pintype "input"))
      (node (ref "C12") (pin "2") (pinfunction "2_2") (pintype "input"))
      (node (ref "C121") (pin "2") (pinfunction "2_2") (pintype "input"))
      (node (ref "C122") (pin "2") (pinfunction "2_2") (pintype "input"))
      (node (ref "C123") (pin "2") (pinfunction "2_2") (pintype "input"))
      (node (ref "C124") (pin "2") (pinfunction "2_2") (pintype "input"))
      (node (ref "C125") (pin "2") (pinfunction "2_2") (pintype "input"))
      (node (ref "C126") (pin "2") (pinfunction "2_2") (pintype "input"))
      (node (ref "C127") (pin "2") (pinfunction "2_2") (pintype "input"))
      (node (ref "C128") (pin "2") (pinfunction "2_2") (pintype "input"))
      (node (ref "C129") (pin "2") (pinfunction "2_2") (pintype "input"))
      (node (ref "C13") (pin "2") (pinfunction "2_2") (pintype "input"))
      (node (ref "C137") (pin "2") (pinfunction "GND_2") (pintype "unspecified"))
      (node (ref "C138") (pin "2") (pinfunction "GND_2") (pintype "unspecified"))
      (node (ref "C139") (pin "2") (pinfunction "2_2") (pintype "input"))
      (node (ref "C14") (pin "2") (pinfunction "2_2") (pintype "input"))
      (node (ref "C140") (pin "2") (pinfunction "GND_2") (pintype "unspecified"))
      (node (ref "C141") (pin "2") (pinfunction "2_2") (pintype "input"))
      (node (ref "C142") (pin "2") (pinfunction "GND_2") (pintype "unspecified"))
      (node (ref "C143") (pin "2") (pinfunction "2_2") (pintype "input"))
      (node (ref "C144") (pin "2") (pinfunction "GND_2") (pintype "unspecified"))
      (node (ref "C145") (pin "2") (pinfunction "2_2") (pintype "input"))
      (node (ref "C146") (pin "2") (pinfunction "GND_2") (pintype "unspecified"))
      (node (ref "C147") (pin "2") (pinfunction "2_2") (pintype "input"))
      (node (ref "C148") (pin "2") (pinfunction "GND_2") (pintype "unspecified"))
      (node (ref "C149") (pin "2") (pinfunction "2_2") (pintype "input"))
      (node (ref "C15") (pin "2") (pinfunction "2_2") (pintype "input"))
      (node (ref "C150") (pin "2") (pinfunction "2_2") (pintype "input"))
      (node (ref "C151") (pin "2") (pinfunction "2_2") (pintype "input"))
      (node (ref "C152") (pin "2") (pinfunction "2_2") (pintype "input"))
      (node (ref "C153") (pin "2") (pinfunction "2_2") (pintype "input"))
      (node (ref "C154") (pin "2") (pinfunction "2_2") (pintype "input"))
      (node (ref "C156") (pin "2") (pinfunction "2_2") (pintype "input"))
      (node (ref "C157") (pin "2") (pinfunction "2_2") (pintype "input"))
      (node (ref "C158") (pin "2") (pinfunction "GND_2") (pintype "unspecified"))
      (node (ref "C159") (pin "2") (pinfunction "2_2") (pintype "input"))
      (node (ref "C16") (pin "2") (pinfunction "2_2") (pintype "input"))
      (node (ref "C160") (pin "2") (pinfunction "2_2") (pintype "input"))
      (node (ref "C161") (pin "2") (pinfunction "2_2") (pintype "input"))
      (node (ref "C162") (pin "2") (pinfunction "2_2") (pintype "input"))
      (node (ref "C163") (pin "2") (pinfunction "2_2") (pintype "input"))
      (node (ref "C17") (pin "2") (pinfunction "2_2") (pintype "input"))
      (node (ref "C18") (pin "2") (pinfunction "2_2") (pintype "input"))
      (node (ref "C180") (pin "2") (pinfunction "GND_2") (pintype "unspecified"))
      (node (ref "C181") (pin "2") (pinfunction "2_2") (pintype "input"))
      (node (ref "C182") (pin "2") (pinfunction "2_2") (pintype "input"))
      (node (ref "C183") (pin "2") (pinfunction "2_2") (pintype "input"))
      (node (ref "C184") (pin "2") (pinfunction "2_2") (pintype "input"))
      (node (ref "C185") (pin "2") (pinfunction "2_2") (pintype "input"))
      (node (ref "C186") (pin "2") (pinfunction "GND_2") (pintype "unspecified"))
      (node (ref "C187") (pin "2") (pinfunction "2_2") (pintype "input"))
      (node (ref "C188") (pin "2") (pinfunction "2_2") (pintype "input"))
      (node (ref "C189") (pin "2") (pinfunction "2_2") (pintype "input"))
      (node (ref "C19") (pin "2") (pinfunction "2_2") (pintype "input"))
      (node (ref "C190") (pin "2") (pinfunction "2_2") (pintype "input"))
      (node (ref "C191") (pin "2") (pinfunction "2_2") (pintype "input"))
      (node (ref "C192") (pin "2") (pinfunction "GND_2") (pintype "unspecified"))
      (node (ref "C193") (pin "2") (pinfunction "2_2") (pintype "input"))
      (node (ref "C194") (pin "2") (pinfunction "2_2") (pintype "input"))
      (node (ref "C195") (pin "2") (pinfunction "2_2") (pintype "input"))
      (node (ref "C196") (pin "2") (pinfunction "2_2") (pintype "input"))
      (node (ref "C197") (pin "2") (pinfunction "2_2") (pintype "input"))
      (node (ref "C198") (pin "2") (pinfunction "GND_2") (pintype "unspecified"))
      (node (ref "C199") (pin "2") (pinfunction "2_2") (pintype "input"))
      (node (ref "C2") (pin "2") (pinfunction "2_2") (pintype "input"))
      (node (ref "C20") (pin "2") (pinfunction "2_2") (pintype "input"))
      (node (ref "C200") (pin "2") (pinfunction "2_2") (pintype "input"))
      (node (ref "C201") (pin "2") (pinfunction "2_2") (pintype "input"))
      (node (ref "C202") (pin "2") (pinfunction "2_2") (pintype "input"))
      (node (ref "C203") (pin "2") (pinfunction "2_2") (pintype "input"))
      (node (ref "C204") (pin "2") (pinfunction "2_2") (pintype "input"))
      (node (ref "C205") (pin "2") (pinfunction "2_2") (pintype "input"))
      (node (ref "C206") (pin "2") (pinfunction "2_2") (pintype "input"))
      (node (ref "C207") (pin "2") (pinfunction "2_2") (pintype "input"))
      (node (ref "C208") (pin "2") (pinfunction "2_2") (pintype "input"))
      (node (ref "C209") (pin "2") (pinfunction "2_2") (pintype "input"))
      (node (ref "C21") (pin "2") (pinfunction "2_2") (pintype "input"))
      (node (ref "C210") (pin "2") (pinfunction "2_2") (pintype "input"))
      (node (ref "C211") (pin "2") (pinfunction "2_2") (pintype "input"))
      (node (ref "C212") (pin "2") (pinfunction "GND_2") (pintype "unspecified"))
      (node (ref "C213") (pin "2") (pinfunction "2_2") (pintype "input"))
      (node (ref "C22") (pin "2") (pinfunction "2_2") (pintype "input"))
      (node (ref "C23") (pin "2") (pinfunction "2_2") (pintype "input"))
      (node (ref "C24") (pin "2") (pinfunction "2_2") (pintype "input"))
      (node (ref "C25") (pin "2") (pinfunction "2_2") (pintype "input"))
      (node (ref "C3") (pin "2") (pinfunction "2_2") (pintype "input"))
      (node (ref "C33") (pin "2") (pinfunction "2_2") (pintype "input"))
      (node (ref "C34") (pin "2") (pinfunction "2_2") (pintype "input"))
      (node (ref "C35") (pin "1") (pinfunction "1_1") (pintype "input"))
      (node (ref "C36") (pin "2") (pinfunction "2_2") (pintype "input"))
      (node (ref "C37") (pin "2") (pinfunction "2_2") (pintype "input"))
      (node (ref "C38") (pin "2") (pinfunction "2_2") (pintype "input"))
      (node (ref "C39") (pin "1") (pinfunction "1_1") (pintype "input"))
      (node (ref "C4") (pin "2") (pinfunction "2_2") (pintype "input"))
      (node (ref "C40") (pin "2") (pinfunction "2_2") (pintype "input"))
      (node (ref "C41") (pin "1") (pinfunction "1_1") (pintype "input"))
      (node (ref "C42") (pin "1") (pinfunction "1_1") (pintype "input"))
      (node (ref "C43") (pin "2") (pinfunction "2_2") (pintype "input"))
      (node (ref "C44") (pin "2") (pinfunction "2_2") (pintype "input"))
      (node (ref "C45") (pin "2") (pinfunction "2_2") (pintype "input"))
      (node (ref "C46") (pin "2") (pinfunction "2_2") (pintype "input"))
      (node (ref "C47") (pin "2") (pinfunction "2_2") (pintype "input"))
      (node (ref "C48") (pin "2") (pinfunction "2_2") (pintype "input"))
      (node (ref "C49") (pin "2") (pinfunction "2_2") (pintype "input"))
      (node (ref "C5") (pin "2") (pinfunction "2_2") (pintype "input"))
      (node (ref "C50") (pin "2") (pinfunction "2_2") (pintype "input"))
      (node (ref "C51") (pin "2") (pinfunction "2_2") (pintype "input"))
      (node (ref "C52") (pin "2") (pinfunction "2_2") (pintype "input"))
      (node (ref "C53") (pin "2") (pinfunction "2_2") (pintype "input"))
      (node (ref "C54") (pin "2") (pinfunction "2_2") (pintype "input"))
      (node (ref "C55") (pin "2") (pinfunction "2_2") (pintype "input"))
      (node (ref "C58") (pin "2") (pinfunction "2_2") (pintype "input"))
      (node (ref "C59") (pin "1") (pinfunction "1_1") (pintype "input"))
      (node (ref "C60") (pin "2") (pinfunction "2_2") (pintype "input"))
      (node (ref "C61") (pin "2") (pinfunction "2_2") (pintype "input"))
      (node (ref "C66") (pin "1") (pinfunction "1_1") (pintype "input"))
      (node (ref "C67") (pin "2") (pinfunction "2_2") (pintype "input"))
      (node (ref "C68") (pin "2") (pinfunction "2_2") (pintype "input"))
      (node (ref "C78") (pin "2") (pinfunction "GND_2") (pintype "unspecified"))
      (node (ref "C79") (pin "2") (pinfunction "2_2") (pintype "input"))
      (node (ref "C86") (pin "2") (pinfunction "2_2") (pintype "input"))
      (node (ref "C87") (pin "2") (pinfunction "2_2") (pintype "input"))
      (node (ref "C88") (pin "2") (pinfunction "2_2") (pintype "input"))
      (node (ref "C89") (pin "2") (pinfunction "2_2") (pintype "input"))
      (node (ref "C90") (pin "2") (pinfunction "2_2") (pintype "input"))
      (node (ref "C91") (pin "2") (pinfunction "2_2") (pintype "input"))
      (node (ref "C92") (pin "1") (pinfunction "1_1") (pintype "input"))
      (node (ref "C93") (pin "1") (pinfunction "1_1") (pintype "input"))
      (node (ref "C94") (pin "2") (pinfunction "2_2") (pintype "input"))
      (node (ref "C95") (pin "1") (pinfunction "1_1") (pintype "input"))
      (node (ref "C96") (pin "2") (pinfunction "2_2") (pintype "input"))
      (node (ref "C97") (pin "1") (pinfunction "1_1") (pintype "input"))
      (node (ref "C98") (pin "2") (pinfunction "2_2") (pintype "input"))
      (node (ref "C99") (pin "2") (pinfunction "2_2") (pintype "input"))
      (node (ref "CN11") (pin "4") (pinfunction "4_4") (pintype "unspecified"))
      (node (ref "CN11") (pin "5") (pinfunction "5_5") (pintype "unspecified"))
      (node (ref "CN11") (pin "6") (pinfunction "6_6") (pintype "unspecified"))
      (node (ref "CN13") (pin "4") (pinfunction "4_4") (pintype "unspecified"))
      (node (ref "CN13") (pin "5") (pinfunction "5_5") (pintype "unspecified"))
      (node (ref "CN13") (pin "6") (pinfunction "6_6") (pintype "unspecified"))
      (node (ref "CN14") (pin "4") (pinfunction "4_4") (pintype "unspecified"))
      (node (ref "CN14") (pin "5") (pinfunction "5_5") (pintype "unspecified"))
      (node (ref "CN14") (pin "6") (pinfunction "6_6") (pintype "unspecified"))
      (node (ref "CN15") (pin "5") (pinfunction "5_5") (pintype "unspecified"))
      (node (ref "CN15") (pin "6") (pinfunction "6_6") (pintype "unspecified"))
      (node (ref "CN16") (pin "10") (pinfunction "10_10") (pintype "unspecified"))
      (node (ref "CN16") (pin "11") (pinfunction "11_11") (pintype "unspecified"))
      (node (ref "CN16") (pin "12") (pinfunction "12_12") (pintype "unspecified"))
      (node (ref "CN17") (pin "6") (pinfunction "6_6") (pintype "input"))
      (node (ref "CN17") (pin "7") (pinfunction "7_7") (pintype "input"))
      (node (ref "CN17") (pin "8") (pinfunction "8_8") (pintype "input"))
      (node (ref "CN18") (pin "6") (pinfunction "6_6") (pintype "input"))
      (node (ref "CN18") (pin "7") (pinfunction "7_7") (pintype "input"))
      (node (ref "CN18") (pin "8") (pinfunction "8_8") (pintype "input"))
      (node (ref "CN19") (pin "7") (pinfunction "7_7") (pintype "unspecified"))
      (node (ref "CN19") (pin "8") (pinfunction "8_8") (pintype "unspecified"))
      (node (ref "CN19") (pin "9") (pinfunction "9_9") (pintype "unspecified"))
      (node (ref "CN2") (pin "6") (pinfunction "6_6") (pintype "input"))
      (node (ref "CN2") (pin "7") (pinfunction "7_7") (pintype "input"))
      (node (ref "CN2") (pin "8") (pinfunction "8_8") (pintype "input"))
      (node (ref "CN20") (pin "10") (pinfunction "10_10") (pintype "unspecified"))
      (node (ref "CN20") (pin "11") (pinfunction "11_11") (pintype "unspecified"))
      (node (ref "CN20") (pin "12") (pinfunction "12_12") (pintype "unspecified"))
      (node (ref "CN21") (pin "2") (pinfunction "2_2") (pintype "unspecified"))
      (node (ref "CN21") (pin "4") (pinfunction "4_4") (pintype "unspecified"))
      (node (ref "CN21") (pin "5") (pinfunction "5_5") (pintype "unspecified"))
      (node (ref "CN9") (pin "6") (pinfunction "6_6") (pintype "unspecified"))
      (node (ref "CN9") (pin "7") (pinfunction "7_7") (pintype "unspecified"))
      (node (ref "CN9") (pin "8") (pinfunction "8_8") (pintype "unspecified"))
      (node (ref "D1") (pin "2") (pinfunction "A_2") (pintype "unspecified"))
      (node (ref "D10") (pin "2") (pinfunction "2_2") (pintype "input"))
      (node (ref "D11") (pin "3") (pinfunction "GND_3") (pintype "unspecified"))
      (node (ref "D11") (pin "8") (pinfunction "GND_8") (pintype "unspecified"))
      (node (ref "D12") (pin "3") (pinfunction "GND_3") (pintype "unspecified"))
      (node (ref "D12") (pin "8") (pinfunction "GND_8") (pintype "unspecified"))
      (node (ref "D13") (pin "1") (pinfunction "1_1") (pintype "input"))
      (node (ref "D18") (pin "1") (pinfunction "1_1") (pintype "input"))
      (node (ref "D2") (pin "3") (pinfunction "GND_3") (pintype "unspecified"))
      (node (ref "D2") (pin "8") (pinfunction "GND_8") (pintype "unspecified"))
      (node (ref "D20") (pin "1") (pinfunction "1_1") (pintype "input"))
      (node (ref "D22") (pin "3") (pinfunction "GND_3") (pintype "unspecified"))
      (node (ref "D22") (pin "8") (pinfunction "GND_8") (pintype "unspecified"))
      (node (ref "D23") (pin "3") (pinfunction "GND_3") (pintype "unspecified"))
      (node (ref "D23") (pin "4") (pinfunction "I/O_4") (pintype "unspecified"))
      (node (ref "D23") (pin "7") (pinfunction "NC_7") (pintype "unspecified"))
      (node (ref "D23") (pin "8") (pinfunction "GND_8") (pintype "unspecified"))
      (node (ref "D24") (pin "3") (pinfunction "GND_3") (pintype "unspecified"))
      (node (ref "D24") (pin "8") (pinfunction "GND_8") (pintype "unspecified"))
      (node (ref "D25") (pin "1") (pinfunction "1_1") (pintype "input"))
      (node (ref "D26") (pin "3") (pinfunction "GND_3") (pintype "unspecified"))
      (node (ref "D26") (pin "8") (pinfunction "GND_8") (pintype "unspecified"))
      (node (ref "D27") (pin "1") (pinfunction "1_1") (pintype "input"))
      (node (ref "D28") (pin "3") (pinfunction "GND_3") (pintype "unspecified"))
      (node (ref "D28") (pin "8") (pinfunction "GND_8") (pintype "unspecified"))
      (node (ref "D29") (pin "3") (pinfunction "GND_3") (pintype "unspecified"))
      (node (ref "D29") (pin "8") (pinfunction "GND_8") (pintype "unspecified"))
      (node (ref "D30") (pin "3") (pinfunction "GND_3") (pintype "unspecified"))
      (node (ref "D30") (pin "8") (pinfunction "GND_8") (pintype "unspecified"))
      (node (ref "D31") (pin "1") (pinfunction "1_1") (pintype "input"))
      (node (ref "D32") (pin "3") (pinfunction "GND_3") (pintype "unspecified"))
      (node (ref "D32") (pin "8") (pinfunction "GND_8") (pintype "unspecified"))
      (node (ref "D33") (pin "1") (pinfunction "1_1") (pintype "input"))
      (node (ref "D35") (pin "3") (pinfunction "GND_3") (pintype "unspecified"))
      (node (ref "D35") (pin "8") (pinfunction "GND_8") (pintype "unspecified"))
      (node (ref "D36") (pin "3") (pinfunction "GND_3") (pintype "unspecified"))
      (node (ref "D36") (pin "8") (pinfunction "GND_8") (pintype "unspecified"))
      (node (ref "D37") (pin "3") (pinfunction "GND_3") (pintype "unspecified"))
      (node (ref "D37") (pin "8") (pinfunction "GND_8") (pintype "unspecified"))
      (node (ref "D38") (pin "3") (pinfunction "GND_3") (pintype "unspecified"))
      (node (ref "D38") (pin "8") (pinfunction "GND_8") (pintype "unspecified"))
      (node (ref "D39") (pin "1") (pinfunction "1_1") (pintype "input"))
      (node (ref "D40") (pin "1") (pinfunction "1_1") (pintype "input"))
      (node (ref "D7") (pin "2") (pinfunction "2_2") (pintype "input"))
      (node (ref "D8") (pin "2") (pinfunction "2_2") (pintype "input"))
      (node (ref "D9") (pin "2") (pinfunction "2_2") (pintype "input"))
      (node (ref "H1") (pin "6") (pinfunction "6_6") (pintype "input"))
      (node (ref "H12") (pin "6") (pinfunction "6_6") (pintype "input"))
      (node (ref "H19") (pin "4") (pinfunction "4_4") (pintype "input"))
      (node (ref "H20") (pin "4") (pinfunction "4_4") (pintype "input"))
      (node (ref "H24") (pin "6") (pinfunction "6_6") (pintype "input"))
      (node (ref "H25") (pin "6") (pinfunction "6_6") (pintype "input"))
      (node (ref "H26") (pin "10") (pinfunction "10_10") (pintype "unspecified"))
      (node (ref "H28") (pin "1") (pinfunction "1_1") (pintype "unspecified"))
      (node (ref "H28") (pin "2") (pinfunction "2_2") (pintype "unspecified"))
      (node (ref "H28") (pin "3") (pinfunction "3_3") (pintype "unspecified"))
      (node (ref "H28") (pin "4") (pinfunction "4_4") (pintype "unspecified"))
      (node (ref "H28") (pin "5") (pinfunction "5_5") (pintype "unspecified"))
      (node (ref "H28") (pin "6") (pinfunction "6_6") (pintype "unspecified"))
      (node (ref "H28") (pin "7") (pinfunction "7_7") (pintype "unspecified"))
      (node (ref "H28") (pin "8") (pinfunction "8_8") (pintype "unspecified"))
      (node (ref "H30") (pin "7") (pinfunction "7_7") (pintype "unspecified"))
      (node (ref "H31") (pin "10") (pinfunction "10_10") (pintype "unspecified"))
      (node (ref "H33") (pin "1") (pinfunction "1_1") (pintype "unspecified"))
      (node (ref "H33") (pin "2") (pinfunction "2_2") (pintype "unspecified"))
      (node (ref "H33") (pin "3") (pinfunction "3_3") (pintype "unspecified"))
      (node (ref "H33") (pin "4") (pinfunction "4_4") (pintype "unspecified"))
      (node (ref "H33") (pin "5") (pinfunction "5_5") (pintype "unspecified"))
      (node (ref "H33") (pin "6") (pinfunction "6_6") (pintype "unspecified"))
      (node (ref "H33") (pin "7") (pinfunction "7_7") (pintype "unspecified"))
      (node (ref "H33") (pin "8") (pinfunction "8_8") (pintype "unspecified"))
      (node (ref "H6") (pin "6") (pinfunction "6_6") (pintype "input"))
      (node (ref "LED3") (pin "1") (pinfunction "C_1") (pintype "input"))
      (node (ref "OSC1") (pin "2") (pinfunction "GND_2") (pintype "unspecified"))
      (node (ref "Q4") (pin "2") (pinfunction "S_2") (pintype "input"))
      (node (ref "R1") (pin "1") (pinfunction "1_1") (pintype "input"))
      (node (ref "R114") (pin "1") (pinfunction "1_1") (pintype "input"))
      (node (ref "R130") (pin "1") (pinfunction "1_1") (pintype "input"))
      (node (ref "R149") (pin "1") (pinfunction "1_1") (pintype "input"))
      (node (ref "R152") (pin "1") (pinfunction "1_1") (pintype "input"))
      (node (ref "R165") (pin "1") (pinfunction "1_1") (pintype "input"))
      (node (ref "R167") (pin "1") (pinfunction "1_1") (pintype "input"))
      (node (ref "R168") (pin "1") (pinfunction "1_1") (pintype "input"))
      (node (ref "R170") (pin "1") (pinfunction "1_1") (pintype "input"))
      (node (ref "R171") (pin "1") (pinfunction "1_1") (pintype "input"))
      (node (ref "R173") (pin "1") (pinfunction "1_1") (pintype "input"))
      (node (ref "R174") (pin "1") (pinfunction "1_1") (pintype "input"))
      (node (ref "R176") (pin "1") (pinfunction "1_1") (pintype "input"))
      (node (ref "R181") (pin "1") (pinfunction "1_1") (pintype "input"))
      (node (ref "R182") (pin "2") (pinfunction "2_2") (pintype "input"))
      (node (ref "R184") (pin "1") (pinfunction "1_1") (pintype "input"))
      (node (ref "R187") (pin "1") (pinfunction "1_1") (pintype "input"))
      (node (ref "R21") (pin "1") (pinfunction "1_1") (pintype "input"))
      (node (ref "R37") (pin "1") (pinfunction "1_1") (pintype "input"))
      (node (ref "R40") (pin "1") (pinfunction "1_1") (pintype "input"))
      (node (ref "R43") (pin "1") (pinfunction "1_1") (pintype "input"))
      (node (ref "R44") (pin "2") (pinfunction "2_2") (pintype "input"))
      (node (ref "R51") (pin "1") (pinfunction "1_1") (pintype "input"))
      (node (ref "R56") (pin "1") (pinfunction "1_1") (pintype "input"))
      (node (ref "R73") (pin "1") (pinfunction "1_1") (pintype "input"))
      (node (ref "R75") (pin "1") (pinfunction "1_1") (pintype "input"))
      (node (ref "R78") (pin "1") (pinfunction "1_1") (pintype "input"))
      (node (ref "R89") (pin "1") (pinfunction "1_1") (pintype "input"))
      (node (ref "RJ1") (pin "10") (pinfunction "10_10") (pintype "unspecified"))
      (node (ref "RJ1") (pin "9") (pinfunction "9_9") (pintype "unspecified"))
      (node (ref "SW2") (pin "3") (pinfunction "3_3") (pintype "input"))
      (node (ref "SW2") (pin "4") (pinfunction "4_4") (pintype "input"))
      (node (ref "TF1") (pin "10") (pinfunction "GND_10") (pintype "unspecified"))
      (node (ref "TF1") (pin "11") (pinfunction "GND_11") (pintype "unspecified"))
      (node (ref "TF1") (pin "12") (pinfunction "GND_12") (pintype "unspecified"))
      (node (ref "TF1") (pin "13") (pinfunction "GND_13") (pintype "unspecified"))
      (node (ref "TF1") (pin "6") (pinfunction "VSS_6") (pintype "unspecified"))
      (node (ref "U12") (pin "2") (pinfunction "NC_2") (pintype "unspecified"))
      (node (ref "U12") (pin "4") (pinfunction "GNDA_4") (pintype "unspecified"))
      (node (ref "U12") (pin "6") (pinfunction "GNDIO_6") (pintype "unspecified"))
      (node (ref "U12") (pin "7") (pinfunction "PS_7") (pintype "unspecified"))
      (node (ref "U13") (pin "3") (pinfunction "VSS_3") (pintype "unspecified"))
      (node (ref "U13") (pin "5") (pinfunction "SDO_5") (pintype "unspecified"))
      (node (ref "U13") (pin "8") (pinfunction "VSS_8") (pintype "unspecified"))
      (node (ref "U13") (pin "9") (pinfunction "VSS_9") (pintype "unspecified"))
      (node (ref "U14") (pin "A1") (pinfunction "PS_A1") (pintype "unspecified"))
      (node (ref "U14") (pin "A5") (pinfunction "CSB_A5") (pintype "unspecified"))
      (node (ref "U14") (pin "C1") (pinfunction "SDO_C1") (pintype "unspecified"))
      (node (ref "U14") (pin "C5") (pinfunction "GND_C5") (pintype "unspecified"))
      (node (ref "U14") (pin "E1") (pinfunction "GND_E1") (pintype "unspecified"))
      (node (ref "U14") (pin "E3") (pinfunction "GND_E3") (pintype "unspecified"))
      (node (ref "U15") (pin "2") (pinfunction "GND_2") (pintype "bidirectional"))
      (node (ref "U15") (pin "8") (pinfunction "S_8") (pintype "input"))
      (node (ref "U15") (pin "9") (pinfunction "EP_9") (pintype "bidirectional"))
      (node (ref "U16") (pin "B2") (pinfunction "GND_B2") (pintype "unspecified"))
      (node (ref "U17") (pin "5") (pinfunction "5_5") (pintype "unspecified"))
      (node (ref "U17") (pin "6") (pinfunction "6_6") (pintype "unspecified"))
      (node (ref "U17") (pin "7") (pinfunction "7_7") (pintype "unspecified"))
      (node (ref "U17") (pin "8") (pinfunction "8_8") (pintype "unspecified"))
      (node (ref "U18") (pin "10") (pinfunction "GND_10") (pintype "unspecified"))
      (node (ref "U18") (pin "25") (pinfunction "EP_25") (pintype "unspecified"))
      (node (ref "U19") (pin "5") (pinfunction "5_5") (pintype "unspecified"))
      (node (ref "U19") (pin "6") (pinfunction "6_6") (pintype "unspecified"))
      (node (ref "U19") (pin "7") (pinfunction "7_7") (pintype "unspecified"))
      (node (ref "U19") (pin "8") (pinfunction "8_8") (pintype "unspecified"))
      (node (ref "U20") (pin "2") (pinfunction "VSS_2") (pintype "unspecified"))
      (node (ref "U20") (pin "6") (pinfunction "VBAT_6") (pintype "unspecified"))
      (node (ref "U20") (pin "9") (pinfunction "EP_9") (pintype "unspecified"))
      (node (ref "U23") (pin "2") (pinfunction "VSS_2") (pintype "unspecified"))
      (node (ref "U23") (pin "6") (pinfunction "VBAT_6") (pintype "unspecified"))
      (node (ref "U23") (pin "9") (pinfunction "EP_9") (pintype "unspecified"))
      (node (ref "U26") (pin "4") (pinfunction "GND_4") (pintype "unspecified"))
      (node (ref "U27") (pin "11") (pinfunction "EP_11") (pintype "unspecified"))
      (node (ref "U27") (pin "4") (pinfunction "GND_4") (pintype "unspecified"))
      (node (ref "U28") (pin "D5") (pinfunction "VSS_D5") (pintype "unspecified"))
      (node (ref "U28") (pin "D7") (pinfunction "VSS_D7") (pintype "unspecified"))
      (node (ref "U28") (pin "D8") (pinfunction "VSS_D8") (pintype "unspecified"))
      (node (ref "U28") (pin "D9") (pinfunction "VSS_D9") (pintype "unspecified"))
      (node (ref "U28") (pin "F10") (pinfunction "VSS_F10") (pintype "unspecified"))
      (node (ref "U28") (pin "F12") (pinfunction "VSS_F12") (pintype "unspecified"))
      (node (ref "U28") (pin "F2") (pinfunction "VSS_F2") (pintype "unspecified"))
      (node (ref "U28") (pin "F6") (pinfunction "VSS_F6") (pintype "unspecified"))
      (node (ref "U28") (pin "F7") (pinfunction "VSS_F7") (pintype "unspecified"))
      (node (ref "U28") (pin "F8") (pinfunction "VSS_F8") (pintype "unspecified"))
      (node (ref "U28") (pin "F9") (pinfunction "VSS_F9") (pintype "unspecified"))
      (node (ref "U28") (pin "G10") (pinfunction "VSS_G10") (pintype "unspecified"))
      (node (ref "U28") (pin "G12") (pinfunction "VSS_G12") (pintype "unspecified"))
      (node (ref "U28") (pin "G2") (pinfunction "VSS_G2") (pintype "unspecified"))
      (node (ref "U28") (pin "G6") (pinfunction "VSS_G6") (pintype "unspecified"))
      (node (ref "U28") (pin "G7") (pinfunction "VSS_G7") (pintype "unspecified"))
      (node (ref "U28") (pin "G8") (pinfunction "VSS_G8") (pintype "unspecified"))
      (node (ref "U28") (pin "G9") (pinfunction "VSS_G9") (pintype "unspecified"))
      (node (ref "U28") (pin "H10") (pinfunction "VSS_H10") (pintype "unspecified"))
      (node (ref "U28") (pin "H12") (pinfunction "VSS_H12") (pintype "unspecified"))
      (node (ref "U28") (pin "H6") (pinfunction "VSS_H6") (pintype "unspecified"))
      (node (ref "U28") (pin "H7") (pinfunction "VSS_H7") (pintype "unspecified"))
      (node (ref "U28") (pin "H8") (pinfunction "VSS_H8") (pintype "unspecified"))
      (node (ref "U28") (pin "H9") (pinfunction "VSS_H9") (pintype "unspecified"))
      (node (ref "U28") (pin "J10") (pinfunction "VSS_J10") (pintype "unspecified"))
      (node (ref "U28") (pin "J6") (pinfunction "VSS_J6") (pintype "unspecified"))
      (node (ref "U28") (pin "J7") (pinfunction "VSS_J7") (pintype "unspecified"))
      (node (ref "U28") (pin "J8") (pinfunction "VSS_J8") (pintype "unspecified"))
      (node (ref "U28") (pin "J9") (pinfunction "VSS_J9") (pintype "unspecified"))
      (node (ref "U28") (pin "K10") (pinfunction "VSS_K10") (pintype "unspecified"))
      (node (ref "U28") (pin "K6") (pinfunction "VSS_K6") (pintype "unspecified"))
      (node (ref "U28") (pin "K7") (pinfunction "VSS_K7") (pintype "unspecified"))
      (node (ref "U28") (pin "K8") (pinfunction "VSS_K8") (pintype "unspecified"))
      (node (ref "U28") (pin "K9") (pinfunction "VSS_K9") (pintype "unspecified"))
      (node (ref "U28") (pin "L4") (pinfunction "VSS_L4") (pintype "unspecified"))
      (node (ref "U28") (pin "M1") (pinfunction "VSSA_M1") (pintype "unspecified"))
      (node (ref "U28") (pin "M8") (pinfunction "VSS_M8") (pintype "unspecified"))
      (node (ref "U28") (pin "M9") (pinfunction "VSS_M9") (pintype "unspecified"))
      (node (ref "U29") (pin "2") (pinfunction "GND_2") (pintype "unspecified"))
      (node (ref "U3") (pin "2") (pinfunction "NC_2") (pintype "unspecified"))
      (node (ref "U3") (pin "4") (pinfunction "NC_4") (pintype "unspecified"))
      (node (ref "U30") (pin "6") (pinfunction "6_6") (pintype "unspecified"))
      (node (ref "U30") (pin "7") (pinfunction "7_7") (pintype "unspecified"))
      (node (ref "U30") (pin "8") (pinfunction "8_8") (pintype "unspecified"))
      (node (ref "U31") (pin "18") (pinfunction "GND_18") (pintype "unspecified"))
      (node (ref "U31") (pin "20") (pinfunction "RESV_20") (pintype "unspecified"))
      (node (ref "U31") (pin "25") (pinfunction "EP_25") (pintype "unspecified"))
      (node (ref "U32") (pin "2") (pinfunction "GND_2") (pintype "bidirectional"))
      (node (ref "U32") (pin "8") (pinfunction "S_8") (pintype "input"))
      (node (ref "U32") (pin "9") (pinfunction "EP_9") (pintype "bidirectional"))
      (node (ref "U33") (pin "3") (pinfunction "VSS_3") (pintype "unspecified"))
      (node (ref "U33") (pin "8") (pinfunction "VSS_8") (pintype "unspecified"))
      (node (ref "U33") (pin "9") (pinfunction "VSS_9") (pintype "unspecified"))
      (node (ref "U34") (pin "6") (pinfunction "GND_6") (pintype "unspecified"))
      (node (ref "U35") (pin "1") (pinfunction "A0_1") (pintype "unspecified"))
      (node (ref "U35") (pin "2") (pinfunction "A1_2") (pintype "unspecified"))
      (node (ref "U35") (pin "3") (pinfunction "A2_3") (pintype "unspecified"))
      (node (ref "U35") (pin "4") (pinfunction "VSS_4") (pintype "unspecified"))
      (node (ref "U35") (pin "7") (pinfunction "WP_7") (pintype "unspecified"))
      (node (ref "U40") (pin "13") (pinfunction "AGND_13") (pintype "unspecified"))
      (node (ref "U40") (pin "17") (pinfunction "AGND_17") (pintype "unspecified"))
      (node (ref "U40") (pin "29") (pinfunction "DGND_29") (pintype "unspecified"))
      (node (ref "U40") (pin "40") (pinfunction "IOGND_40") (pintype "unspecified"))
      (node (ref "U40") (pin "41") (pinfunction "DAP_41") (pintype "unspecified"))
      (node (ref "U42") (pin "2") (pinfunction "GND_2") (pintype "unspecified"))
      (node (ref "U42") (pin "9") (pinfunction "EP_9") (pintype "unspecified"))
      (node (ref "U43") (pin "2") (pinfunction "GND_2") (pintype "unspecified"))
      (node (ref "U43") (pin "5") (pinfunction "EN1_5") (pintype "unspecified"))
      (node (ref "U43") (pin "9") (pinfunction "EP_9") (pintype "unspecified"))
      (node (ref "U48") (pin "2") (pinfunction "GND_2") (pintype "unspecified"))
      (node (ref "U49") (pin "2") (pinfunction "GND_2") (pintype "unspecified"))
      (node (ref "U5") (pin "4") (pinfunction "VSS_4") (pintype "unspecified"))
      (node (ref "U50") (pin "2") (pinfunction "GND_2") (pintype "unspecified"))
      (node (ref "U51") (pin "2") (pinfunction "GND_2") (pintype "unspecified"))
      (node (ref "U52") (pin "2") (pinfunction "-_2") (pintype "unspecified"))
      (node (ref "U53") (pin "23") (pinfunction "VSS_1_23") (pintype "unspecified"))
      (node (ref "U53") (pin "35") (pinfunction "VSS_2_35") (pintype "unspecified"))
      (node (ref "U53") (pin "47") (pinfunction "VSS_3_47") (pintype "unspecified"))
      (node (ref "U53") (pin "8") (pinfunction "VSSA_8") (pintype "unspecified"))
      (node (ref "U54") (pin "2") (pinfunction "GND_2") (pintype "unspecified"))
      (node (ref "U54") (pin "4") (pinfunction "GND_4") (pintype "unspecified"))
      (node (ref "U9") (pin "1") (pinfunction "GND_1") (pintype "unspecified"))
      (node (ref "U9") (pin "2") (pinfunction "GND_2") (pintype "unspecified"))
      (node (ref "U9") (pin "3") (pinfunction "GND_3") (pintype "unspecified"))
      (node (ref "U9") (pin "4") (pinfunction "GND_4") (pintype "unspecified"))
      (node (ref "U9") (pin "A1B12") (pinfunction "GND_A1B12") (pintype "unspecified"))
      (node (ref "U9") (pin "B1A12") (pinfunction "GND_B1A12") (pintype "unspecified"))
    )
    (net (code "81") (name "GPS1_3V3") (class "Default")
      (node (ref "C144") (pin "3") (pinfunction "OUT_3") (pintype "unspecified"))
      (node (ref "CN16") (pin "8") (pinfunction "8_8") (pintype "unspecified"))
      (node (ref "H26") (pin "8") (pinfunction "8_8") (pintype "unspecified"))
    )
    (net (code "82") (name "GPS1_5V") (class "Default")
      (node (ref "C142") (pin "3") (pinfunction "OUT_3") (pintype "unspecified"))
      (node (ref "D18") (pin "2") (pinfunction "2_2") (pintype "input"))
    )
    (net (code "83") (name "GPS1_I2C_SCL") (class "Default")
      (node (ref "CN16") (pin "4") (pinfunction "4_4") (pintype "unspecified"))
      (node (ref "D22") (pin "4") (pinfunction "I/O_4") (pintype "unspecified"))
      (node (ref "D22") (pin "7") (pinfunction "NC_7") (pintype "unspecified"))
      (node (ref "H26") (pin "4") (pinfunction "4_4") (pintype "unspecified"))
      (node (ref "R126") (pin "2") (pinfunction "2_2") (pintype "input"))
    )
    (net (code "84") (name "GPS1_I2C_SDA") (class "Default")
      (node (ref "CN16") (pin "5") (pinfunction "5_5") (pintype "unspecified"))
      (node (ref "D22") (pin "5") (pinfunction "I/O_5") (pintype "unspecified"))
      (node (ref "D22") (pin "6") (pinfunction "NC_6") (pintype "unspecified"))
      (node (ref "H26") (pin "5") (pinfunction "5_5") (pintype "unspecified"))
      (node (ref "R127") (pin "2") (pinfunction "2_2") (pintype "input"))
    )
    (net (code "85") (name "GPS1_RX") (class "Default")
      (node (ref "CN16") (pin "3") (pinfunction "3_3") (pintype "unspecified"))
      (node (ref "D22") (pin "2") (pinfunction "I/O_2") (pintype "unspecified"))
      (node (ref "D22") (pin "9") (pinfunction "NC_9") (pintype "unspecified"))
      (node (ref "H26") (pin "3") (pinfunction "3_3") (pintype "unspecified"))
      (node (ref "R125") (pin "2") (pinfunction "2_2") (pintype "input"))
    )
    (net (code "86") (name "GPS1_TX") (class "Default")
      (node (ref "CN16") (pin "2") (pinfunction "2_2") (pintype "unspecified"))
      (node (ref "D22") (pin "1") (pinfunction "I/O_1") (pintype "unspecified"))
      (node (ref "D22") (pin "10") (pinfunction "NC_10") (pintype "unspecified"))
      (node (ref "H26") (pin "2") (pinfunction "2_2") (pintype "unspecified"))
      (node (ref "R124") (pin "2") (pinfunction "2_2") (pintype "input"))
    )
    (net (code "87") (name "GPS1_VCC") (class "Default")
      (node (ref "CN16") (pin "1") (pinfunction "1_1") (pintype "unspecified"))
      (node (ref "H26") (pin "1") (pinfunction "1_1") (pintype "unspecified"))
    )
    (net (code "88") (name "GPS2_5V") (class "Default")
      (node (ref "C146") (pin "3") (pinfunction "OUT_3") (pintype "unspecified"))
      (node (ref "CN9") (pin "1") (pinfunction "1_1") (pintype "unspecified"))
      (node (ref "D20") (pin "2") (pinfunction "2_2") (pintype "input"))
      (node (ref "H12") (pin "1") (pinfunction "1_1") (pintype "input"))
    )
    (net (code "89") (name "GPS2_I2C_SCL") (class "Default")
      (node (ref "CN9") (pin "4") (pinfunction "4_4") (pintype "unspecified"))
      (node (ref "D24") (pin "4") (pinfunction "I/O_4") (pintype "unspecified"))
      (node (ref "D24") (pin "7") (pinfunction "NC_7") (pintype "unspecified"))
      (node (ref "H12") (pin "4") (pinfunction "4_4") (pintype "input"))
      (node (ref "R133") (pin "2") (pinfunction "2_2") (pintype "input"))
    )
    (net (code "90") (name "GPS2_I2C_SDA") (class "Default")
      (node (ref "CN9") (pin "5") (pinfunction "5_5") (pintype "unspecified"))
      (node (ref "D24") (pin "5") (pinfunction "I/O_5") (pintype "unspecified"))
      (node (ref "D24") (pin "6") (pinfunction "NC_6") (pintype "unspecified"))
      (node (ref "H12") (pin "5") (pinfunction "5_5") (pintype "input"))
      (node (ref "R134") (pin "2") (pinfunction "2_2") (pintype "input"))
    )
    (net (code "91") (name "GPS2_RX") (class "Default")
      (node (ref "CN9") (pin "3") (pinfunction "3_3") (pintype "unspecified"))
      (node (ref "D24") (pin "2") (pinfunction "I/O_2") (pintype "unspecified"))
      (node (ref "D24") (pin "9") (pinfunction "NC_9") (pintype "unspecified"))
      (node (ref "H12") (pin "3") (pinfunction "3_3") (pintype "input"))
      (node (ref "R132") (pin "2") (pinfunction "2_2") (pintype "input"))
    )
    (net (code "92") (name "GPS2_TX") (class "Default")
      (node (ref "CN9") (pin "2") (pinfunction "2_2") (pintype "unspecified"))
      (node (ref "D24") (pin "1") (pinfunction "I/O_1") (pintype "unspecified"))
      (node (ref "D24") (pin "10") (pinfunction "NC_10") (pintype "unspecified"))
      (node (ref "H12") (pin "2") (pinfunction "2_2") (pintype "input"))
      (node (ref "R131") (pin "2") (pinfunction "2_2") (pintype "input"))
    )
    (net (code "93") (name "HEATER") (class "Default")
      (node (ref "U28") (pin "R12") (pinfunction "PB10_R12") (pintype "unspecified"))
    )
    (net (code "94") (name "HW_REV_SENSE") (class "Default")
      (node (ref "R81") (pin "1") (pinfunction "1_1") (pintype "input"))
      (node (ref "R83") (pin "2") (pinfunction "2_2") (pintype "input"))
      (node (ref "U28") (pin "H4") (pinfunction "PH4_H4") (pintype "unspecified"))
    )
    (net (code "95") (name "HW_VER_REV_DRIVE") (class "Default")
      (node (ref "R82") (pin "1") (pinfunction "1_1") (pintype "input"))
      (node (ref "R83") (pin "1") (pinfunction "1_1") (pintype "input"))
      (node (ref "U28") (pin "N7") (pinfunction "PG0_N7") (pintype "unspecified"))
    )
    (net (code "96") (name "HW_VER_SENSE") (class "Default")
      (node (ref "R80") (pin "1") (pinfunction "1_1") (pintype "input"))
      (node (ref "R82") (pin "2") (pinfunction "2_2") (pintype "input"))
      (node (ref "U28") (pin "G4") (pinfunction "PH3_G4") (pintype "unspecified"))
    )
    (net (code "97") (name "I2C1_SCL_BASE_GPS1_MAG_LED_PM1") (class "Default")
      (node (ref "R126") (pin "1") (pinfunction "1_1") (pintype "input"))
      (node (ref "R34") (pin "2") (pinfunction "2_2") (pintype "input"))
      (node (ref "R90") (pin "1") (pinfunction "1_1") (pintype "input"))
      (node (ref "U28") (pin "A5") (pinfunction "PB8_A5") (pintype "unspecified"))
    )
    (net (code "98") (name "I2C1_SDA_BASE_GPS1_MAG_LED_PM1") (class "Default")
      (node (ref "R127") (pin "1") (pinfunction "1_1") (pintype "input"))
      (node (ref "R33") (pin "2") (pinfunction "2_2") (pintype "input"))
      (node (ref "R91") (pin "1") (pinfunction "1_1") (pintype "input"))
      (node (ref "U28") (pin "B4") (pinfunction "PB9_B4") (pintype "unspecified"))
    )
    (net (code "99") (name "I2C2_DRDY1_BMP388") (class "Default")
      (node (ref "JP25") (pin "1") (pinfunction "1_1") (pintype "input"))
      (node (ref "U28") (pin "K13") (pinfunction "PG5_K13") (pintype "unspecified"))
    )
    (net (code "100") (name "I2C2_SCL_BASE_GPS2_MAG_LED_PM2") (class "Default")
      (node (ref "JP24") (pin "1") (pinfunction "1_1") (pintype "input"))
      (node (ref "R133") (pin "1") (pinfunction "1_1") (pintype "input"))
      (node (ref "R46") (pin "2") (pinfunction "2_2") (pintype "input"))
      (node (ref "R92") (pin "1") (pinfunction "1_1") (pintype "input"))
      (node (ref "U28") (pin "H3") (pinfunction "PF1_H3") (pintype "unspecified"))
    )
    (net (code "101") (name "I2C2_SDA_BASE_GPS2_MAG_LED_PM2") (class "Default")
      (node (ref "JP23") (pin "1") (pinfunction "1_1") (pintype "input"))
      (node (ref "R134") (pin "1") (pinfunction "1_1") (pintype "input"))
      (node (ref "R45") (pin "2") (pinfunction "2_2") (pintype "input"))
      (node (ref "R93") (pin "1") (pinfunction "1_1") (pintype "input"))
      (node (ref "U28") (pin "E2") (pinfunction "PF0_E2") (pintype "unspecified"))
    )
    (net (code "102") (name "I2C3_SCL_BASE_MS5611_BARBED_EXTERNAL1") (class "Default")
      (node (ref "R145") (pin "1") (pinfunction "1_1") (pintype "input"))
      (node (ref "U28") (pin "F15") (pinfunction "PA8_F15") (pintype "unspecified"))
    )
    (net (code "103") (name "I2C3_SDA_BASE_MS5611_BARBED_EXTERNAL1") (class "Default")
      (node (ref "R146") (pin "1") (pinfunction "1_1") (pintype "input"))
      (node (ref "U28") (pin "M12") (pinfunction "PH8_M12") (pintype "unspecified"))
    )
    (net (code "104") (name "I2C4_SCL_FMU") (class "Default")
      (node (ref "JP27") (pin "1") (pinfunction "1_1") (pintype "input"))
      (node (ref "JP34") (pin "1") (pinfunction "1_1") (pintype "input"))
      (node (ref "JP36") (pin "1") (pinfunction "1_1") (pintype "input"))
      (node (ref "R95") (pin "1") (pinfunction "1_1") (pintype "input"))
      (node (ref "U28") (pin "R7") (pinfunction "PF14_R7") (pintype "unspecified"))
    )
    (net (code "105") (name "I2C4_SDA_FMU") (class "Default")
      (node (ref "JP26") (pin "1") (pinfunction "1_1") (pintype "input"))
      (node (ref "JP33") (pin "1") (pinfunction "1_1") (pintype "input"))
      (node (ref "JP35") (pin "1") (pinfunction "1_1") (pintype "input"))
      (node (ref "R94") (pin "1") (pinfunction "1_1") (pintype "input"))
      (node (ref "U28") (pin "P7") (pinfunction "PF15_P7") (pintype "unspecified"))
    )
    (net (code "106") (name "ICM20649_FSYNC") (class "Default")
      (node (ref "JP9") (pin "2") (pinfunction "2_2") (pintype "input"))
      (node (ref "U31") (pin "11") (pinfunction "FSYNC_11") (pintype "unspecified"))
    )
    (net (code "107") (name "ICM20649_INT1") (class "Default")
      (node (ref "JP10") (pin "2") (pinfunction "2_2") (pintype "input"))
      (node (ref "U31") (pin "12") (pinfunction "INT1_12") (pintype "unspecified"))
    )
    (net (code "108") (name "ICM20649_MISO") (class "Default")
      (node (ref "JP6") (pin "2") (pinfunction "2_2") (pintype "input"))
      (node (ref "U31") (pin "9") (pinfunction "SDO/AD0_9") (pintype "unspecified"))
    )
    (net (code "109") (name "ICM20649_MOSI") (class "Default")
      (node (ref "JP5") (pin "2") (pinfunction "2_2") (pintype "input"))
      (node (ref "U31") (pin "24") (pinfunction "SDA/SDI_24") (pintype "unspecified"))
    )
    (net (code "110") (name "ICM20649_NCS") (class "Default")
      (node (ref "JP8") (pin "2") (pinfunction "2_2") (pintype "input"))
      (node (ref "U31") (pin "22") (pinfunction "nCS_22") (pintype "unspecified"))
    )
    (net (code "111") (name "ICM20649_SCLK") (class "Default")
      (node (ref "JP7") (pin "2") (pinfunction "2_2") (pintype "input"))
      (node (ref "U31") (pin "23") (pinfunction "SCL/SCLK_23") (pintype "unspecified"))
    )
    (net (code "112") (name "ICM42688_CS") (class "Default")
      (node (ref "JP31") (pin "2") (pinfunction "2_2") (pintype "input"))
      (node (ref "U34") (pin "12") (pinfunction "AP_CS_12") (pintype "unspecified"))
    )
    (net (code "113") (name "ICM42688_INT1") (class "Default")
      (node (ref "H21") (pin "1") (pinfunction "1_1") (pintype "unspecified"))
      (node (ref "U34") (pin "4") (pinfunction "INT1/INT_4") (pintype "unspecified"))
    )
    (net (code "114") (name "ICM42688_INT2") (class "Default")
      (node (ref "JP32") (pin "2") (pinfunction "2_2") (pintype "input"))
      (node (ref "U34") (pin "9") (pinfunction "INT2/FSYNC/CLKIN_9") (pintype "unspecified"))
    )
    (net (code "115") (name "ICM42688_MISO") (class "Default")
      (node (ref "JP29") (pin "2") (pinfunction "2_2") (pintype "input"))
      (node (ref "U34") (pin "1") (pinfunction "AP_SDO/AP_AD0_1") (pintype "unspecified"))
    )
    (net (code "116") (name "ICM42688_MOSI") (class "Default")
      (node (ref "JP30") (pin "2") (pinfunction "2_2") (pintype "input"))
      (node (ref "U34") (pin "14") (pinfunction "AP_SDA/AP_SDIO/AP_SDI_14") (pintype "unspecified"))
    )
    (net (code "117") (name "ICM42688_SCK") (class "Default")
      (node (ref "JP28") (pin "2") (pinfunction "2_2") (pintype "input"))
      (node (ref "U34") (pin "13") (pinfunction "AP_SCL/AP_SCLK_13") (pintype "unspecified"))
    )
    (net (code "118") (name "IO_CH1") (class "Default")
      (node (ref "R188") (pin "1") (pinfunction "1_1") (pintype "input"))
      (node (ref "U53") (pin "10") (pinfunction "PA0-WKUP_10") (pintype "unspecified"))
    )
    (net (code "119") (name "IO_CH2") (class "Default")
      (node (ref "R189") (pin "1") (pinfunction "1_1") (pintype "input"))
      (node (ref "U53") (pin "11") (pinfunction "PA1_11") (pintype "unspecified"))
    )
    (net (code "120") (name "IO_CH3") (class "Default")
      (node (ref "R190") (pin "1") (pinfunction "1_1") (pintype "input"))
      (node (ref "U53") (pin "45") (pinfunction "PB8_45") (pintype "unspecified"))
    )
    (net (code "121") (name "IO_CH4") (class "Default")
      (node (ref "R191") (pin "1") (pinfunction "1_1") (pintype "input"))
      (node (ref "U53") (pin "46") (pinfunction "PB9_46") (pintype "unspecified"))
    )
    (net (code "122") (name "IO_CH5") (class "Default")
      (node (ref "R192") (pin "1") (pinfunction "1_1") (pintype "input"))
      (node (ref "U53") (pin "16") (pinfunction "PA6_16") (pintype "unspecified"))
    )
    (net (code "123") (name "IO_CH6") (class "Default")
      (node (ref "R193") (pin "1") (pinfunction "1_1") (pintype "input"))
      (node (ref "U53") (pin "17") (pinfunction "PA7_17") (pintype "unspecified"))
    )
    (net (code "124") (name "IO_CH7") (class "Default")
      (node (ref "R194") (pin "1") (pinfunction "1_1") (pintype "input"))
      (node (ref "U53") (pin "18") (pinfunction "PB0_18") (pintype "unspecified"))
    )
    (net (code "125") (name "IO_CH8") (class "Default")
      (node (ref "R195") (pin "1") (pinfunction "1_1") (pintype "input"))
      (node (ref "U53") (pin "19") (pinfunction "PB1_19") (pintype "unspecified"))
    )
    (net (code "126") (name "IO_M1") (class "Default")
      (node (ref "D37") (pin "1") (pinfunction "I/O_1") (pintype "unspecified"))
      (node (ref "D37") (pin "10") (pinfunction "NC_10") (pintype "unspecified"))
      (node (ref "H32") (pin "1") (pinfunction "1_1") (pintype "unspecified"))
      (node (ref "R188") (pin "2") (pinfunction "2_2") (pintype "input"))
    )
    (net (code "127") (name "IO_M2") (class "Default")
      (node (ref "D37") (pin "2") (pinfunction "I/O_2") (pintype "unspecified"))
      (node (ref "D37") (pin "9") (pinfunction "NC_9") (pintype "unspecified"))
      (node (ref "H32") (pin "2") (pinfunction "2_2") (pintype "unspecified"))
      (node (ref "R189") (pin "2") (pinfunction "2_2") (pintype "input"))
    )
    (net (code "128") (name "IO_M3") (class "Default")
      (node (ref "D37") (pin "4") (pinfunction "I/O_4") (pintype "unspecified"))
      (node (ref "D37") (pin "7") (pinfunction "NC_7") (pintype "unspecified"))
      (node (ref "H32") (pin "3") (pinfunction "3_3") (pintype "unspecified"))
      (node (ref "R190") (pin "2") (pinfunction "2_2") (pintype "input"))
    )
    (net (code "129") (name "IO_M4") (class "Default")
      (node (ref "D37") (pin "5") (pinfunction "I/O_5") (pintype "unspecified"))
      (node (ref "D37") (pin "6") (pinfunction "NC_6") (pintype "unspecified"))
      (node (ref "H32") (pin "4") (pinfunction "4_4") (pintype "unspecified"))
      (node (ref "R191") (pin "2") (pinfunction "2_2") (pintype "input"))
    )
    (net (code "130") (name "IO_M5") (class "Default")
      (node (ref "D38") (pin "1") (pinfunction "I/O_1") (pintype "unspecified"))
      (node (ref "D38") (pin "10") (pinfunction "NC_10") (pintype "unspecified"))
      (node (ref "H32") (pin "5") (pinfunction "5_5") (pintype "unspecified"))
      (node (ref "R192") (pin "2") (pinfunction "2_2") (pintype "input"))
    )
    (net (code "131") (name "IO_M6") (class "Default")
      (node (ref "D38") (pin "2") (pinfunction "I/O_2") (pintype "unspecified"))
      (node (ref "D38") (pin "9") (pinfunction "NC_9") (pintype "unspecified"))
      (node (ref "H32") (pin "6") (pinfunction "6_6") (pintype "unspecified"))
      (node (ref "R193") (pin "2") (pinfunction "2_2") (pintype "input"))
    )
    (net (code "132") (name "IO_M7") (class "Default")
      (node (ref "D38") (pin "4") (pinfunction "I/O_4") (pintype "unspecified"))
      (node (ref "D38") (pin "7") (pinfunction "NC_7") (pintype "unspecified"))
      (node (ref "H32") (pin "7") (pinfunction "7_7") (pintype "unspecified"))
      (node (ref "R194") (pin "2") (pinfunction "2_2") (pintype "input"))
    )
    (net (code "133") (name "IO_M8") (class "Default")
      (node (ref "D38") (pin "5") (pinfunction "I/O_5") (pintype "unspecified"))
      (node (ref "D38") (pin "6") (pinfunction "NC_6") (pintype "unspecified"))
      (node (ref "H32") (pin "8") (pinfunction "8_8") (pintype "unspecified"))
      (node (ref "R195") (pin "2") (pinfunction "2_2") (pintype "input"))
    )
    (net (code "134") (name "IO_MCU_OSC_IN") (class "Default")
      (node (ref "C210") (pin "1") (pinfunction "1_1") (pintype "input"))
      (node (ref "U53") (pin "5") (pinfunction "PD0-OSC_IN_5") (pintype "unspecified"))
      (node (ref "U54") (pin "1") (pinfunction "OSC1_1") (pintype "unspecified"))
    )
    (net (code "135") (name "IO_MCU_OSC_OUT") (class "Default")
      (node (ref "C211") (pin "1") (pinfunction "1_1") (pintype "input"))
      (node (ref "U53") (pin "6") (pinfunction "PD1-OSC_OUT_6") (pintype "unspecified"))
      (node (ref "U54") (pin "3") (pinfunction "OSC2_3") (pintype "unspecified"))
    )
    (net (code "136") (name "IO_MCU_VDDA") (class "Default")
      (node (ref "C208") (pin "1") (pinfunction "1_1") (pintype "input"))
      (node (ref "C209") (pin "1") (pinfunction "1_1") (pintype "input"))
      (node (ref "L6") (pin "2") (pinfunction "2_2") (pintype "unspecified"))
      (node (ref "U53") (pin "9") (pinfunction "VDDA_9") (pintype "unspecified"))
    )
    (net (code "137") (name "IO_NRST") (class "Default")
      (node (ref "C152") (pin "1") (pinfunction "1_1") (pintype "input"))
      (node (ref "CN20") (pin "9") (pinfunction "9_9") (pintype "unspecified"))
      (node (ref "D36") (pin "4") (pinfunction "I/O_4") (pintype "unspecified"))
      (node (ref "H31") (pin "9") (pinfunction "9_9") (pintype "unspecified"))
      (node (ref "R150") (pin "1") (pinfunction "1_1") (pintype "input"))
      (node (ref "U42") (pin "3") (pinfunction "POR2_3") (pintype "unspecified"))
      (node (ref "U53") (pin "7") (pinfunction "NRST_7") (pintype "unspecified"))
    )
    (net (code "138") (name "IO_NSAFETY_SWITCH_LED_OUT") (class "Default")
      (node (ref "R197") (pin "1") (pinfunction "1_1") (pintype "input"))
      (node (ref "U53") (pin "26") (pinfunction "PB13_26") (pintype "unspecified"))
    )
    (net (code "139") (name "IO_PPM_INPUT") (class "Default")
      (node (ref "U53") (pin "29") (pinfunction "PA8_29") (pintype "unspecified"))
    )
    (net (code "140") (name "IO_RSSI_IN") (class "Default")
      (node (ref "U53") (pin "15") (pinfunction "PA5_15") (pintype "unspecified"))
      (node (ref "U53") (pin "33") (pinfunction "PA12_33") (pintype "unspecified"))
    )
    (net (code "141") (name "IO_SAFETY_SWITCH_IN") (class "Default")
      (node (ref "R196") (pin "1") (pinfunction "1_1") (pintype "input"))
      (node (ref "U53") (pin "41") (pinfunction "PB5_41") (pintype "unspecified"))
    )
    (net (code "142") (name "IO_SBUS_INPUT") (class "Default")
      (node (ref "U53") (pin "22") (pinfunction "PB11_22") (pintype "unspecified"))
    )
    (net (code "143") (name "IO_SBUS_OUTPUT") (class "Default")
      (node (ref "U53") (pin "21") (pinfunction "PB10_21") (pintype "unspecified"))
    )
    (net (code "144") (name "IO_SPARE_GPIO1") (class "Default")
      (node (ref "CN20") (pin "7") (pinfunction "7_7") (pintype "unspecified"))
      (node (ref "D36") (pin "1") (pinfunction "I/O_1") (pintype "unspecified"))
      (node (ref "D36") (pin "10") (pinfunction "NC_10") (pintype "unspecified"))
      (node (ref "H31") (pin "7") (pinfunction "7_7") (pintype "unspecified"))
      (node (ref "U53") (pin "42") (pinfunction "PB6_42") (pintype "unspecified"))
    )
    (net (code "145") (name "IO_SPARE_GPIO2") (class "Default")
      (node (ref "CN20") (pin "8") (pinfunction "8_8") (pintype "unspecified"))
      (node (ref "D36") (pin "2") (pinfunction "I/O_2") (pintype "unspecified"))
      (node (ref "D36") (pin "9") (pinfunction "NC_9") (pintype "unspecified"))
      (node (ref "H31") (pin "8") (pinfunction "8_8") (pintype "unspecified"))
      (node (ref "U53") (pin "43") (pinfunction "PB7_43") (pintype "unspecified"))
    )
    (net (code "146") (name "IO_SWCLK") (class "Default")
      (node (ref "CN20") (pin "5") (pinfunction "5_5") (pintype "unspecified"))
      (node (ref "D35") (pin "4") (pinfunction "I/O_4") (pintype "unspecified"))
      (node (ref "D35") (pin "7") (pinfunction "NC_7") (pintype "unspecified"))
      (node (ref "H31") (pin "5") (pinfunction "5_5") (pintype "unspecified"))
      (node (ref "U53") (pin "37") (pinfunction "PA14_37") (pintype "unspecified"))
    )
    (net (code "147") (name "IO_SWDIO") (class "Default")
      (node (ref "CN20") (pin "4") (pinfunction "4_4") (pintype "unspecified"))
      (node (ref "D35") (pin "2") (pinfunction "I/O_2") (pintype "unspecified"))
      (node (ref "D35") (pin "9") (pinfunction "NC_9") (pintype "unspecified"))
      (node (ref "H31") (pin "4") (pinfunction "4_4") (pintype "unspecified"))
      (node (ref "U53") (pin "34") (pinfunction "PA13_34") (pintype "unspecified"))
    )
    (net (code "148") (name "IO_SWO") (class "Default")
      (node (ref "CN20") (pin "6") (pinfunction "6_6") (pintype "unspecified"))
      (node (ref "D35") (pin "5") (pinfunction "I/O_5") (pintype "unspecified"))
      (node (ref "D35") (pin "6") (pinfunction "NC_6") (pintype "unspecified"))
      (node (ref "H31") (pin "6") (pinfunction "6_6") (pintype "unspecified"))
      (node (ref "U53") (pin "39") (pinfunction "PB3_39") (pintype "unspecified"))
    )
    (net (code "149") (name "IO_USART1_RX_DSM") (class "Default")
      (node (ref "R198") (pin "1") (pinfunction "1_1") (pintype "input"))
      (node (ref "U53") (pin "31") (pinfunction "PA10_31") (pintype "unspecified"))
    )
    (net (code "150") (name "IO_USART1_TX_DEBUG") (class "Default")
      (node (ref "CN20") (pin "2") (pinfunction "2_2") (pintype "unspecified"))
      (node (ref "D35") (pin "1") (pinfunction "I/O_1") (pintype "unspecified"))
      (node (ref "D35") (pin "10") (pinfunction "NC_10") (pintype "unspecified"))
      (node (ref "H31") (pin "2") (pinfunction "2_2") (pintype "unspecified"))
      (node (ref "U53") (pin "30") (pinfunction "PA9_30") (pintype "unspecified"))
    )
    (net (code "151") (name "IO_VDD_3V3") (class "Default")
      (node (ref "C156") (pin "1") (pinfunction "1_1") (pintype "input"))
      (node (ref "C157") (pin "1") (pinfunction "1_1") (pintype "input"))
      (node (ref "C204") (pin "1") (pinfunction "1_1") (pintype "input"))
      (node (ref "C205") (pin "1") (pinfunction "1_1") (pintype "input"))
      (node (ref "C206") (pin "1") (pinfunction "1_1") (pintype "input"))
      (node (ref "C207") (pin "1") (pinfunction "1_1") (pintype "input"))
      (node (ref "CN20") (pin "1") (pinfunction "1_1") (pintype "unspecified"))
      (node (ref "H31") (pin "1") (pinfunction "1_1") (pintype "unspecified"))
      (node (ref "L6") (pin "1") (pinfunction "1_1") (pintype "unspecified"))
      (node (ref "R150") (pin "2") (pinfunction "2_2") (pintype "input"))
      (node (ref "R180") (pin "1") (pinfunction "1_1") (pintype "input"))
      (node (ref "U42") (pin "7") (pinfunction "VOUT2_7") (pintype "unspecified"))
      (node (ref "U53") (pin "24") (pinfunction "VDD_1_24") (pintype "unspecified"))
      (node (ref "U53") (pin "36") (pinfunction "VDD_2_36") (pintype "unspecified"))
      (node (ref "U53") (pin "48") (pinfunction "VDD_3_48") (pintype "unspecified"))
    )
    (net (code "152") (name "IO_VDD_5V") (class "Default")
      (node (ref "C150") (pin "1") (pinfunction "1_1") (pintype "input"))
      (node (ref "C78") (pin "3") (pinfunction "OUT_3") (pintype "unspecified"))
      (node (ref "U42") (pin "1") (pinfunction "VIN_1") (pintype "unspecified"))
      (node (ref "U42") (pin "4") (pinfunction "EN2_4") (pintype "unspecified"))
    )
    (net (code "153") (name "IO_VDD_SERVO_SENS") (class "Default")
      (node (ref "R183") (pin "2") (pinfunction "2_2") (pintype "input"))
      (node (ref "R184") (pin "2") (pinfunction "2_2") (pintype "input"))
      (node (ref "U53") (pin "14") (pinfunction "PA4_14") (pintype "unspecified"))
    )
    (net (code "154") (name "NARMED") (class "Default")
      (node (ref "U28") (pin "B3") (pinfunction "PE6_B3") (pintype "unspecified"))
    )
    (net (code "155") (name "NBUS_OUT_EN") (class "Default")
      (node (ref "U53") (pin "40") (pinfunction "PB4_40") (pintype "unspecified"))
    )
    (net (code "156") (name "NFC_GPIO") (class "Default")
      (node (ref "R147") (pin "1") (pinfunction "1_1") (pintype "input"))
      (node (ref "U28") (pin "M2") (pinfunction "PC0_M2") (pintype "unspecified"))
    )
    (net (code "157") (name "NIO_LED_AMBER") (class "Default")
      (node (ref "R186") (pin "1") (pinfunction "1_1") (pintype "input"))
      (node (ref "U53") (pin "28") (pinfunction "PB15_28") (pintype "unspecified"))
    )
    (net (code "158") (name "NIO_LED_BLUE") (class "Default")
      (node (ref "R185") (pin "1") (pinfunction "1_1") (pintype "input"))
      (node (ref "U53") (pin "27") (pinfunction "PB14_27") (pintype "unspecified"))
    )
    (net (code "159") (name "NLED_BLUE") (class "Default")
      (node (ref "LED2") (pin "2") (pinfunction "C_2") (pintype "input"))
      (node (ref "U28") (pin "B2") (pinfunction "PE5_B2") (pintype "unspecified"))
    )
    (net (code "160") (name "NLED_GREEN") (class "Default")
      (node (ref "U28") (pin "B1") (pinfunction "PE4_B1") (pintype "unspecified"))
    )
    (net (code "161") (name "NLED_RED") (class "Default")
      (node (ref "LED1") (pin "1") (pinfunction "C_1") (pintype "input"))
      (node (ref "U28") (pin "A1") (pinfunction "PE3_A1") (pintype "unspecified"))
    )
    (net (code "162") (name "NPOWER_IN_A") (class "Default")
      (node (ref "U18") (pin "7") (pinfunction "VALID1#_7") (pintype "unspecified"))
      (node (ref "U28") (pin "M7") (pinfunction "PG1_M7") (pintype "unspecified"))
    )
    (net (code "163") (name "NPOWER_IN_B") (class "Default")
      (node (ref "U18") (pin "8") (pinfunction "VALID2#_8") (pintype "unspecified"))
      (node (ref "U28") (pin "L15") (pinfunction "PG2_L15") (pintype "unspecified"))
    )
    (net (code "164") (name "NPOWER_IN_C") (class "Default")
      (node (ref "U18") (pin "9") (pinfunction "VALID3#_9") (pintype "unspecified"))
      (node (ref "U28") (pin "K15") (pinfunction "PG3_K15") (pintype "unspecified"))
    )
    (net (code "165") (name "N_FMU_RESET") (class "Default")
      (node (ref "U27") (pin "5") (pinfunction "PG_5") (pintype "unspecified"))
    )
    (net (code "166") (name "Net-(C103-Pad2)") (class "Default")
      (node (ref "C103") (pin "2") (pinfunction "2_2") (pintype "input"))
      (node (ref "U28") (pin "M10") (pinfunction "VCAP_M10") (pintype "unspecified"))
    )
    (net (code "167") (name "Net-(C104-Pad2)") (class "Default")
      (node (ref "C104") (pin "2") (pinfunction "2_2") (pintype "input"))
      (node (ref "U28") (pin "F13") (pinfunction "VCAP_F13") (pintype "unspecified"))
    )
    (net (code "168") (name "Net-(C117-Pad1)") (class "Default")
      (node (ref "C117") (pin "1") (pinfunction "1_1") (pintype "input"))
      (node (ref "CN15") (pin "1") (pinfunction "1_1") (pintype "unspecified"))
      (node (ref "RJ1") (pin "6") (pinfunction "6_6") (pintype "unspecified"))
    )
    (net (code "169") (name "Net-(C117-Pad2)") (class "Default")
      (node (ref "C117") (pin "2") (pinfunction "2_2") (pintype "input"))
      (node (ref "L4") (pin "2") (pinfunction "2_2") (pintype "input"))
    )
    (net (code "170") (name "Net-(C118-Pad1)") (class "Default")
      (node (ref "C118") (pin "1") (pinfunction "1_1") (pintype "input"))
      (node (ref "CN15") (pin "2") (pinfunction "2_2") (pintype "unspecified"))
      (node (ref "RJ1") (pin "3") (pinfunction "3_3") (pintype "unspecified"))
    )
    (net (code "171") (name "Net-(C118-Pad2)") (class "Default")
      (node (ref "C118") (pin "2") (pinfunction "2_2") (pintype "input"))
      (node (ref "L4") (pin "3") (pinfunction "3_3") (pintype "input"))
    )
    (net (code "172") (name "Net-(C119-Pad1)") (class "Default")
      (node (ref "C119") (pin "1") (pinfunction "1_1") (pintype "input"))
      (node (ref "CN15") (pin "3") (pinfunction "3_3") (pintype "unspecified"))
      (node (ref "RJ1") (pin "2") (pinfunction "2_2") (pintype "unspecified"))
    )
    (net (code "173") (name "Net-(C119-Pad2)") (class "Default")
      (node (ref "C119") (pin "2") (pinfunction "2_2") (pintype "input"))
      (node (ref "L5") (pin "2") (pinfunction "2_2") (pintype "input"))
    )
    (net (code "174") (name "Net-(C120-Pad1)") (class "Default")
      (node (ref "C120") (pin "1") (pinfunction "1_1") (pintype "input"))
      (node (ref "CN15") (pin "4") (pinfunction "4_4") (pintype "unspecified"))
      (node (ref "RJ1") (pin "1") (pinfunction "1_1") (pintype "unspecified"))
    )
    (net (code "175") (name "Net-(C120-Pad2)") (class "Default")
      (node (ref "C120") (pin "2") (pinfunction "2_2") (pintype "input"))
      (node (ref "L5") (pin "3") (pinfunction "3_3") (pintype "input"))
    )
    (net (code "176") (name "Net-(C180-OUT)") (class "Default")
      (node (ref "C180") (pin "3") (pinfunction "OUT_3") (pintype "unspecified"))
      (node (ref "C181") (pin "1") (pinfunction "1_1") (pintype "input"))
      (node (ref "C182") (pin "1") (pinfunction "1_1") (pintype "input"))
      (node (ref "U48") (pin "1") (pinfunction "IN_1") (pintype "unspecified"))
    )
    (net (code "177") (name "Net-(C186-OUT)") (class "Default")
      (node (ref "C186") (pin "3") (pinfunction "OUT_3") (pintype "unspecified"))
      (node (ref "C187") (pin "1") (pinfunction "1_1") (pintype "input"))
      (node (ref "C188") (pin "1") (pinfunction "1_1") (pintype "input"))
      (node (ref "U49") (pin "1") (pinfunction "IN_1") (pintype "unspecified"))
    )
    (net (code "178") (name "Net-(C192-OUT)") (class "Default")
      (node (ref "C192") (pin "3") (pinfunction "OUT_3") (pintype "unspecified"))
      (node (ref "C193") (pin "1") (pinfunction "1_1") (pintype "input"))
      (node (ref "C194") (pin "1") (pinfunction "1_1") (pintype "input"))
      (node (ref "U50") (pin "1") (pinfunction "IN_1") (pintype "unspecified"))
    )
    (net (code "179") (name "Net-(C198-OUT)") (class "Default")
      (node (ref "C198") (pin "3") (pinfunction "OUT_3") (pintype "unspecified"))
      (node (ref "C199") (pin "1") (pinfunction "1_1") (pintype "input"))
      (node (ref "C200") (pin "1") (pinfunction "1_1") (pintype "input"))
      (node (ref "U51") (pin "1") (pinfunction "IN_1") (pintype "unspecified"))
    )
    (net (code "180") (name "Net-(C212-OUT)") (class "Default")
      (node (ref "C212") (pin "3") (pinfunction "OUT_3") (pintype "unspecified"))
      (node (ref "CN21") (pin "1") (pinfunction "1_1") (pintype "unspecified"))
      (node (ref "D39") (pin "2") (pinfunction "2_2") (pintype "input"))
    )
    (net (code "181") (name "Net-(CN21-Pad3)") (class "Default")
      (node (ref "CN21") (pin "3") (pinfunction "3_3") (pintype "unspecified"))
      (node (ref "D40") (pin "2") (pinfunction "2_2") (pintype "input"))
      (node (ref "R198") (pin "2") (pinfunction "2_2") (pintype "input"))
    )
    (net (code "182") (name "Net-(D7-Pad1)") (class "Default")
      (node (ref "D7") (pin "1") (pinfunction "1_1") (pintype "input"))
      (node (ref "R33") (pin "1") (pinfunction "1_1") (pintype "input"))
      (node (ref "U17") (pin "4") (pinfunction "4_4") (pintype "unspecified"))
    )
    (net (code "183") (name "Net-(D8-Pad1)") (class "Default")
      (node (ref "D8") (pin "1") (pinfunction "1_1") (pintype "input"))
      (node (ref "R34") (pin "1") (pinfunction "1_1") (pintype "input"))
      (node (ref "U17") (pin "3") (pinfunction "3_3") (pintype "unspecified"))
    )
    (net (code "184") (name "Net-(D9-Pad1)") (class "Default")
      (node (ref "D9") (pin "1") (pinfunction "1_1") (pintype "input"))
      (node (ref "R45") (pin "1") (pinfunction "1_1") (pintype "input"))
      (node (ref "U19") (pin "4") (pinfunction "4_4") (pintype "unspecified"))
    )
    (net (code "185") (name "Net-(D10-Pad1)") (class "Default")
      (node (ref "D10") (pin "1") (pinfunction "1_1") (pintype "input"))
      (node (ref "R46") (pin "1") (pinfunction "1_1") (pintype "input"))
      (node (ref "U19") (pin "3") (pinfunction "3_3") (pintype "unspecified"))
    )
    (net (code "186") (name "Net-(D34-K)") (class "Default")
      (node (ref "D34") (pin "1") (pinfunction "K_1") (pintype "input"))
      (node (ref "R177") (pin "1") (pinfunction "1_1") (pintype "input"))
    )
    (net (code "187") (name "Net-(LED1-A)") (class "Default")
      (node (ref "LED1") (pin "2") (pinfunction "A_2") (pintype "input"))
      (node (ref "R84") (pin "1") (pinfunction "1_1") (pintype "input"))
    )
    (net (code "188") (name "Net-(LED2-A)") (class "Default")
      (node (ref "LED2") (pin "1") (pinfunction "A_1") (pintype "input"))
      (node (ref "R85") (pin "1") (pinfunction "1_1") (pintype "input"))
    )
    (net (code "189") (name "Net-(LED3-A)") (class "Default")
      (node (ref "LED3") (pin "2") (pinfunction "A_2") (pintype "input"))
      (node (ref "R86") (pin "1") (pinfunction "1_1") (pintype "input"))
    )
    (net (code "190") (name "Net-(LED6-C)") (class "Default")
      (node (ref "LED6") (pin "1") (pinfunction "C_1") (pintype "input"))
      (node (ref "R113") (pin "1") (pinfunction "1_1") (pintype "input"))
    )
    (net (code "191") (name "Net-(LED7-C)") (class "Default")
      (node (ref "LED7") (pin "1") (pinfunction "C_1") (pintype "input"))
      (node (ref "R185") (pin "2") (pinfunction "2_2") (pintype "input"))
    )
    (net (code "192") (name "Net-(LED10-C)") (class "Default")
      (node (ref "LED10") (pin "2") (pinfunction "C_2") (pintype "input"))
      (node (ref "R186") (pin "2") (pinfunction "2_2") (pintype "input"))
    )
    (net (code "193") (name "Net-(LED11-C)") (class "Default")
      (node (ref "LED11") (pin "1") (pinfunction "C_1") (pintype "input"))
      (node (ref "R187") (pin "2") (pinfunction "2_2") (pintype "input"))
    )
    (net (code "194") (name "Net-(OSC1-OUT)") (class "Default")
      (node (ref "OSC1") (pin "3") (pinfunction "OUT_3") (pintype "unspecified"))
      (node (ref "R115") (pin "1") (pinfunction "1_1") (pintype "input"))
    )
    (net (code "195") (name "Net-(TF1-VDD)") (class "Default")
      (node (ref "C42") (pin "2") (pinfunction "2_2") (pintype "input"))
      (node (ref "TF1") (pin "4") (pinfunction "VDD_4") (pintype "unspecified"))
      (node (ref "U16") (pin "A2") (pinfunction "OUT_A2") (pintype "unspecified"))
    )
    (net (code "196") (name "Net-(U5-HOLD#)") (class "Default")
      (node (ref "R6") (pin "1") (pinfunction "1_1") (pintype "input"))
      (node (ref "U5") (pin "7") (pinfunction "HOLD#_7") (pintype "unspecified"))
    )
    (net (code "197") (name "Net-(U5-WP#)") (class "Default")
      (node (ref "R7") (pin "1") (pinfunction "1_1") (pintype "input"))
      (node (ref "U5") (pin "3") (pinfunction "WP#_3") (pintype "unspecified"))
    )
    (net (code "198") (name "Net-(U9-CC1)") (class "Default")
      (node (ref "R21") (pin "2") (pinfunction "2_2") (pintype "input"))
      (node (ref "U9") (pin "A5") (pinfunction "CC1_A5") (pintype "unspecified"))
      (node (ref "U9") (pin "B5") (pinfunction "CC2_B5") (pintype "unspecified"))
    )
    (net (code "199") (name "Net-(U13-VDD)") (class "Default")
      (node (ref "C35") (pin "2") (pinfunction "2_2") (pintype "input"))
      (node (ref "U13") (pin "10") (pinfunction "VDD_10") (pintype "unspecified"))
    )
    (net (code "200") (name "Net-(U15-CANH)") (class "Default")
      (node (ref "CN11") (pin "2") (pinfunction "2_2") (pintype "unspecified"))
      (node (ref "R31") (pin "1") (pinfunction "1_1") (pintype "input"))
      (node (ref "U15") (pin "7") (pinfunction "CANH_7") (pintype "bidirectional"))
    )
    (net (code "201") (name "Net-(U15-CANL)") (class "Default")
      (node (ref "CN11") (pin "3") (pinfunction "3_3") (pintype "unspecified"))
      (node (ref "R31") (pin "2") (pinfunction "2_2") (pintype "input"))
      (node (ref "U15") (pin "6") (pinfunction "CANL_6") (pintype "bidirectional"))
    )
    (net (code "202") (name "Net-(U18-HYS)") (class "Default")
      (node (ref "R44") (pin "1") (pinfunction "1_1") (pintype "input"))
      (node (ref "U18") (pin "24") (pinfunction "HYS_24") (pintype "unspecified"))
    )
    (net (code "203") (name "Net-(U18-OV1)") (class "Default")
      (node (ref "R36") (pin "1") (pinfunction "1_1") (pintype "input"))
      (node (ref "R37") (pin "2") (pinfunction "2_2") (pintype "input"))
      (node (ref "U18") (pin "2") (pinfunction "OV1_2") (pintype "unspecified"))
    )
    (net (code "204") (name "Net-(U18-OV2)") (class "Default")
      (node (ref "R39") (pin "1") (pinfunction "1_1") (pintype "input"))
      (node (ref "R40") (pin "2") (pinfunction "2_2") (pintype "input"))
      (node (ref "U18") (pin "4") (pinfunction "OV2_4") (pintype "unspecified"))
    )
    (net (code "205") (name "Net-(U18-OV3)") (class "Default")
      (node (ref "R42") (pin "1") (pinfunction "1_1") (pintype "input"))
      (node (ref "R43") (pin "2") (pinfunction "2_2") (pintype "input"))
      (node (ref "U18") (pin "6") (pinfunction "OV3_6") (pintype "unspecified"))
    )
    (net (code "206") (name "Net-(U18-UV1)") (class "Default")
      (node (ref "C50") (pin "1") (pinfunction "1_1") (pintype "input"))
      (node (ref "R35") (pin "1") (pinfunction "1_1") (pintype "input"))
      (node (ref "R36") (pin "2") (pinfunction "2_2") (pintype "input"))
      (node (ref "U18") (pin "1") (pinfunction "UV1_1") (pintype "unspecified"))
    )
    (net (code "207") (name "Net-(U18-UV2)") (class "Default")
      (node (ref "C51") (pin "1") (pinfunction "1_1") (pintype "input"))
      (node (ref "R38") (pin "1") (pinfunction "1_1") (pintype "input"))
      (node (ref "R39") (pin "2") (pinfunction "2_2") (pintype "input"))
      (node (ref "U18") (pin "3") (pinfunction "UV2_3") (pintype "unspecified"))
    )
    (net (code "208") (name "Net-(U18-UV3)") (class "Default")
      (node (ref "C52") (pin "1") (pinfunction "1_1") (pintype "input"))
      (node (ref "R41") (pin "1") (pinfunction "1_1") (pintype "input"))
      (node (ref "R42") (pin "2") (pinfunction "2_2") (pintype "input"))
      (node (ref "U18") (pin "5") (pinfunction "UV3_5") (pintype "unspecified"))
    )
    (net (code "209") (name "Net-(U18-V3)") (class "Default")
      (node (ref "R41") (pin "2") (pinfunction "2_2") (pintype "input"))
      (node (ref "U18") (pin "19") (pinfunction "V3_19") (pintype "unspecified"))
    )
    (net (code "210") (name "Net-(U20-CE#)") (class "Default")
      (node (ref "R50") (pin "2") (pinfunction "2_2") (pintype "input"))
      (node (ref "U20") (pin "5") (pinfunction "CE#_5") (pintype "unspecified"))
    )
    (net (code "211") (name "Net-(U20-FAULT#)") (class "Default")
      (node (ref "R49") (pin "2") (pinfunction "2_2") (pintype "input"))
      (node (ref "U20") (pin "4") (pinfunction "FAULT#_4") (pintype "unspecified"))
    )
    (net (code "212") (name "Net-(U20-ILIM)") (class "Default")
      (node (ref "R51") (pin "2") (pinfunction "2_2") (pintype "input"))
      (node (ref "U20") (pin "7") (pinfunction "ILIM_7") (pintype "unspecified"))
    )
    (net (code "213") (name "Net-(U23-CE#)") (class "Default")
      (node (ref "R55") (pin "2") (pinfunction "2_2") (pintype "input"))
      (node (ref "U23") (pin "5") (pinfunction "CE#_5") (pintype "unspecified"))
    )
    (net (code "214") (name "Net-(U23-FAULT#)") (class "Default")
      (node (ref "R54") (pin "2") (pinfunction "2_2") (pintype "input"))
      (node (ref "U23") (pin "4") (pinfunction "FAULT#_4") (pintype "unspecified"))
    )
    (net (code "215") (name "Net-(U23-ILIM)") (class "Default")
      (node (ref "R56") (pin "2") (pinfunction "2_2") (pintype "input"))
      (node (ref "U23") (pin "7") (pinfunction "ILIM_7") (pintype "unspecified"))
    )
    (net (code "216") (name "Net-(U26-FB{slash}VSET)") (class "Default")
      (node (ref "R74") (pin "1") (pinfunction "1_1") (pintype "input"))
      (node (ref "R75") (pin "2") (pinfunction "2_2") (pintype "input"))
      (node (ref "U26") (pin "9") (pinfunction "FB/VSET_9") (pintype "unspecified"))
    )
    (net (code "217") (name "Net-(U26-MODE{slash}S-CONF)") (class "Default")
      (node (ref "R73") (pin "2") (pinfunction "2_2") (pintype "input"))
      (node (ref "U26") (pin "7") (pinfunction "MODE/S-CONF_7") (pintype "unspecified"))
    )
    (net (code "218") (name "Net-(U26-SS{slash}TR)") (class "Default")
      (node (ref "C88") (pin "1") (pinfunction "1_1") (pintype "input"))
      (node (ref "U26") (pin "8") (pinfunction "SS/TR_8") (pintype "unspecified"))
    )
    (net (code "219") (name "Net-(U26-SW)") (class "Default")
      (node (ref "L1") (pin "1") (pinfunction "1_1") (pintype "input"))
      (node (ref "U26") (pin "2") (pinfunction "SW_2") (pintype "unspecified"))
    )
    (net (code "220") (name "Net-(U27-FB)") (class "Default")
      (node (ref "R77") (pin "1") (pinfunction "1_1") (pintype "input"))
      (node (ref "R78") (pin "2") (pinfunction "2_2") (pintype "input"))
      (node (ref "U27") (pin "3") (pinfunction "FB_3") (pintype "unspecified"))
    )
    (net (code "221") (name "Net-(U27-NR{slash}SS)") (class "Default")
      (node (ref "C90") (pin "1") (pinfunction "1_1") (pintype "input"))
      (node (ref "U27") (pin "8") (pinfunction "NR/SS_8") (pintype "unspecified"))
    )
    (net (code "222") (name "Net-(U29-D1(0))") (class "Default")
      (node (ref "CN13") (pin "3") (pinfunction "3_3") (pintype "unspecified"))
      (node (ref "R47") (pin "1") (pinfunction "1_1") (pintype "input"))
      (node (ref "U29") (pin "6") (pinfunction "D1(0)_6") (pintype "unspecified"))
    )
    (net (code "223") (name "Net-(U29-D1(i))") (class "Default")
      (node (ref "U29") (pin "1") (pinfunction "D1(i)_1") (pintype "unspecified"))
      (node (ref "U9") (pin "A6") (pinfunction "DP1_A6") (pintype "unspecified"))
      (node (ref "U9") (pin "B6") (pinfunction "DP2_B6") (pintype "unspecified"))
    )
    (net (code "224") (name "Net-(U29-D2(0))") (class "Default")
      (node (ref "CN13") (pin "2") (pinfunction "2_2") (pintype "unspecified"))
      (node (ref "R48") (pin "1") (pinfunction "1_1") (pintype "input"))
      (node (ref "U29") (pin "4") (pinfunction "D2(0)_4") (pintype "unspecified"))
    )
    (net (code "225") (name "Net-(U29-D2(i))") (class "Default")
      (node (ref "U29") (pin "3") (pinfunction "D2(i)_3") (pintype "unspecified"))
      (node (ref "U9") (pin "A7") (pinfunction "DN1_A7") (pintype "unspecified"))
      (node (ref "U9") (pin "B7") (pinfunction "DN2_B7") (pintype "unspecified"))
    )
    (net (code "226") (name "Net-(U31-REGOUT)") (class "Default")
      (node (ref "C93") (pin "2") (pinfunction "2_2") (pintype "input"))
      (node (ref "U31") (pin "10") (pinfunction "REGOUT_10") (pintype "unspecified"))
    )
    (net (code "227") (name "Net-(U32-CANH)") (class "Default")
      (node (ref "CN14") (pin "2") (pinfunction "2_2") (pintype "unspecified"))
      (node (ref "R87") (pin "1") (pinfunction "1_1") (pintype "input"))
      (node (ref "U32") (pin "7") (pinfunction "CANH_7") (pintype "bidirectional"))
    )
    (net (code "228") (name "Net-(U32-CANL)") (class "Default")
      (node (ref "CN14") (pin "3") (pinfunction "3_3") (pintype "unspecified"))
      (node (ref "R87") (pin "2") (pinfunction "2_2") (pintype "input"))
      (node (ref "U32") (pin "6") (pinfunction "CANL_6") (pintype "bidirectional"))
    )
    (net (code "229") (name "Net-(U33-VDD)") (class "Default")
      (node (ref "C97") (pin "2") (pinfunction "2_2") (pintype "input"))
      (node (ref "U33") (pin "10") (pinfunction "VDD_10") (pintype "unspecified"))
    )
    (net (code "230") (name "Net-(U40-CRS{slash}CRS_DV{slash}LED_CFG)") (class "Default")
      (node (ref "R111") (pin "1") (pinfunction "1_1") (pintype "input"))
      (node (ref "U40") (pin "33") (pinfunction "CRS/CRS_DV/LED_CFG_33") (pintype "unspecified"))
    )
    (net (code "231") (name "Net-(U40-LED_SPEED{slash}AN1)") (class "Default")
      (node (ref "R113") (pin "2") (pinfunction "2_2") (pintype "input"))
      (node (ref "U40") (pin "21") (pinfunction "LED_SPEED/AN1_21") (pintype "unspecified"))
    )
    (net (code "232") (name "Net-(U40-PFBIN1)") (class "Default")
      (node (ref "C125") (pin "1") (pinfunction "1_1") (pintype "input"))
      (node (ref "C126") (pin "1") (pinfunction "1_1") (pintype "input"))
      (node (ref "C127") (pin "1") (pinfunction "1_1") (pintype "input"))
      (node (ref "C128") (pin "1") (pinfunction "1_1") (pintype "input"))
      (node (ref "U40") (pin "16") (pinfunction "PFBIN1_16") (pintype "unspecified"))
      (node (ref "U40") (pin "19") (pinfunction "PFBOUT_19") (pintype "unspecified"))
      (node (ref "U40") (pin "30") (pinfunction "PFBIN2_30") (pintype "unspecified"))
    )
    (net (code "233") (name "Net-(U40-RBIAS)") (class "Default")
      (node (ref "R114") (pin "2") (pinfunction "2_2") (pintype "input"))
      (node (ref "U40") (pin "20") (pinfunction "RBIAS_20") (pintype "unspecified"))
    )
    (net (code "234") (name "Net-(U40-RX_DV{slash}MII_MODE)") (class "Default")
      (node (ref "R112") (pin "1") (pinfunction "1_1") (pintype "input"))
      (node (ref "U40") (pin "32") (pinfunction "RX_DV/MII_MODE_32") (pintype "unspecified"))
    )
    (net (code "235") (name "Net-(U42-CSET2)") (class "Default")
      (node (ref "C151") (pin "1") (pinfunction "1_1") (pintype "input"))
      (node (ref "U42") (pin "6") (pinfunction "CSET2_6") (pintype "unspecified"))
    )
    (net (code "236") (name "Net-(U43-CSET2)") (class "Default")
      (node (ref "C161") (pin "1") (pinfunction "1_1") (pintype "input"))
      (node (ref "U43") (pin "6") (pinfunction "CSET2_6") (pintype "unspecified"))
    )
    (net (code "237") (name "Net-(U53-BOOT0)") (class "Default")
      (node (ref "R182") (pin "1") (pinfunction "1_1") (pintype "input"))
      (node (ref "U53") (pin "44") (pinfunction "BOOT0_44") (pintype "unspecified"))
    )
    (net (code "238") (name "Net-(U53-PA2)") (class "Default")
      (node (ref "R178") (pin "2") (pinfunction "2_2") (pintype "input"))
      (node (ref "U53") (pin "12") (pinfunction "PA2_12") (pintype "unspecified"))
    )
    (net (code "239") (name "Net-(U53-PA3)") (class "Default")
      (node (ref "R179") (pin "2") (pinfunction "2_2") (pintype "input"))
      (node (ref "U53") (pin "13") (pinfunction "PA3_13") (pintype "unspecified"))
    )
    (net (code "240") (name "Net-(U53-PA15)") (class "Default")
      (node (ref "R180") (pin "2") (pinfunction "2_2") (pintype "input"))
      (node (ref "U53") (pin "38") (pinfunction "PA15_38") (pintype "unspecified"))
    )
    (net (code "241") (name "Net-(U53-PB2)") (class "Default")
      (node (ref "R181") (pin "2") (pinfunction "2_2") (pintype "input"))
      (node (ref "U53") (pin "20") (pinfunction "PB2_20") (pintype "unspecified"))
    )
    (net (code "242") (name "PD15(PH11)") (class "Default")
      (node (ref "U28") (pin "L14") (pinfunction "PD15_L14") (pintype "unspecified"))
    )
    (net (code "243") (name "PG6") (class "Default")
      (node (ref "U28") (pin "J15") (pinfunction "PG6_J15") (pintype "unspecified"))
    )
    (net (code "244") (name "P_P_S_G1") (class "Default")
      (node (ref "Q1") (pin "2") (pinfunction "G1_2") (pintype "unspecified"))
      (node (ref "Q1") (pin "4") (pinfunction "G2_4") (pintype "unspecified"))
      (node (ref "U18") (pin "17") (pinfunction "G1_17") (pintype "unspecified"))
    )
    (net (code "245") (name "P_P_S_G2") (class "Default")
      (node (ref "Q2") (pin "2") (pinfunction "G1_2") (pintype "unspecified"))
      (node (ref "Q2") (pin "4") (pinfunction "G2_4") (pintype "unspecified"))
      (node (ref "U18") (pin "15") (pinfunction "G2_15") (pintype "unspecified"))
    )
    (net (code "246") (name "P_P_S_G3") (class "Default")
      (node (ref "Q3") (pin "2") (pinfunction "G1_2") (pintype "unspecified"))
      (node (ref "Q3") (pin "4") (pinfunction "G2_4") (pintype "unspecified"))
      (node (ref "U18") (pin "13") (pinfunction "G3_13") (pintype "unspecified"))
    )
    (net (code "247") (name "P_P_S_VS1") (class "Default")
      (node (ref "C49") (pin "1") (pinfunction "1_1") (pintype "input"))
      (node (ref "Q1") (pin "1") (pinfunction "S1_1") (pintype "unspecified"))
      (node (ref "Q1") (pin "3") (pinfunction "S2_3") (pintype "unspecified"))
      (node (ref "U18") (pin "18") (pinfunction "VS1_18") (pintype "unspecified"))
    )
    (net (code "248") (name "P_P_S_VS2") (class "Default")
      (node (ref "C55") (pin "1") (pinfunction "1_1") (pintype "input"))
      (node (ref "Q2") (pin "1") (pinfunction "S1_1") (pintype "unspecified"))
      (node (ref "Q2") (pin "3") (pinfunction "S2_3") (pintype "unspecified"))
      (node (ref "U18") (pin "16") (pinfunction "VS2_16") (pintype "unspecified"))
    )
    (net (code "249") (name "P_P_S_VS3") (class "Default")
      (node (ref "C58") (pin "1") (pinfunction "1_1") (pintype "input"))
      (node (ref "Q3") (pin "1") (pinfunction "S1_1") (pintype "unspecified"))
      (node (ref "Q3") (pin "3") (pinfunction "S2_3") (pintype "unspecified"))
      (node (ref "U18") (pin "14") (pinfunction "VS3_14") (pintype "unspecified"))
    )
    (net (code "250") (name "RX_DEBUG_CATHODE") (class "Default")
      (node (ref "D2") (pin "2") (pinfunction "I/O_2") (pintype "unspecified"))
      (node (ref "D2") (pin "9") (pinfunction "NC_9") (pintype "unspecified"))
      (node (ref "D3") (pin "1") (pinfunction "K_1") (pintype "input"))
      (node (ref "H1") (pin "3") (pinfunction "3_3") (pintype "input"))
      (node (ref "U30") (pin "3") (pinfunction "3_3") (pintype "unspecified"))
    )
    (net (code "251") (name "SAFETY_LED") (class "Default")
      (node (ref "CN16") (pin "7") (pinfunction "7_7") (pintype "unspecified"))
      (node (ref "D23") (pin "2") (pinfunction "I/O_2") (pintype "unspecified"))
      (node (ref "D23") (pin "9") (pinfunction "NC_9") (pintype "unspecified"))
      (node (ref "H26") (pin "7") (pinfunction "7_7") (pintype "unspecified"))
      (node (ref "R129") (pin "2") (pinfunction "2_2") (pintype "input"))
      (node (ref "R197") (pin "2") (pinfunction "2_2") (pintype "input"))
    )
    (net (code "252") (name "SAFETY_SWITCH_IN") (class "Default")
      (node (ref "CN16") (pin "6") (pinfunction "6_6") (pintype "unspecified"))
      (node (ref "D23") (pin "1") (pinfunction "I/O_1") (pintype "unspecified"))
      (node (ref "D23") (pin "10") (pinfunction "NC_10") (pintype "unspecified"))
      (node (ref "H26") (pin "6") (pinfunction "6_6") (pintype "unspecified"))
      (node (ref "R128") (pin "2") (pinfunction "2_2") (pintype "input"))
      (node (ref "R196") (pin "2") (pinfunction "2_2") (pintype "input"))
    )
    (net (code "253") (name "SCALED_V5") (class "Default")
      (node (ref "R88") (pin "1") (pinfunction "1_1") (pintype "input"))
      (node (ref "R89") (pin "2") (pinfunction "2_2") (pintype "input"))
      (node (ref "U28") (pin "R4") (pinfunction "PB1_R4") (pintype "unspecified"))
    )
    (net (code "254") (name "SCALED_VDD_3V3_SENSORS1") (class "Default")
      (node (ref "R166") (pin "1") (pinfunction "1_1") (pintype "input"))
      (node (ref "R167") (pin "2") (pinfunction "2_2") (pintype "input"))
      (node (ref "U28") (pin "N3") (pinfunction "PA0_N3") (pintype "unspecified"))
    )
    (net (code "255") (name "SCALED_VDD_3V3_SENSORS2") (class "Default")
      (node (ref "R169") (pin "1") (pinfunction "1_1") (pintype "input"))
      (node (ref "R170") (pin "2") (pinfunction "2_2") (pintype "input"))
      (node (ref "U28") (pin "N4") (pinfunction "PA4_N4") (pintype "unspecified"))
    )
    (net (code "256") (name "SCALED_VDD_3V3_SENSORS3") (class "Default")
      (node (ref "R172") (pin "1") (pinfunction "1_1") (pintype "input"))
      (node (ref "R173") (pin "2") (pinfunction "2_2") (pintype "input"))
      (node (ref "U28") (pin "R5") (pinfunction "PB0_R5") (pintype "unspecified"))
    )
    (net (code "257") (name "SCALED_VDD_3V3_SENSORS4") (class "Default")
      (node (ref "R175") (pin "1") (pinfunction "1_1") (pintype "input"))
      (node (ref "R176") (pin "2") (pinfunction "2_2") (pintype "input"))
      (node (ref "U28") (pin "P6") (pinfunction "PF12_P6") (pintype "unspecified"))
    )
    (net (code "258") (name "SDMMC2_CLK") (class "Default")
      (node (ref "TF1") (pin "5") (pinfunction "CLK_5") (pintype "unspecified"))
      (node (ref "U28") (pin "B11") (pinfunction "PD6_B11") (pintype "unspecified"))
    )
    (net (code "259") (name "SDMMC2_CMD") (class "Default")
      (node (ref "R16") (pin "1") (pinfunction "1_1") (pintype "input"))
      (node (ref "TF1") (pin "3") (pinfunction "CMD_3") (pintype "unspecified"))
      (node (ref "U28") (pin "A11") (pinfunction "PD7_A11") (pintype "unspecified"))
    )
    (net (code "260") (name "SDMMC2_D0") (class "Default")
      (node (ref "R17") (pin "1") (pinfunction "1_1") (pintype "input"))
      (node (ref "TF1") (pin "7") (pinfunction "DAT0_7") (pintype "unspecified"))
      (node (ref "U28") (pin "R14") (pinfunction "PB14_R14") (pintype "unspecified"))
    )
    (net (code "261") (name "SDMMC2_D1") (class "Default")
      (node (ref "R18") (pin "1") (pinfunction "1_1") (pintype "input"))
      (node (ref "TF1") (pin "8") (pinfunction "DAT1_8") (pintype "unspecified"))
      (node (ref "U28") (pin "R15") (pinfunction "PB15_R15") (pintype "unspecified"))
    )
    (net (code "262") (name "SDMMC2_D2") (class "Default")
      (node (ref "R14") (pin "1") (pinfunction "1_1") (pintype "input"))
      (node (ref "TF1") (pin "1") (pinfunction "DAT2_1") (pintype "unspecified"))
      (node (ref "U28") (pin "B9") (pinfunction "PG11_B9") (pintype "unspecified"))
    )
    (net (code "263") (name "SDMMC2_D3") (class "Default")
      (node (ref "R15") (pin "1") (pinfunction "1_1") (pintype "input"))
      (node (ref "TF1") (pin "2") (pinfunction "CD/DAT3_2") (pintype "unspecified"))
      (node (ref "U28") (pin "A9") (pinfunction "PB4_A9") (pintype "unspecified"))
    )
    (net (code "264") (name "SPI1_DRDY1_ICM20602") (class "Default")
      (node (ref "JP10") (pin "1") (pinfunction "1_1") (pintype "input"))
      (node (ref "U28") (pin "H2") (pinfunction "PF2_H2") (pintype "unspecified"))
    )
    (net (code "265") (name "SPI1_MISO_SENSOR1_ICM20602") (class "Default")
      (node (ref "JP6") (pin "1") (pinfunction "1_1") (pintype "input"))
      (node (ref "U28") (pin "C10") (pinfunction "PG9_C10") (pintype "unspecified"))
    )
    (net (code "266") (name "SPI1_MOSI_SENSOR1_ICM20602") (class "Default")
      (node (ref "JP5") (pin "1") (pinfunction "1_1") (pintype "input"))
      (node (ref "U28") (pin "A6") (pinfunction "PB5_A6") (pintype "unspecified"))
    )
    (net (code "267") (name "SPI1_NCS1_ICM20602") (class "Default")
      (node (ref "JP8") (pin "1") (pinfunction "1_1") (pintype "input"))
      (node (ref "U28") (pin "D3") (pinfunction "PI9_D3") (pintype "unspecified"))
    )
    (net (code "268") (name "SPI1_SCK_SENSOR1_ICM20602") (class "Default")
      (node (ref "JP7") (pin "1") (pinfunction "1_1") (pintype "input"))
    )
    (net (code "269") (name "SPI1_SCK_SENSORS1_ICM20602") (class "Default")
      (node (ref "U28") (pin "P4") (pinfunction "PA5_P4") (pintype "unspecified"))
    )
    (net (code "270") (name "SPI2_DRDY2_ISM330_INT2") (class "Default")
      (node (ref "JP32") (pin "1") (pinfunction "1_1") (pintype "input"))
      (node (ref "U28") (pin "D15") (pinfunction "PA10_D15") (pintype "unspecified"))
    )
    (net (code "271") (name "SPI2_MISO_SENSOR2_ISM330") (class "Default")
      (node (ref "JP29") (pin "1") (pinfunction "1_1") (pintype "input"))
      (node (ref "U28") (pin "C14") (pinfunction "PI2_C14") (pintype "unspecified"))
    )
    (net (code "272") (name "SPI2_MOSI_SENSOR2_ISM330") (class "Default")
      (node (ref "JP30") (pin "1") (pinfunction "1_1") (pintype "input"))
      (node (ref "U28") (pin "C13") (pinfunction "PI3_C13") (pintype "unspecified"))
    )
    (net (code "273") (name "SPI2_NCS1_ISM330") (class "Default")
      (node (ref "JP31") (pin "1") (pinfunction "1_1") (pintype "input"))
      (node (ref "U28") (pin "J4") (pinfunction "PH5_J4") (pintype "unspecified"))
    )
    (net (code "274") (name "SPI2_SCK_SENSOR2_ISM330") (class "Default")
      (node (ref "JP28") (pin "1") (pinfunction "1_1") (pintype "input"))
      (node (ref "U28") (pin "D14") (pinfunction "PI1_D14") (pintype "unspecified"))
    )
    (net (code "275") (name "SPI3_DRDY1_BMI088_INT1_ACCEL") (class "Default")
      (node (ref "JP21") (pin "1") (pinfunction "1_1") (pintype "input"))
      (node (ref "U28") (pin "C3") (pinfunction "PI6_C3") (pintype "unspecified"))
    )
    (net (code "276") (name "SPI3_DRDY2_BMI088_INT3_GYRO") (class "Default")
      (node (ref "JP22") (pin "1") (pinfunction "1_1") (pintype "input"))
      (node (ref "U28") (pin "C2") (pinfunction "PI7_C2") (pintype "unspecified"))
    )
    (net (code "277") (name "SPI3_MISO_SENSOR3_BMI088") (class "Default")
      (node (ref "JP17") (pin "1") (pinfunction "1_1") (pintype "input"))
      (node (ref "U28") (pin "B13") (pinfunction "PC11_B13") (pintype "unspecified"))
    )
    (net (code "278") (name "SPI3_MOSI_SENSOR3_BMI088") (class "Default")
      (node (ref "JP18") (pin "1") (pinfunction "1_1") (pintype "input"))
      (node (ref "U28") (pin "M6") (pinfunction "PB2_M6") (pintype "unspecified"))
    )
    (net (code "279") (name "SPI3_NCS1_BMI088_ACCEL") (class "Default")
      (node (ref "JP19") (pin "1") (pinfunction "1_1") (pintype "input"))
      (node (ref "U28") (pin "D4") (pinfunction "PI4_D4") (pintype "unspecified"))
    )
    (net (code "280") (name "SPI3_NCS2_BMI088_GYRO") (class "Default")
      (node (ref "JP20") (pin "1") (pinfunction "1_1") (pintype "input"))
      (node (ref "U28") (pin "D2") (pinfunction "PI8_D2") (pintype "unspecified"))
    )
    (net (code "281") (name "SPI3_SCK_SENSOR3_BMI088") (class "Default")
      (node (ref "JP16") (pin "1") (pinfunction "1_1") (pintype "input"))
      (node (ref "U28") (pin "B14") (pinfunction "PC10_B14") (pintype "unspecified"))
    )
    (net (code "282") (name "SPI4_DRDY1_BMM150_DRDY") (class "Default")
      (node (ref "U28") (pin "J2") (pinfunction "PF3_J2") (pintype "unspecified"))
    )
    (net (code "283") (name "SPI4_MISO_SENSOR4_BMM150") (class "Default")
      (node (ref "U28") (pin "N11") (pinfunction "PE13_N11") (pintype "unspecified"))
    )
    (net (code "284") (name "SPI4_MOSI_SENSOR4_BMM150") (class "Default")
      (node (ref "U28") (pin "P11") (pinfunction "PE14_P11") (pintype "unspecified"))
    )
    (net (code "285") (name "SPI4_NCS1_BMM150") (class "Default")
      (node (ref "U28") (pin "D13") (pinfunction "PH15_D13") (pintype "unspecified"))
    )
    (net (code "286") (name "SPI4_SCK_SENSOR4_BMM150") (class "Default")
      (node (ref "U28") (pin "R10") (pinfunction "PE12_R10") (pintype "unspecified"))
    )
    (net (code "287") (name "SPI5_MISO_FRAM") (class "Default")
      (node (ref "JP3") (pin "1") (pinfunction "1_1") (pintype "input"))
      (node (ref "U28") (pin "N12") (pinfunction "PH7_N12") (pintype "unspecified"))
    )
    (net (code "288") (name "SPI5_MOSI_FRAM") (class "Default")
      (node (ref "JP2") (pin "1") (pinfunction "1_1") (pintype "input"))
      (node (ref "U28") (pin "R6") (pinfunction "PF11_R6") (pintype "unspecified"))
    )
    (net (code "289") (name "SPI5_NCS1_FRAM") (class "Default")
      (node (ref "JP4") (pin "1") (pinfunction "1_1") (pintype "input"))
      (node (ref "U28") (pin "J14") (pinfunction "PG7_J14") (pintype "unspecified"))
    )
    (net (code "290") (name "SPI5_SCK_FRAM") (class "Default")
      (node (ref "JP1") (pin "1") (pinfunction "1_1") (pintype "input"))
      (node (ref "U28") (pin "K1") (pinfunction "PF7_K1") (pintype "unspecified"))
    )
    (net (code "291") (name "SPI6_DRDY1_EXTERNAL1") (class "Default")
      (node (ref "U28") (pin "N14") (pinfunction "PD11_N14") (pintype "unspecified"))
    )
    (net (code "292") (name "SPI6_DRDY2_EXTERNAL1") (class "Default")
      (node (ref "U28") (pin "N13") (pinfunction "PD12_N13") (pintype "unspecified"))
    )
    (net (code "293") (name "SPI6_MISO_EXTERNAL1") (class "Default")
      (node (ref "U28") (pin "P3") (pinfunction "PA6_P3") (pintype "unspecified"))
    )
    (net (code "294") (name "SPI6_MOSI_EXTERNAL1") (class "Default")
      (node (ref "U28") (pin "A7") (pinfunction "PG14_A7") (pintype "unspecified"))
    )
    (net (code "295") (name "SPI6_NCS1_EXTERNAL1") (class "Default")
      (node (ref "U28") (pin "E3") (pinfunction "PI10_E3") (pintype "unspecified"))
    )
    (net (code "296") (name "SPI6_NCS2_EXTERNAL1") (class "Default")
      (node (ref "U28") (pin "A13") (pinfunction "PA15_A13") (pintype "unspecified"))
    )
    (net (code "297") (name "SPI6_NRESET_EXTERNAL1") (class "Default")
      (node (ref "U28") (pin "L1") (pinfunction "PF10_L1") (pintype "unspecified"))
    )
    (net (code "298") (name "SPI6_SCK_EXTERNAL1") (class "Default")
      (node (ref "U28") (pin "A10") (pinfunction "PB3_A10") (pintype "unspecified"))
    )
    (net (code "299") (name "SPIX_SYNC") (class "Default")
      (node (ref "JP9") (pin "1") (pinfunction "1_1") (pintype "input"))
      (node (ref "U28") (pin "P9") (pinfunction "PE9_P9") (pintype "unspecified"))
    )
    (net (code "300") (name "TELEM1_5V") (class "Default")
      (node (ref "C137") (pin "3") (pinfunction "OUT_3") (pintype "unspecified"))
      (node (ref "CN2") (pin "1") (pinfunction "1_1") (pintype "input"))
      (node (ref "D13") (pin "2") (pinfunction "2_2") (pintype "input"))
      (node (ref "H6") (pin "1") (pinfunction "1_1") (pintype "input"))
    )
    (net (code "301") (name "TELEM1_CTS") (class "Default")
      (node (ref "CN2") (pin "4") (pinfunction "4_4") (pintype "input"))
      (node (ref "D12") (pin "4") (pinfunction "I/O_4") (pintype "unspecified"))
      (node (ref "D12") (pin "7") (pinfunction "NC_7") (pintype "unspecified"))
      (node (ref "H6") (pin "4") (pinfunction "4_4") (pintype "input"))
      (node (ref "R62") (pin "2") (pinfunction "2_2") (pintype "input"))
    )
    (net (code "302") (name "TELEM1_RTS") (class "Default")
      (node (ref "CN2") (pin "5") (pinfunction "5_5") (pintype "input"))
      (node (ref "D12") (pin "5") (pinfunction "I/O_5") (pintype "unspecified"))
      (node (ref "D12") (pin "6") (pinfunction "NC_6") (pintype "unspecified"))
      (node (ref "H6") (pin "5") (pinfunction "5_5") (pintype "input"))
      (node (ref "R63") (pin "2") (pinfunction "2_2") (pintype "input"))
    )
    (net (code "303") (name "TELEM1_RX") (class "Default")
      (node (ref "CN2") (pin "3") (pinfunction "3_3") (pintype "input"))
      (node (ref "D12") (pin "2") (pinfunction "I/O_2") (pintype "unspecified"))
      (node (ref "D12") (pin "9") (pinfunction "NC_9") (pintype "unspecified"))
      (node (ref "H6") (pin "3") (pinfunction "3_3") (pintype "input"))
      (node (ref "R61") (pin "2") (pinfunction "2_2") (pintype "input"))
    )
    (net (code "304") (name "TELEM1_TX") (class "Default")
      (node (ref "CN2") (pin "2") (pinfunction "2_2") (pintype "input"))
      (node (ref "D12") (pin "1") (pinfunction "I/O_1") (pintype "unspecified"))
      (node (ref "D12") (pin "10") (pinfunction "NC_10") (pintype "unspecified"))
      (node (ref "H6") (pin "2") (pinfunction "2_2") (pintype "input"))
      (node (ref "R120") (pin "2") (pinfunction "2_2") (pintype "input"))
    )
    (net (code "305") (name "TELEM2_5V") (class "Default")
      (node (ref "C138") (pin "3") (pinfunction "OUT_3") (pintype "unspecified"))
      (node (ref "CN17") (pin "1") (pinfunction "1_1") (pintype "input"))
      (node (ref "D25") (pin "2") (pinfunction "2_2") (pintype "input"))
      (node (ref "H24") (pin "1") (pinfunction "1_1") (pintype "input"))
    )
    (net (code "306") (name "TELEM2_CTS") (class "Default")
      (node (ref "CN17") (pin "4") (pinfunction "4_4") (pintype "input"))
      (node (ref "D26") (pin "4") (pinfunction "I/O_4") (pintype "unspecified"))
      (node (ref "D26") (pin "7") (pinfunction "NC_7") (pintype "unspecified"))
      (node (ref "H24") (pin "4") (pinfunction "4_4") (pintype "input"))
      (node (ref "R123") (pin "2") (pinfunction "2_2") (pintype "input"))
    )
    (net (code "307") (name "TELEM2_RTS") (class "Default")
      (node (ref "CN17") (pin "5") (pinfunction "5_5") (pintype "input"))
      (node (ref "D26") (pin "5") (pinfunction "I/O_5") (pintype "unspecified"))
      (node (ref "D26") (pin "6") (pinfunction "NC_6") (pintype "unspecified"))
      (node (ref "H24") (pin "5") (pinfunction "5_5") (pintype "input"))
      (node (ref "R96") (pin "2") (pinfunction "2_2") (pintype "input"))
    )
    (net (code "308") (name "TELEM2_RX") (class "Default")
      (node (ref "CN17") (pin "3") (pinfunction "3_3") (pintype "input"))
      (node (ref "D26") (pin "2") (pinfunction "I/O_2") (pintype "unspecified"))
      (node (ref "D26") (pin "9") (pinfunction "NC_9") (pintype "unspecified"))
      (node (ref "H24") (pin "3") (pinfunction "3_3") (pintype "input"))
      (node (ref "R122") (pin "2") (pinfunction "2_2") (pintype "input"))
    )
    (net (code "309") (name "TELEM2_TX") (class "Default")
      (node (ref "CN17") (pin "2") (pinfunction "2_2") (pintype "input"))
      (node (ref "D26") (pin "1") (pinfunction "I/O_1") (pintype "unspecified"))
      (node (ref "D26") (pin "10") (pinfunction "NC_10") (pintype "unspecified"))
      (node (ref "H24") (pin "2") (pinfunction "2_2") (pintype "input"))
      (node (ref "R121") (pin "2") (pinfunction "2_2") (pintype "input"))
    )
    (net (code "310") (name "TELEM3_5V") (class "Default")
      (node (ref "C140") (pin "3") (pinfunction "OUT_3") (pintype "unspecified"))
      (node (ref "CN18") (pin "1") (pinfunction "1_1") (pintype "input"))
      (node (ref "D27") (pin "2") (pinfunction "2_2") (pintype "input"))
      (node (ref "H25") (pin "1") (pinfunction "1_1") (pintype "input"))
    )
    (net (code "311") (name "TELEM3_CTS") (class "Default")
      (node (ref "CN18") (pin "4") (pinfunction "4_4") (pintype "input"))
      (node (ref "D28") (pin "4") (pinfunction "I/O_4") (pintype "unspecified"))
      (node (ref "D28") (pin "7") (pinfunction "NC_7") (pintype "unspecified"))
      (node (ref "H25") (pin "4") (pinfunction "4_4") (pintype "input"))
      (node (ref "R99") (pin "2") (pinfunction "2_2") (pintype "input"))
    )
    (net (code "312") (name "TELEM3_RTS") (class "Default")
      (node (ref "CN18") (pin "5") (pinfunction "5_5") (pintype "input"))
      (node (ref "D28") (pin "5") (pinfunction "I/O_5") (pintype "unspecified"))
      (node (ref "D28") (pin "6") (pinfunction "NC_6") (pintype "unspecified"))
      (node (ref "H25") (pin "5") (pinfunction "5_5") (pintype "input"))
      (node (ref "R100") (pin "2") (pinfunction "2_2") (pintype "input"))
    )
    (net (code "313") (name "TELEM3_RX") (class "Default")
      (node (ref "CN18") (pin "3") (pinfunction "3_3") (pintype "input"))
      (node (ref "D28") (pin "2") (pinfunction "I/O_2") (pintype "unspecified"))
      (node (ref "D28") (pin "9") (pinfunction "NC_9") (pintype "unspecified"))
      (node (ref "H25") (pin "3") (pinfunction "3_3") (pintype "input"))
      (node (ref "R98") (pin "2") (pinfunction "2_2") (pintype "input"))
    )
    (net (code "314") (name "TELEM3_TX") (class "Default")
      (node (ref "CN18") (pin "2") (pinfunction "2_2") (pintype "input"))
      (node (ref "D28") (pin "1") (pinfunction "I/O_1") (pintype "unspecified"))
      (node (ref "D28") (pin "10") (pinfunction "NC_10") (pintype "unspecified"))
      (node (ref "H25") (pin "2") (pinfunction "2_2") (pintype "input"))
      (node (ref "R97") (pin "2") (pinfunction "2_2") (pintype "input"))
    )
    (net (code "315") (name "TRACECLK") (class "Default")
      (node (ref "U28") (pin "A2") (pinfunction "PE2_A2") (pintype "unspecified"))
    )
    (net (code "316") (name "UART4_RX") (class "Default")
      (node (ref "R144") (pin "1") (pinfunction "1_1") (pintype "input"))
      (node (ref "U28") (pin "E13") (pinfunction "PH14_E13") (pintype "unspecified"))
    )
    (net (code "317") (name "UART4_TX") (class "Default")
      (node (ref "R143") (pin "1") (pinfunction "1_1") (pintype "input"))
      (node (ref "U28") (pin "E12") (pinfunction "PH13_E12") (pintype "unspecified"))
    )
    (net (code "318") (name "UART5_CTS_TELEM2") (class "Default")
      (node (ref "R123") (pin "1") (pinfunction "1_1") (pintype "input"))
      (node (ref "U28") (pin "F14") (pinfunction "PC9_F14") (pintype "unspecified"))
    )
    (net (code "319") (name "UART5_RTS_TELEM2") (class "Default")
      (node (ref "R96") (pin "1") (pinfunction "1_1") (pintype "input"))
      (node (ref "U28") (pin "G14") (pinfunction "PC8_G14") (pintype "unspecified"))
    )
    (net (code "320") (name "UART5_RX_TELEM2") (class "Default")
      (node (ref "R122") (pin "1") (pinfunction "1_1") (pintype "input"))
      (node (ref "U28") (pin "D12") (pinfunction "PD2_D12") (pintype "unspecified"))
    )
    (net (code "321") (name "UART5_TX_TELEM2") (class "Default")
      (node (ref "R121") (pin "1") (pinfunction "1_1") (pintype "input"))
      (node (ref "U28") (pin "A12") (pinfunction "PC12_A12") (pintype "unspecified"))
    )
    (net (code "322") (name "UART7_CTS_TELEM1") (class "Default")
      (node (ref "R62") (pin "1") (pinfunction "1_1") (pintype "input"))
      (node (ref "U28") (pin "R9") (pinfunction "PE10_R9") (pintype "unspecified"))
    )
    (net (code "323") (name "UART7_RTS_TELEM1") (class "Default")
      (node (ref "R63") (pin "1") (pinfunction "1_1") (pintype "input"))
      (node (ref "U28") (pin "L3") (pinfunction "PF8_L3") (pintype "unspecified"))
    )
    (net (code "324") (name "UART7_RX_TELEM1") (class "Default")
      (node (ref "R61") (pin "1") (pinfunction "1_1") (pintype "input"))
      (node (ref "U28") (pin "K2") (pinfunction "PF6_K2") (pintype "unspecified"))
    )
    (net (code "325") (name "UART7_TX_TELEM1") (class "Default")
      (node (ref "R120") (pin "1") (pinfunction "1_1") (pintype "input"))
      (node (ref "U28") (pin "P8") (pinfunction "PE8_P8") (pintype "unspecified"))
    )
    (net (code "326") (name "UART8_RX_GPS2") (class "Default")
      (node (ref "R132") (pin "1") (pinfunction "1_1") (pintype "input"))
      (node (ref "U28") (pin "A4") (pinfunction "PE0_A4") (pintype "unspecified"))
    )
    (net (code "327") (name "UART8_TX_GPS2") (class "Default")
      (node (ref "R131") (pin "1") (pinfunction "1_1") (pintype "input"))
      (node (ref "U28") (pin "A3") (pinfunction "PE1_A3") (pintype "unspecified"))
    )
    (net (code "328") (name "UART_I2C_EXT2_5V") (class "Default")
      (node (ref "C148") (pin "3") (pinfunction "OUT_3") (pintype "unspecified"))
      (node (ref "CN19") (pin "1") (pinfunction "1_1") (pintype "unspecified"))
      (node (ref "D31") (pin "2") (pinfunction "2_2") (pintype "input"))
      (node (ref "H30") (pin "1") (pinfunction "1_1") (pintype "unspecified"))
    )
    (net (code "329") (name "UART_I2C_EXT2_I2C_SCL") (class "Default")
      (node (ref "CN19") (pin "4") (pinfunction "4_4") (pintype "unspecified"))
      (node (ref "D32") (pin "4") (pinfunction "I/O_4") (pintype "unspecified"))
      (node (ref "D32") (pin "7") (pinfunction "NC_7") (pintype "unspecified"))
      (node (ref "H30") (pin "4") (pinfunction "4_4") (pintype "unspecified"))
      (node (ref "R145") (pin "2") (pinfunction "2_2") (pintype "input"))
    )
    (net (code "330") (name "UART_I2C_EXT2_I2C_SDA") (class "Default")
      (node (ref "CN19") (pin "5") (pinfunction "5_5") (pintype "unspecified"))
      (node (ref "D32") (pin "5") (pinfunction "I/O_5") (pintype "unspecified"))
      (node (ref "D32") (pin "6") (pinfunction "NC_6") (pintype "unspecified"))
      (node (ref "H30") (pin "5") (pinfunction "5_5") (pintype "unspecified"))
      (node (ref "R146") (pin "2") (pinfunction "2_2") (pintype "input"))
    )
    (net (code "331") (name "UART_I2C_EXT2_NFC_GPIO") (class "Default")
      (node (ref "CN19") (pin "6") (pinfunction "6_6") (pintype "unspecified"))
      (node (ref "D33") (pin "2") (pinfunction "2_2") (pintype "input"))
      (node (ref "H30") (pin "6") (pinfunction "6_6") (pintype "unspecified"))
      (node (ref "R147") (pin "2") (pinfunction "2_2") (pintype "input"))
    )
    (net (code "332") (name "UART_I2C_EXT2_UART_RX") (class "Default")
      (node (ref "CN19") (pin "3") (pinfunction "3_3") (pintype "unspecified"))
      (node (ref "D32") (pin "2") (pinfunction "I/O_2") (pintype "unspecified"))
      (node (ref "D32") (pin "9") (pinfunction "NC_9") (pintype "unspecified"))
      (node (ref "H30") (pin "3") (pinfunction "3_3") (pintype "unspecified"))
      (node (ref "R144") (pin "2") (pinfunction "2_2") (pintype "input"))
    )
    (net (code "333") (name "UART_I2C_EXT2_UART_TX") (class "Default")
      (node (ref "CN19") (pin "2") (pinfunction "2_2") (pintype "unspecified"))
      (node (ref "D32") (pin "1") (pinfunction "I/O_1") (pintype "unspecified"))
      (node (ref "D32") (pin "10") (pinfunction "NC_10") (pintype "unspecified"))
      (node (ref "H30") (pin "2") (pinfunction "2_2") (pintype "unspecified"))
      (node (ref "R143") (pin "2") (pinfunction "2_2") (pintype "input"))
    )
    (net (code "334") (name "USART1_RX_GPS1") (class "Default")
      (node (ref "R125") (pin "1") (pinfunction "1_1") (pintype "input"))
      (node (ref "U28") (pin "B5") (pinfunction "PB7_B5") (pintype "unspecified"))
    )
    (net (code "335") (name "USART1_TX_GPS1") (class "Default")
      (node (ref "R124") (pin "1") (pinfunction "1_1") (pintype "input"))
      (node (ref "U28") (pin "B6") (pinfunction "PB6_B6") (pintype "unspecified"))
    )
    (net (code "336") (name "USART2_CTS_TELEM3") (class "Default")
      (node (ref "R99") (pin "1") (pinfunction "1_1") (pintype "input"))
      (node (ref "U28") (pin "D11") (pinfunction "PD3_D11") (pintype "unspecified"))
    )
    (net (code "337") (name "USART2_RTS_TELEM3") (class "Default")
      (node (ref "R100") (pin "1") (pinfunction "1_1") (pintype "input"))
      (node (ref "U28") (pin "D10") (pinfunction "PD4_D10") (pintype "unspecified"))
    )
    (net (code "338") (name "USART2_RX_TELEM3") (class "Default")
      (node (ref "R98") (pin "1") (pinfunction "1_1") (pintype "input"))
      (node (ref "U28") (pin "R2") (pinfunction "PA3_R2") (pintype "unspecified"))
    )
    (net (code "339") (name "USART2_TX_TELEM3") (class "Default")
      (node (ref "R97") (pin "1") (pinfunction "1_1") (pintype "input"))
      (node (ref "U28") (pin "C11") (pinfunction "PD5_C11") (pintype "unspecified"))
    )
    (net (code "340") (name "USART3_RX_DEBUG") (class "Default")
      (node (ref "D3") (pin "2") (pinfunction "A_2") (pintype "input"))
      (node (ref "U28") (pin "P14") (pinfunction "PD9_P14") (pintype "unspecified"))
    )
    (net (code "341") (name "USART3_TX_DEBUG") (class "Default")
      (node (ref "D2") (pin "1") (pinfunction "I/O_1") (pintype "unspecified"))
      (node (ref "D2") (pin "10") (pinfunction "NC_10") (pintype "unspecified"))
      (node (ref "H1") (pin "2") (pinfunction "2_2") (pintype "input"))
      (node (ref "U28") (pin "P15") (pinfunction "PD8_P15") (pintype "unspecified"))
      (node (ref "U30") (pin "2") (pinfunction "2_2") (pintype "unspecified"))
    )
    (net (code "342") (name "USART6_RX_FROM_IO__RC_INPUT") (class "Default")
      (node (ref "R178") (pin "1") (pinfunction "1_1") (pintype "input"))
      (node (ref "U28") (pin "G15") (pinfunction "PC7_G15") (pintype "unspecified"))
    )
    (net (code "343") (name "USART6_TX_TO_IO__NC") (class "Default")
      (node (ref "R179") (pin "1") (pinfunction "1_1") (pintype "input"))
      (node (ref "U28") (pin "H15") (pinfunction "PC6_H15") (pintype "unspecified"))
    )
    (net (code "344") (name "USB_D_N") (class "Default")
      (node (ref "R48") (pin "2") (pinfunction "2_2") (pintype "input"))
      (node (ref "U28") (pin "C15") (pinfunction "PA11_C15") (pintype "unspecified"))
    )
    (net (code "345") (name "USB_D_P") (class "Default")
      (node (ref "R47") (pin "2") (pinfunction "2_2") (pintype "input"))
      (node (ref "U28") (pin "B15") (pinfunction "PA12_B15") (pintype "unspecified"))
    )
    (net (code "346") (name "VBAT") (class "Default")
      (node (ref "C23") (pin "1") (pinfunction "1_1") (pintype "input"))
      (node (ref "R177") (pin "2") (pinfunction "2_2") (pintype "input"))
      (node (ref "U28") (pin "C1") (pinfunction "VBAT_C1") (pintype "unspecified"))
      (node (ref "U52") (pin "1") (pinfunction "+_1") (pintype "unspecified"))
      (node (ref "U53") (pin "1") (pinfunction "VBAT_1") (pintype "unspecified"))
    )
    (net (code "347") (name "VBUS") (class "Default")
      (node (ref "CN13") (pin "1") (pinfunction "1_1") (pintype "unspecified"))
      (node (ref "Q3") (pin "7") (pinfunction "D1_7") (pintype "unspecified"))
      (node (ref "Q3") (pin "8") (pinfunction "D1_8") (pintype "unspecified"))
      (node (ref "U29") (pin "5") (pinfunction "VBUS_5") (pintype "unspecified"))
      (node (ref "U9") (pin "A4B9") (pinfunction "VBUS_A4B9") (pintype "unspecified"))
      (node (ref "U9") (pin "B4A9") (pinfunction "VBUS_B4A9") (pintype "unspecified"))
    )
    (net (code "348") (name "VBUS_SENSE") (class "Default")
      (node (ref "U28") (pin "E15") (pinfunction "PA9_E15") (pintype "unspecified"))
    )
    (net (code "349") (name "VCAP") (class "Default")
      (node (ref "C43") (pin "1") (pinfunction "1_1") (pintype "input"))
      (node (ref "C44") (pin "1") (pinfunction "1_1") (pintype "input"))
    )
    (net (code "350") (name "VDD5V_BRICK1") (class "Default")
      (node (ref "C45") (pin "1") (pinfunction "1_1") (pintype "input"))
      (node (ref "C46") (pin "1") (pinfunction "1_1") (pintype "input"))
      (node (ref "Q1") (pin "7") (pinfunction "D1_7") (pintype "unspecified"))
      (node (ref "Q1") (pin "8") (pinfunction "D1_8") (pintype "unspecified"))
      (node (ref "R35") (pin "2") (pinfunction "2_2") (pintype "input"))
      (node (ref "U17") (pin "1") (pinfunction "1_1") (pintype "unspecified"))
      (node (ref "U17") (pin "2") (pinfunction "2_2") (pintype "unspecified"))
      (node (ref "U18") (pin "21") (pinfunction "V1_21") (pintype "unspecified"))
    )
    (net (code "351") (name "VDD5V_BRICK2") (class "Default")
      (node (ref "C53") (pin "1") (pinfunction "1_1") (pintype "input"))
      (node (ref "C54") (pin "1") (pinfunction "1_1") (pintype "input"))
      (node (ref "Q2") (pin "7") (pinfunction "D1_7") (pintype "unspecified"))
      (node (ref "Q2") (pin "8") (pinfunction "D1_8") (pintype "unspecified"))
      (node (ref "R38") (pin "2") (pinfunction "2_2") (pintype "input"))
      (node (ref "U18") (pin "20") (pinfunction "V2_20") (pintype "unspecified"))
      (node (ref "U19") (pin "1") (pinfunction "1_1") (pintype "unspecified"))
      (node (ref "U19") (pin "2") (pinfunction "2_2") (pintype "unspecified"))
    )
    (net (code "352") (name "VDDA") (class "Default")
      (node (ref "C24") (pin "1") (pinfunction "1_1") (pintype "input"))
      (node (ref "C25") (pin "1") (pinfunction "1_1") (pintype "input"))
      (node (ref "L3") (pin "2") (pinfunction "2_2") (pintype "unspecified"))
      (node (ref "U28") (pin "R1") (pinfunction "VDDA_R1") (pintype "unspecified"))
    )
    (net (code "353") (name "VDD_3V3_SD_CARD_EN") (class "Default")
      (node (ref "U16") (pin "B1") (pinfunction "EN_B1") (pintype "unspecified"))
      (node (ref "U28") (pin "D1") (pinfunction "PC13_D1") (pintype "unspecified"))
    )
    (net (code "354") (name "VDD_3V3_SENSORS1") (class "Default")
      (node (ref "C185") (pin "1") (pinfunction "1_1") (pintype "input"))
      (node (ref "C92") (pin "2") (pinfunction "2_2") (pintype "input"))
      (node (ref "C94") (pin "1") (pinfunction "1_1") (pintype "input"))
      (node (ref "R166") (pin "2") (pinfunction "2_2") (pintype "input"))
      (node (ref "U31") (pin "13") (pinfunction "VDD_13") (pintype "unspecified"))
      (node (ref "U31") (pin "8") (pinfunction "VDDIO_8") (pintype "unspecified"))
      (node (ref "U48") (pin "5") (pinfunction "OUT_5") (pintype "unspecified"))
    )
    (net (code "355") (name "VDD_3V3_SENSORS1_EN") (class "Default")
      (node (ref "R165") (pin "2") (pinfunction "2_2") (pintype "input"))
      (node (ref "U28") (pin "E4") (pinfunction "PI11_E4") (pintype "unspecified"))
      (node (ref "U48") (pin "3") (pinfunction "EN_3") (pintype "unspecified"))
    )
    (net (code "356") (name "VDD_3V3_SENSORS2") (class "Default")
      (node (ref "C100") (pin "1") (pinfunction "1_1") (pintype "input"))
      (node (ref "C101") (pin "1") (pinfunction "1_1") (pintype "input"))
      (node (ref "C191") (pin "1") (pinfunction "1_1") (pintype "input"))
      (node (ref "C36") (pin "1") (pinfunction "1_1") (pintype "input"))
      (node (ref "C99") (pin "1") (pinfunction "1_1") (pintype "input"))
      (node (ref "R169") (pin "2") (pinfunction "2_2") (pintype "input"))
      (node (ref "U13") (pin "1") (pinfunction "VDDIO_1") (pintype "unspecified"))
      (node (ref "U13") (pin "6") (pinfunction "CSB_6") (pintype "unspecified"))
      (node (ref "U34") (pin "5") (pinfunction "VDDIO_5") (pintype "unspecified"))
      (node (ref "U34") (pin "8") (pinfunction "VDD_8") (pintype "unspecified"))
      (node (ref "U49") (pin "5") (pinfunction "OUT_5") (pintype "unspecified"))
    )
    (net (code "357") (name "VDD_3V3_SENSORS2_EN") (class "Default")
      (node (ref "R168") (pin "2") (pinfunction "2_2") (pintype "input"))
      (node (ref "U28") (pin "J3") (pinfunction "PF4_J3") (pintype "unspecified"))
      (node (ref "U49") (pin "3") (pinfunction "EN_3") (pintype "unspecified"))
    )
    (net (code "358") (name "VDD_3V3_SENSORS3") (class "Default")
      (node (ref "C197") (pin "1") (pinfunction "1_1") (pintype "input"))
      (node (ref "C33") (pin "1") (pinfunction "1_1") (pintype "input"))
      (node (ref "C34") (pin "1") (pinfunction "1_1") (pintype "input"))
      (node (ref "R172") (pin "2") (pinfunction "2_2") (pintype "input"))
      (node (ref "U12") (pin "11") (pinfunction "VDDIO_11") (pintype "unspecified"))
      (node (ref "U12") (pin "3") (pinfunction "VDD_3") (pintype "unspecified"))
      (node (ref "U50") (pin "5") (pinfunction "OUT_5") (pintype "unspecified"))
    )
    (net (code "359") (name "VDD_3V3_SENSORS3_EN") (class "Default")
      (node (ref "R171") (pin "2") (pinfunction "2_2") (pintype "input"))
      (node (ref "U28") (pin "R8") (pinfunction "PE7_R8") (pintype "unspecified"))
      (node (ref "U50") (pin "3") (pinfunction "EN_3") (pintype "unspecified"))
    )
    (net (code "360") (name "VDD_3V3_SENSORS4") (class "Default")
      (node (ref "C102") (pin "1") (pinfunction "1_1") (pintype "input"))
      (node (ref "C203") (pin "1") (pinfunction "1_1") (pintype "input"))
      (node (ref "C37") (pin "1") (pinfunction "1_1") (pintype "input"))
      (node (ref "C38") (pin "1") (pinfunction "1_1") (pintype "input"))
      (node (ref "C98") (pin "1") (pinfunction "1_1") (pintype "input"))
      (node (ref "R175") (pin "2") (pinfunction "2_2") (pintype "input"))
      (node (ref "U14") (pin "B2") (pinfunction "VDDIO_B2") (pintype "unspecified"))
      (node (ref "U14") (pin "E5") (pinfunction "VDD_E5") (pintype "unspecified"))
      (node (ref "U33") (pin "1") (pinfunction "VDDIO_1") (pintype "unspecified"))
      (node (ref "U33") (pin "5") (pinfunction "SDO_5") (pintype "unspecified"))
      (node (ref "U33") (pin "6") (pinfunction "CSB_6") (pintype "unspecified"))
      (node (ref "U35") (pin "8") (pinfunction "VCC_8") (pintype "unspecified"))
      (node (ref "U51") (pin "5") (pinfunction "OUT_5") (pintype "unspecified"))
    )
    (net (code "361") (name "VDD_3V3_SENSORS4_EN") (class "Default")
      (node (ref "R174") (pin "2") (pinfunction "2_2") (pintype "input"))
      (node (ref "U28") (pin "H14") (pinfunction "PG8_H14") (pintype "unspecified"))
      (node (ref "U51") (pin "3") (pinfunction "EN_3") (pintype "unspecified"))
    )
    (net (code "362") (name "VDD_3V3_SPEKTRUM") (class "Default")
      (node (ref "C153") (pin "1") (pinfunction "1_1") (pintype "input"))
      (node (ref "C154") (pin "1") (pinfunction "1_1") (pintype "input"))
      (node (ref "C212") (pin "1") (pinfunction "IN_1") (pintype "unspecified"))
      (node (ref "C213") (pin "1") (pinfunction "1_1") (pintype "input"))
      (node (ref "U42") (pin "8") (pinfunction "VOUT1_8") (pintype "unspecified"))
    )
    (net (code "363") (name "VDD_3V3_SPEKTRUM_EN") (class "Default")
      (node (ref "R148") (pin "1") (pinfunction "1_1") (pintype "input"))
      (node (ref "R149") (pin "2") (pinfunction "2_2") (pintype "input"))
      (node (ref "U42") (pin "5") (pinfunction "EN1_5") (pintype "unspecified"))
      (node (ref "U53") (pin "2") (pinfunction "PC13-TAMPER-RTC_2") (pintype "unspecified"))
    )
    (net (code "364") (name "VDD_3V3_SPEKTRUM_POWER_EN") (class "Default")
      (node (ref "R148") (pin "2") (pinfunction "2_2") (pintype "input"))
      (node (ref "U28") (pin "F4") (pinfunction "PH2_F4") (pintype "unspecified"))
    )
    (net (code "365") (name "VDD_5V_HIPOWER") (class "Default")
      (node (ref "C137") (pin "1") (pinfunction "IN_1") (pintype "unspecified"))
      (node (ref "C146") (pin "1") (pinfunction "IN_1") (pintype "unspecified"))
      (node (ref "C147") (pin "1") (pinfunction "1_1") (pintype "input"))
      (node (ref "C67") (pin "1") (pinfunction "1_1") (pintype "input"))
      (node (ref "C68") (pin "1") (pinfunction "1_1") (pintype "input"))
      (node (ref "C79") (pin "1") (pinfunction "1_1") (pintype "input"))
      (node (ref "U23") (pin "8") (pinfunction "OUT_8") (pintype "unspecified"))
    )
    (net (code "366") (name "VDD_5V_HIPOWER_NEN") (class "Default")
      (node (ref "R55") (pin "1") (pinfunction "1_1") (pintype "input"))
      (node (ref "U28") (pin "B10") (pinfunction "PG10_B10") (pintype "unspecified"))
    )
    (net (code "367") (name "VDD_5V_HIPOWER_NOC") (class "Default")
      (node (ref "R54") (pin "1") (pinfunction "1_1") (pintype "input"))
      (node (ref "R57") (pin "1") (pinfunction "1_1") (pintype "input"))
      (node (ref "U28") (pin "N6") (pinfunction "PF13_N6") (pintype "unspecified"))
    )
    (net (code "368") (name "VDD_5V_IN") (class "Default")
      (node (ref "C158") (pin "1") (pinfunction "IN_1") (pintype "unspecified"))
      (node (ref "C180") (pin "1") (pinfunction "IN_1") (pintype "unspecified"))
      (node (ref "C183") (pin "1") (pinfunction "1_1") (pintype "input"))
      (node (ref "C184") (pin "1") (pinfunction "1_1") (pintype "input"))
      (node (ref "C186") (pin "1") (pinfunction "IN_1") (pintype "unspecified"))
      (node (ref "C189") (pin "1") (pinfunction "1_1") (pintype "input"))
      (node (ref "C190") (pin "1") (pinfunction "1_1") (pintype "input"))
      (node (ref "C192") (pin "1") (pinfunction "IN_1") (pintype "unspecified"))
      (node (ref "C195") (pin "1") (pinfunction "1_1") (pintype "input"))
      (node (ref "C196") (pin "1") (pinfunction "1_1") (pintype "input"))
      (node (ref "C198") (pin "1") (pinfunction "IN_1") (pintype "unspecified"))
      (node (ref "C201") (pin "1") (pinfunction "1_1") (pintype "input"))
      (node (ref "C202") (pin "1") (pinfunction "1_1") (pintype "input"))
      (node (ref "C47") (pin "1") (pinfunction "1_1") (pintype "input"))
      (node (ref "C48") (pin "1") (pinfunction "1_1") (pintype "input"))
      (node (ref "C59") (pin "2") (pinfunction "2_2") (pintype "input"))
      (node (ref "C66") (pin "2") (pinfunction "2_2") (pintype "input"))
      (node (ref "C78") (pin "1") (pinfunction "IN_1") (pintype "unspecified"))
      (node (ref "C86") (pin "1") (pinfunction "1_1") (pintype "input"))
      (node (ref "H19") (pin "1") (pinfunction "1_1") (pintype "input"))
      (node (ref "LED10") (pin "1") (pinfunction "A_1") (pintype "input"))
      (node (ref "LED11") (pin "2") (pinfunction "A_2") (pintype "input"))
      (node (ref "LED7") (pin "2") (pinfunction "A_2") (pintype "input"))
      (node (ref "Q1") (pin "5") (pinfunction "D2_5") (pintype "unspecified"))
      (node (ref "Q1") (pin "6") (pinfunction "D2_6") (pintype "unspecified"))
      (node (ref "Q2") (pin "5") (pinfunction "D2_5") (pintype "unspecified"))
      (node (ref "Q2") (pin "6") (pinfunction "D2_6") (pintype "unspecified"))
      (node (ref "Q3") (pin "5") (pinfunction "D2_5") (pintype "unspecified"))
      (node (ref "Q3") (pin "6") (pinfunction "D2_6") (pintype "unspecified"))
      (node (ref "R88") (pin "2") (pinfunction "2_2") (pintype "input"))
      (node (ref "U18") (pin "12") (pinfunction "VOUT_12") (pintype "unspecified"))
      (node (ref "U20") (pin "1") (pinfunction "IN_1") (pintype "unspecified"))
      (node (ref "U23") (pin "1") (pinfunction "IN_1") (pintype "unspecified"))
      (node (ref "U26") (pin "5") (pinfunction "EN_5") (pintype "unspecified"))
      (node (ref "U26") (pin "6") (pinfunction "VIN_6") (pintype "unspecified"))
    )
    (net (code "369") (name "VDD_5V_PERIPH") (class "Default")
      (node (ref "C138") (pin "1") (pinfunction "IN_1") (pintype "unspecified"))
      (node (ref "C139") (pin "1") (pinfunction "1_1") (pintype "input"))
      (node (ref "C140") (pin "1") (pinfunction "IN_1") (pintype "unspecified"))
      (node (ref "C141") (pin "1") (pinfunction "1_1") (pintype "input"))
      (node (ref "C142") (pin "1") (pinfunction "IN_1") (pintype "unspecified"))
      (node (ref "C143") (pin "1") (pinfunction "1_1") (pintype "input"))
      (node (ref "C148") (pin "1") (pinfunction "IN_1") (pintype "unspecified"))
      (node (ref "C149") (pin "1") (pinfunction "1_1") (pintype "input"))
      (node (ref "C60") (pin "1") (pinfunction "1_1") (pintype "input"))
      (node (ref "C61") (pin "1") (pinfunction "1_1") (pintype "input"))
      (node (ref "CN11") (pin "1") (pinfunction "1_1") (pintype "unspecified"))
      (node (ref "CN14") (pin "1") (pinfunction "1_1") (pintype "unspecified"))
      (node (ref "H20") (pin "1") (pinfunction "1_1") (pintype "input"))
      (node (ref "U20") (pin "8") (pinfunction "OUT_8") (pintype "unspecified"))
    )
    (net (code "370") (name "VDD_5V_PERIPH_NEN") (class "Default")
      (node (ref "R50") (pin "1") (pinfunction "1_1") (pintype "input"))
      (node (ref "U28") (pin "K14") (pinfunction "PG4_K14") (pintype "unspecified"))
    )
    (net (code "371") (name "VDD_5V_PERIPH_NOC") (class "Default")
      (node (ref "R49") (pin "1") (pinfunction "1_1") (pintype "input"))
      (node (ref "R52") (pin "1") (pinfunction "1_1") (pintype "input"))
      (node (ref "U28") (pin "R11") (pinfunction "PE15_R11") (pintype "unspecified"))
    )
    (net (code "372") (name "VDD_BUCK_OUT") (class "Default")
      (node (ref "C87") (pin "1") (pinfunction "1_1") (pintype "input"))
      (node (ref "C89") (pin "1") (pinfunction "1_1") (pintype "input"))
      (node (ref "L1") (pin "2") (pinfunction "2_2") (pintype "input"))
      (node (ref "R74") (pin "2") (pinfunction "2_2") (pintype "input"))
      (node (ref "R76") (pin "2") (pinfunction "2_2") (pintype "input"))
      (node (ref "U26") (pin "3") (pinfunction "VOS_3") (pintype "unspecified"))
      (node (ref "U27") (pin "10") (pinfunction "IN_10") (pintype "unspecified"))
      (node (ref "U27") (pin "6") (pinfunction "SS_CTRL_6") (pintype "unspecified"))
      (node (ref "U27") (pin "9") (pinfunction "IN_9") (pintype "unspecified"))
    )
    (net (code "373") (name "VDD_SERVO") (class "Default")
      (node (ref "H29") (pin "1") (pinfunction "1_1") (pintype "unspecified"))
      (node (ref "H29") (pin "2") (pinfunction "2_2") (pintype "unspecified"))
      (node (ref "H29") (pin "3") (pinfunction "3_3") (pintype "unspecified"))
      (node (ref "H29") (pin "4") (pinfunction "4_4") (pintype "unspecified"))
      (node (ref "H29") (pin "5") (pinfunction "5_5") (pintype "unspecified"))
      (node (ref "H29") (pin "6") (pinfunction "6_6") (pintype "unspecified"))
      (node (ref "H29") (pin "7") (pinfunction "7_7") (pintype "unspecified"))
      (node (ref "H29") (pin "8") (pinfunction "8_8") (pintype "unspecified"))
      (node (ref "H34") (pin "1") (pinfunction "1_1") (pintype "unspecified"))
      (node (ref "H34") (pin "2") (pinfunction "2_2") (pintype "unspecified"))
      (node (ref "H34") (pin "3") (pinfunction "3_3") (pintype "unspecified"))
      (node (ref "H34") (pin "4") (pinfunction "4_4") (pintype "unspecified"))
      (node (ref "H34") (pin "5") (pinfunction "5_5") (pintype "unspecified"))
      (node (ref "H34") (pin "6") (pinfunction "6_6") (pintype "unspecified"))
      (node (ref "H34") (pin "7") (pinfunction "7_7") (pintype "unspecified"))
      (node (ref "H34") (pin "8") (pinfunction "8_8") (pintype "unspecified"))
      (node (ref "R183") (pin "1") (pinfunction "1_1") (pintype "input"))
    )
    (net (code "374") (name "unconnected-(CN20-Pad3)") (class "Default")
      (node (ref "CN20") (pin "3") (pinfunction "3_3") (pintype "unspecified+no_connect"))
    )
    (net (code "375") (name "unconnected-(D36-I{slash}O-Pad5)") (class "Default")
      (node (ref "D36") (pin "5") (pinfunction "I/O_5") (pintype "unspecified+no_connect"))
    )
    (net (code "376") (name "unconnected-(D36-NC-Pad6)") (class "Default")
      (node (ref "D36") (pin "6") (pinfunction "NC_6") (pintype "unspecified+no_connect"))
    )
    (net (code "377") (name "unconnected-(D36-NC-Pad7)") (class "Default")
      (node (ref "D36") (pin "7") (pinfunction "NC_7") (pintype "unspecified+no_connect"))
    )
    (net (code "378") (name "unconnected-(H31-Pad3)") (class "Default")
      (node (ref "H31") (pin "3") (pinfunction "3_3") (pintype "unspecified+no_connect"))
    )
    (net (code "379") (name "unconnected-(OSC1-VCC-Pad4)") (class "Default")
      (node (ref "OSC1") (pin "4") (pinfunction "VCC_4") (pintype "unspecified"))
    )
    (net (code "380") (name "unconnected-(RJ1-Pad4)") (class "Default")
      (node (ref "RJ1") (pin "4") (pinfunction "4_4") (pintype "unspecified+no_connect"))
    )
    (net (code "381") (name "unconnected-(RJ1-Pad5)") (class "Default")
      (node (ref "RJ1") (pin "5") (pinfunction "5_5") (pintype "unspecified+no_connect"))
    )
    (net (code "382") (name "unconnected-(RJ1-Pad7)") (class "Default")
      (node (ref "RJ1") (pin "7") (pinfunction "7_7") (pintype "unspecified+no_connect"))
    )
    (net (code "383") (name "unconnected-(RJ1-Pad8)") (class "Default")
      (node (ref "RJ1") (pin "8") (pinfunction "8_8") (pintype "unspecified+no_connect"))
    )
    (net (code "384") (name "unconnected-(TF1-CD-Pad9)") (class "Default")
      (node (ref "TF1") (pin "9") (pinfunction "CD_9") (pintype "unspecified+no_connect"))
    )
    (net (code "385") (name "unconnected-(U9-SBU1-PadA8)") (class "Default")
      (node (ref "U9") (pin "A8") (pinfunction "SBU1_A8") (pintype "unspecified+no_connect"))
    )
    (net (code "386") (name "unconnected-(U9-SBU2-PadB8)") (class "Default")
      (node (ref "U9") (pin "B8") (pinfunction "SBU2_B8") (pintype "unspecified+no_connect"))
    )
    (net (code "387") (name "unconnected-(U18-CAS-Pad11)") (class "Default")
      (node (ref "U18") (pin "11") (pinfunction "CAS_11") (pintype "unspecified+no_connect"))
    )
    (net (code "388") (name "unconnected-(U18-EN-Pad22)") (class "Default")
      (node (ref "U18") (pin "22") (pinfunction "EN_22") (pintype "unspecified+no_connect"))
    )
    (net (code "389") (name "unconnected-(U18-SHDN#-Pad23)") (class "Default")
      (node (ref "U18") (pin "23") (pinfunction "SHDN#_23") (pintype "unspecified+no_connect"))
    )
    (net (code "390") (name "unconnected-(U20-NC-Pad3)") (class "Default")
      (node (ref "U20") (pin "3") (pinfunction "NC_3") (pintype "unspecified+no_connect"))
    )
    (net (code "391") (name "unconnected-(U23-NC-Pad3)") (class "Default")
      (node (ref "U23") (pin "3") (pinfunction "NC_3") (pintype "unspecified+no_connect"))
    )
    (net (code "392") (name "unconnected-(U28-VDD33USB-PadH13)") (class "Default")
      (node (ref "U28") (pin "H13") (pinfunction "VDD33USB_H13") (pintype "unspecified"))
    )
    (net (code "393") (name "unconnected-(U28-VREF+-PadP1)") (class "Default")
      (node (ref "U28") (pin "P1") (pinfunction "VREF+_P1") (pintype "unspecified"))
    )
    (net (code "394") (name "unconnected-(U28-VREF--PadN1)") (class "Default")
      (node (ref "U28") (pin "N1") (pinfunction "VREF-_N1") (pintype "unspecified"))
    )
    (net (code "395") (name "unconnected-(U31-AUX_CL-Pad7)") (class "Default")
      (node (ref "U31") (pin "7") (pinfunction "AUX_CL_7") (pintype "unspecified+no_connect"))
    )
    (net (code "396") (name "unconnected-(U31-AUX_DA-Pad21)") (class "Default")
      (node (ref "U31") (pin "21") (pinfunction "AUX_DA_21") (pintype "unspecified+no_connect"))
    )
    (net (code "397") (name "unconnected-(U31-INT2-Pad19)") (class "Default")
      (node (ref "U31") (pin "19") (pinfunction "INT2_19") (pintype "unspecified+no_connect"))
    )
    (net (code "398") (name "unconnected-(U31-NC-Pad1)") (class "Default")
      (node (ref "U31") (pin "1") (pinfunction "NC_1") (pintype "unspecified+no_connect"))
    )
    (net (code "399") (name "unconnected-(U31-NC-Pad2)") (class "Default")
      (node (ref "U31") (pin "2") (pinfunction "NC_2") (pintype "unspecified+no_connect"))
    )
    (net (code "400") (name "unconnected-(U31-NC-Pad3)") (class "Default")
      (node (ref "U31") (pin "3") (pinfunction "NC_3") (pintype "unspecified+no_connect"))
    )
    (net (code "401") (name "unconnected-(U31-NC-Pad4)") (class "Default")
      (node (ref "U31") (pin "4") (pinfunction "NC_4") (pintype "unspecified+no_connect"))
    )
    (net (code "402") (name "unconnected-(U31-NC-Pad5)") (class "Default")
      (node (ref "U31") (pin "5") (pinfunction "NC_5") (pintype "unspecified+no_connect"))
    )
    (net (code "403") (name "unconnected-(U31-NC-Pad6)") (class "Default")
      (node (ref "U31") (pin "6") (pinfunction "NC_6") (pintype "unspecified+no_connect"))
    )
    (net (code "404") (name "unconnected-(U31-NC-Pad14)") (class "Default")
      (node (ref "U31") (pin "14") (pinfunction "NC_14") (pintype "unspecified+no_connect"))
    )
    (net (code "405") (name "unconnected-(U31-NC-Pad15)") (class "Default")
      (node (ref "U31") (pin "15") (pinfunction "NC_15") (pintype "unspecified+no_connect"))
    )
    (net (code "406") (name "unconnected-(U31-NC-Pad16)") (class "Default")
      (node (ref "U31") (pin "16") (pinfunction "NC_16") (pintype "unspecified+no_connect"))
    )
    (net (code "407") (name "unconnected-(U31-NC-Pad17)") (class "Default")
      (node (ref "U31") (pin "17") (pinfunction "NC_17") (pintype "unspecified+no_connect"))
    )
    (net (code "408") (name "unconnected-(U33-INT-Pad7)") (class "Default")
      (node (ref "U33") (pin "7") (pinfunction "INT_7") (pintype "unspecified+no_connect"))
    )
    (net (code "409") (name "unconnected-(U34-RESV-Pad2)") (class "Default")
      (node (ref "U34") (pin "2") (pinfunction "RESV_2") (pintype "unspecified+no_connect"))
    )
    (net (code "410") (name "unconnected-(U34-RESV-Pad3)") (class "Default")
      (node (ref "U34") (pin "3") (pinfunction "RESV_3") (pintype "unspecified+no_connect"))
    )
    (net (code "411") (name "unconnected-(U34-RESV-Pad7)") (class "Default")
      (node (ref "U34") (pin "7") (pinfunction "RESV_7") (pintype "unspecified+no_connect"))
    )
    (net (code "412") (name "unconnected-(U34-RESV-Pad10)") (class "Default")
      (node (ref "U34") (pin "10") (pinfunction "RESV_10") (pintype "unspecified+no_connect"))
    )
    (net (code "413") (name "unconnected-(U34-RESV-Pad11)") (class "Default")
      (node (ref "U34") (pin "11") (pinfunction "RESV_11") (pintype "unspecified+no_connect"))
    )
    (net (code "414") (name "unconnected-(U40-COL{slash}PHYAD0-Pad35)") (class "Default")
      (node (ref "U40") (pin "35") (pinfunction "COL/PHYAD0_35") (pintype "unspecified+no_connect"))
    )
    (net (code "415") (name "unconnected-(U40-LED_LINK{slash}AN0-Pad22)") (class "Default")
      (node (ref "U40") (pin "22") (pinfunction "LED_LINK/AN0_22") (pintype "unspecified+no_connect"))
    )
    (net (code "416") (name "unconnected-(U40-RESERVED-Pad8)") (class "Default")
      (node (ref "U40") (pin "8") (pinfunction "RESERVED_8") (pintype "unspecified+no_connect"))
    )
    (net (code "417") (name "unconnected-(U40-RESERVED-Pad9)") (class "Default")
      (node (ref "U40") (pin "9") (pinfunction "RESERVED_9") (pintype "unspecified+no_connect"))
    )
    (net (code "418") (name "unconnected-(U40-RESERVED-Pad10)") (class "Default")
      (node (ref "U40") (pin "10") (pinfunction "RESERVED_10") (pintype "unspecified+no_connect"))
    )
    (net (code "419") (name "unconnected-(U40-RXD_2{slash}PHYAD3-Pad38)") (class "Default")
      (node (ref "U40") (pin "38") (pinfunction "RXD_2/PHYAD3_38") (pintype "unspecified+no_connect"))
    )
    (net (code "420") (name "unconnected-(U40-RXD_3{slash}PHYAD4-Pad39)") (class "Default")
      (node (ref "U40") (pin "39") (pinfunction "RXD_3/PHYAD4_39") (pintype "unspecified+no_connect"))
    )
    (net (code "421") (name "unconnected-(U40-RX_CLK-Pad31)") (class "Default")
      (node (ref "U40") (pin "31") (pinfunction "RX_CLK_31") (pintype "unspecified+no_connect"))
    )
    (net (code "422") (name "unconnected-(U40-RX_ER{slash}MDIX_EN-Pad34)") (class "Default")
      (node (ref "U40") (pin "34") (pinfunction "RX_ER/MDIX_EN_34") (pintype "unspecified+no_connect"))
    )
    (net (code "423") (name "unconnected-(U40-TXD_2-Pad6)") (class "Default")
      (node (ref "U40") (pin "6") (pinfunction "TXD_2_6") (pintype "unspecified+no_connect"))
    )
    (net (code "424") (name "unconnected-(U40-TXD_3-Pad7)") (class "Default")
      (node (ref "U40") (pin "7") (pinfunction "TXD_3_7") (pintype "unspecified+no_connect"))
    )
    (net (code "425") (name "unconnected-(U40-TX_CLK-Pad2)") (class "Default")
      (node (ref "U40") (pin "2") (pinfunction "TX_CLK_2") (pintype "unspecified+no_connect"))
    )
    (net (code "426") (name "unconnected-(U40-X2-Pad27)") (class "Default")
      (node (ref "U40") (pin "27") (pinfunction "X2_27") (pintype "unspecified+no_connect"))
    )
    (net (code "427") (name "unconnected-(U43-VOUT1-Pad8)") (class "Default")
      (node (ref "U43") (pin "8") (pinfunction "VOUT1_8") (pintype "unspecified+no_connect"))
    )
    (net (code "428") (name "unconnected-(U48-N{slash}C-Pad4)") (class "Default")
      (node (ref "U48") (pin "4") (pinfunction "N/C_4") (pintype "unspecified+no_connect"))
    )
    (net (code "429") (name "unconnected-(U49-N{slash}C-Pad4)") (class "Default")
      (node (ref "U49") (pin "4") (pinfunction "N/C_4") (pintype "unspecified+no_connect"))
    )
    (net (code "430") (name "unconnected-(U50-N{slash}C-Pad4)") (class "Default")
      (node (ref "U50") (pin "4") (pinfunction "N/C_4") (pintype "unspecified+no_connect"))
    )
    (net (code "431") (name "unconnected-(U51-N{slash}C-Pad4)") (class "Default")
      (node (ref "U51") (pin "4") (pinfunction "N/C_4") (pintype "unspecified+no_connect"))
    )
    (net (code "432") (name "unconnected-(U53-PA11-Pad32)") (class "Default")
      (node (ref "U53") (pin "32") (pinfunction "PA11_32") (pintype "unspecified+no_connect"))
    )
    (net (code "433") (name "unconnected-(U53-PB12-Pad25)") (class "Default")
      (node (ref "U53") (pin "25") (pinfunction "PB12_25") (pintype "unspecified+no_connect"))
    )
    (net (code "434") (name "unconnected-(U53-PC14-OSC32_IN-Pad3)") (class "Default")
      (node (ref "U53") (pin "3") (pinfunction "PC14-OSC32_IN_3") (pintype "unspecified+no_connect"))
    )
    (net (code "435") (name "unconnected-(U53-PC15-OSC32_OUT-Pad4)") (class "Default")
      (node (ref "U53") (pin "4") (pinfunction "PC15-OSC32_OUT_4") (pintype "unspecified+no_connect"))
    )
  )
)
